# JugendLichtSteuerung.net
KiCad netlist of a schematic drawn in EAGLE
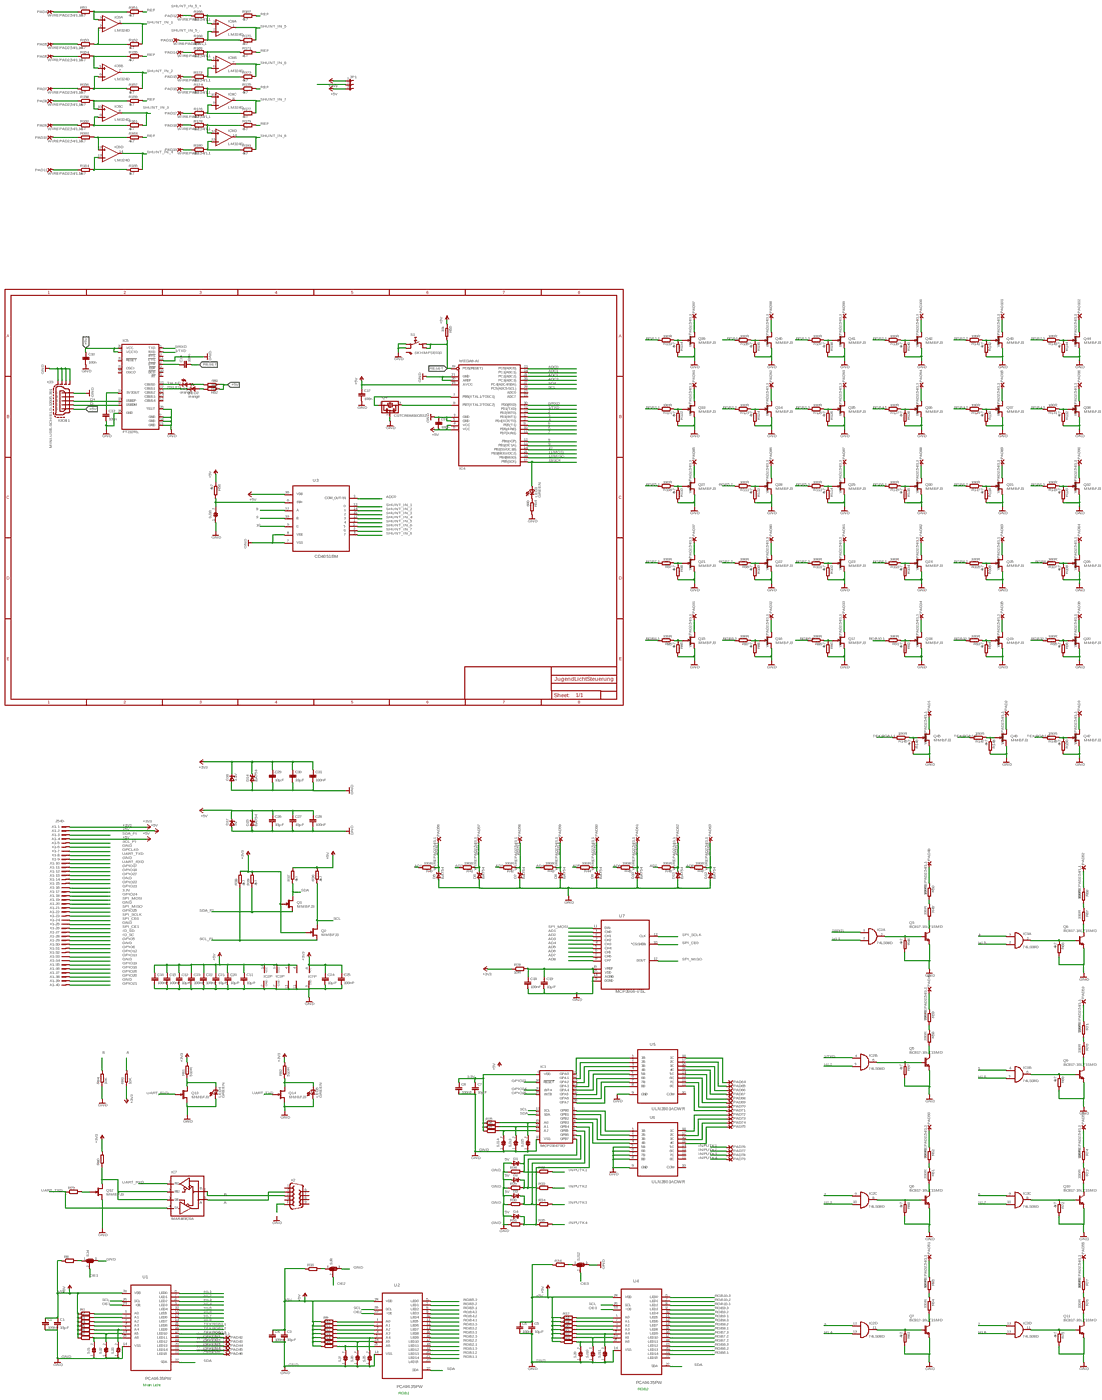
[diagram p0: schematic, sheet 1, overview]
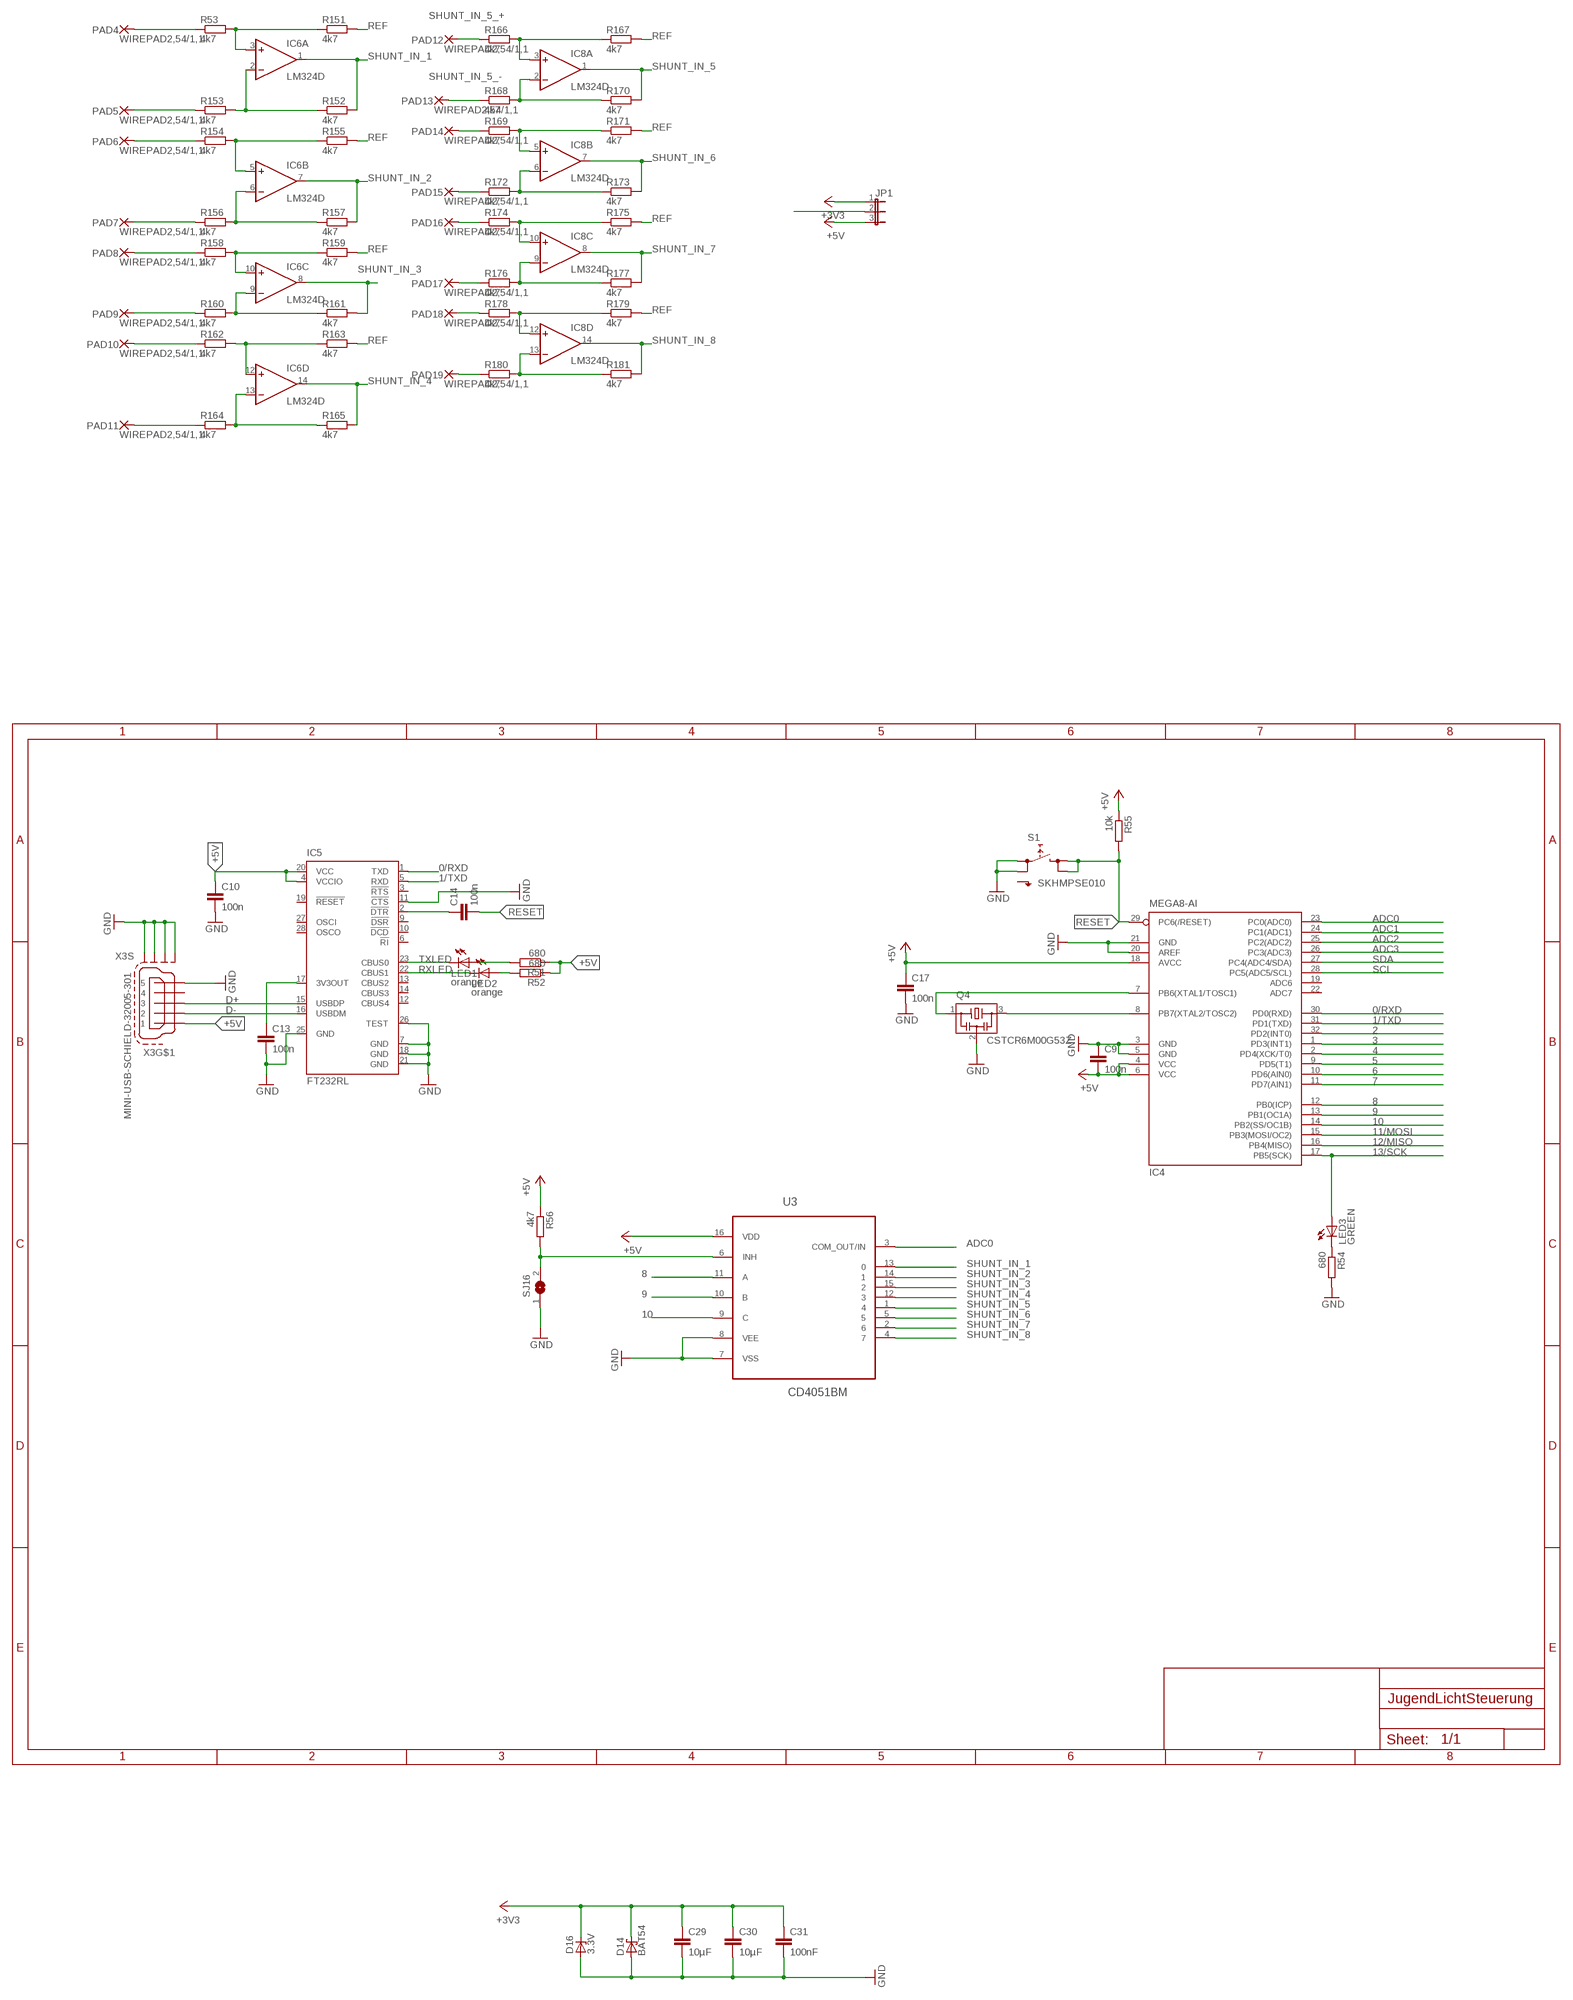
[diagram p1: schematic, sheet 1, part 1 of 4]
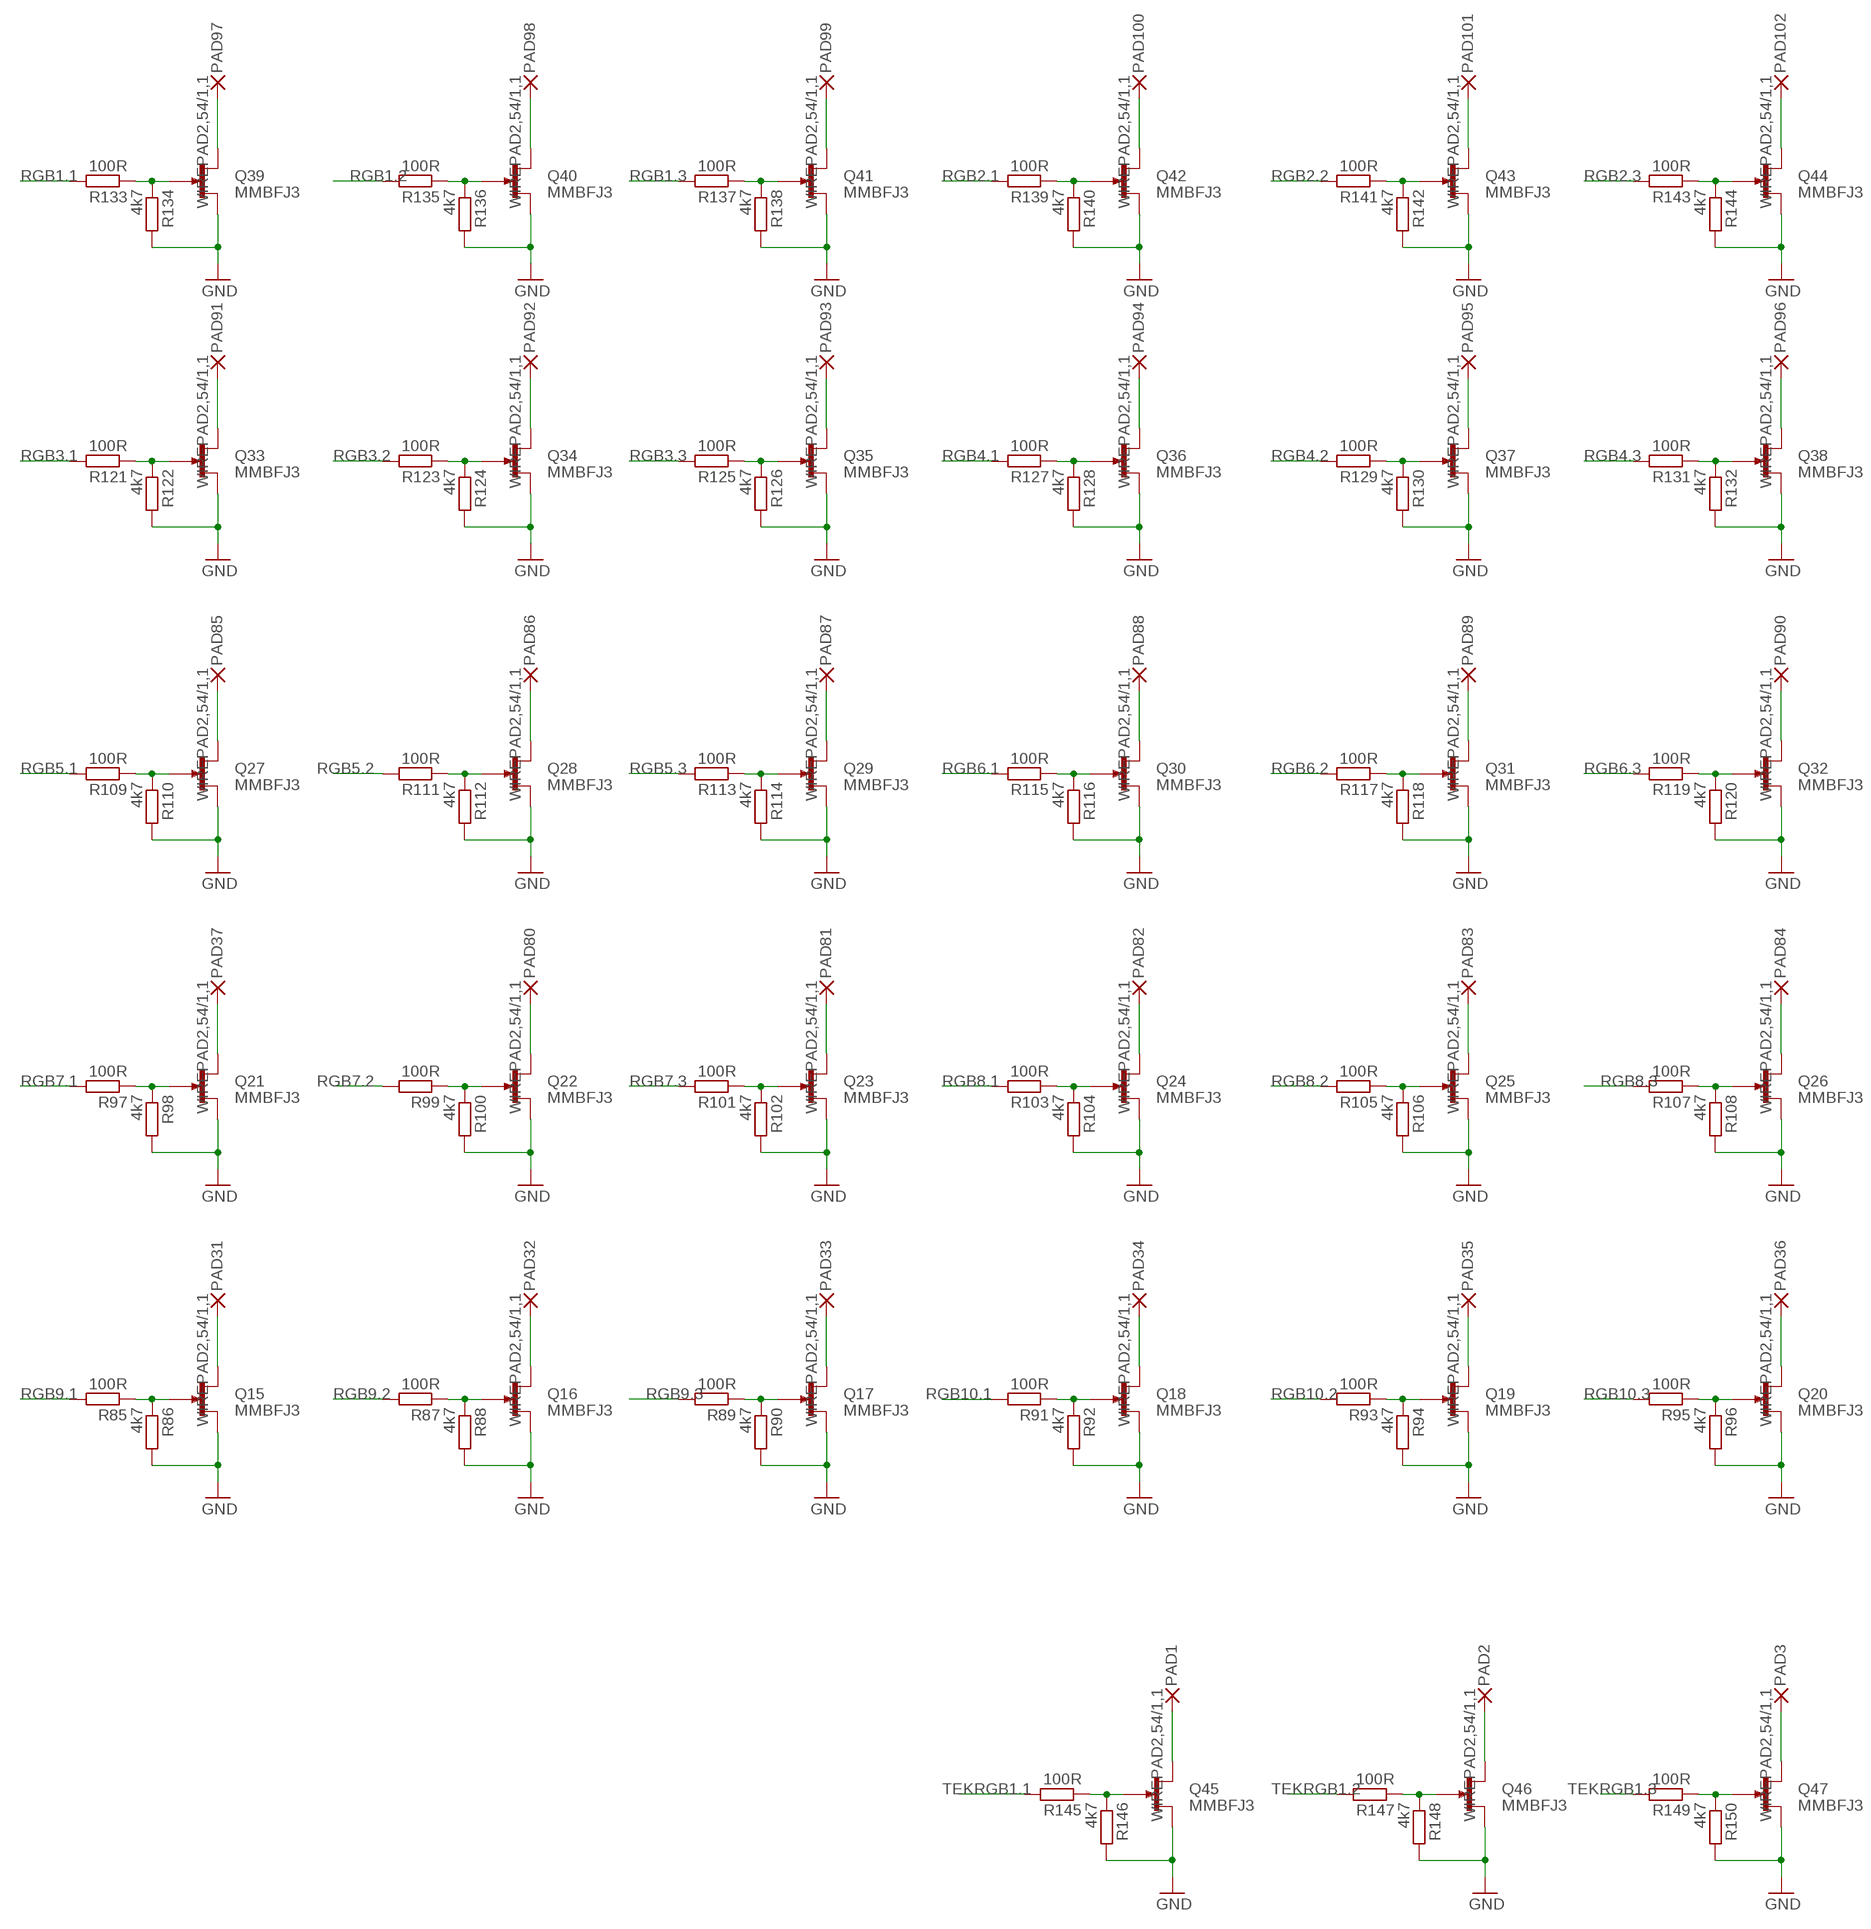
[diagram p2: schematic, sheet 1, part 2 of 4]
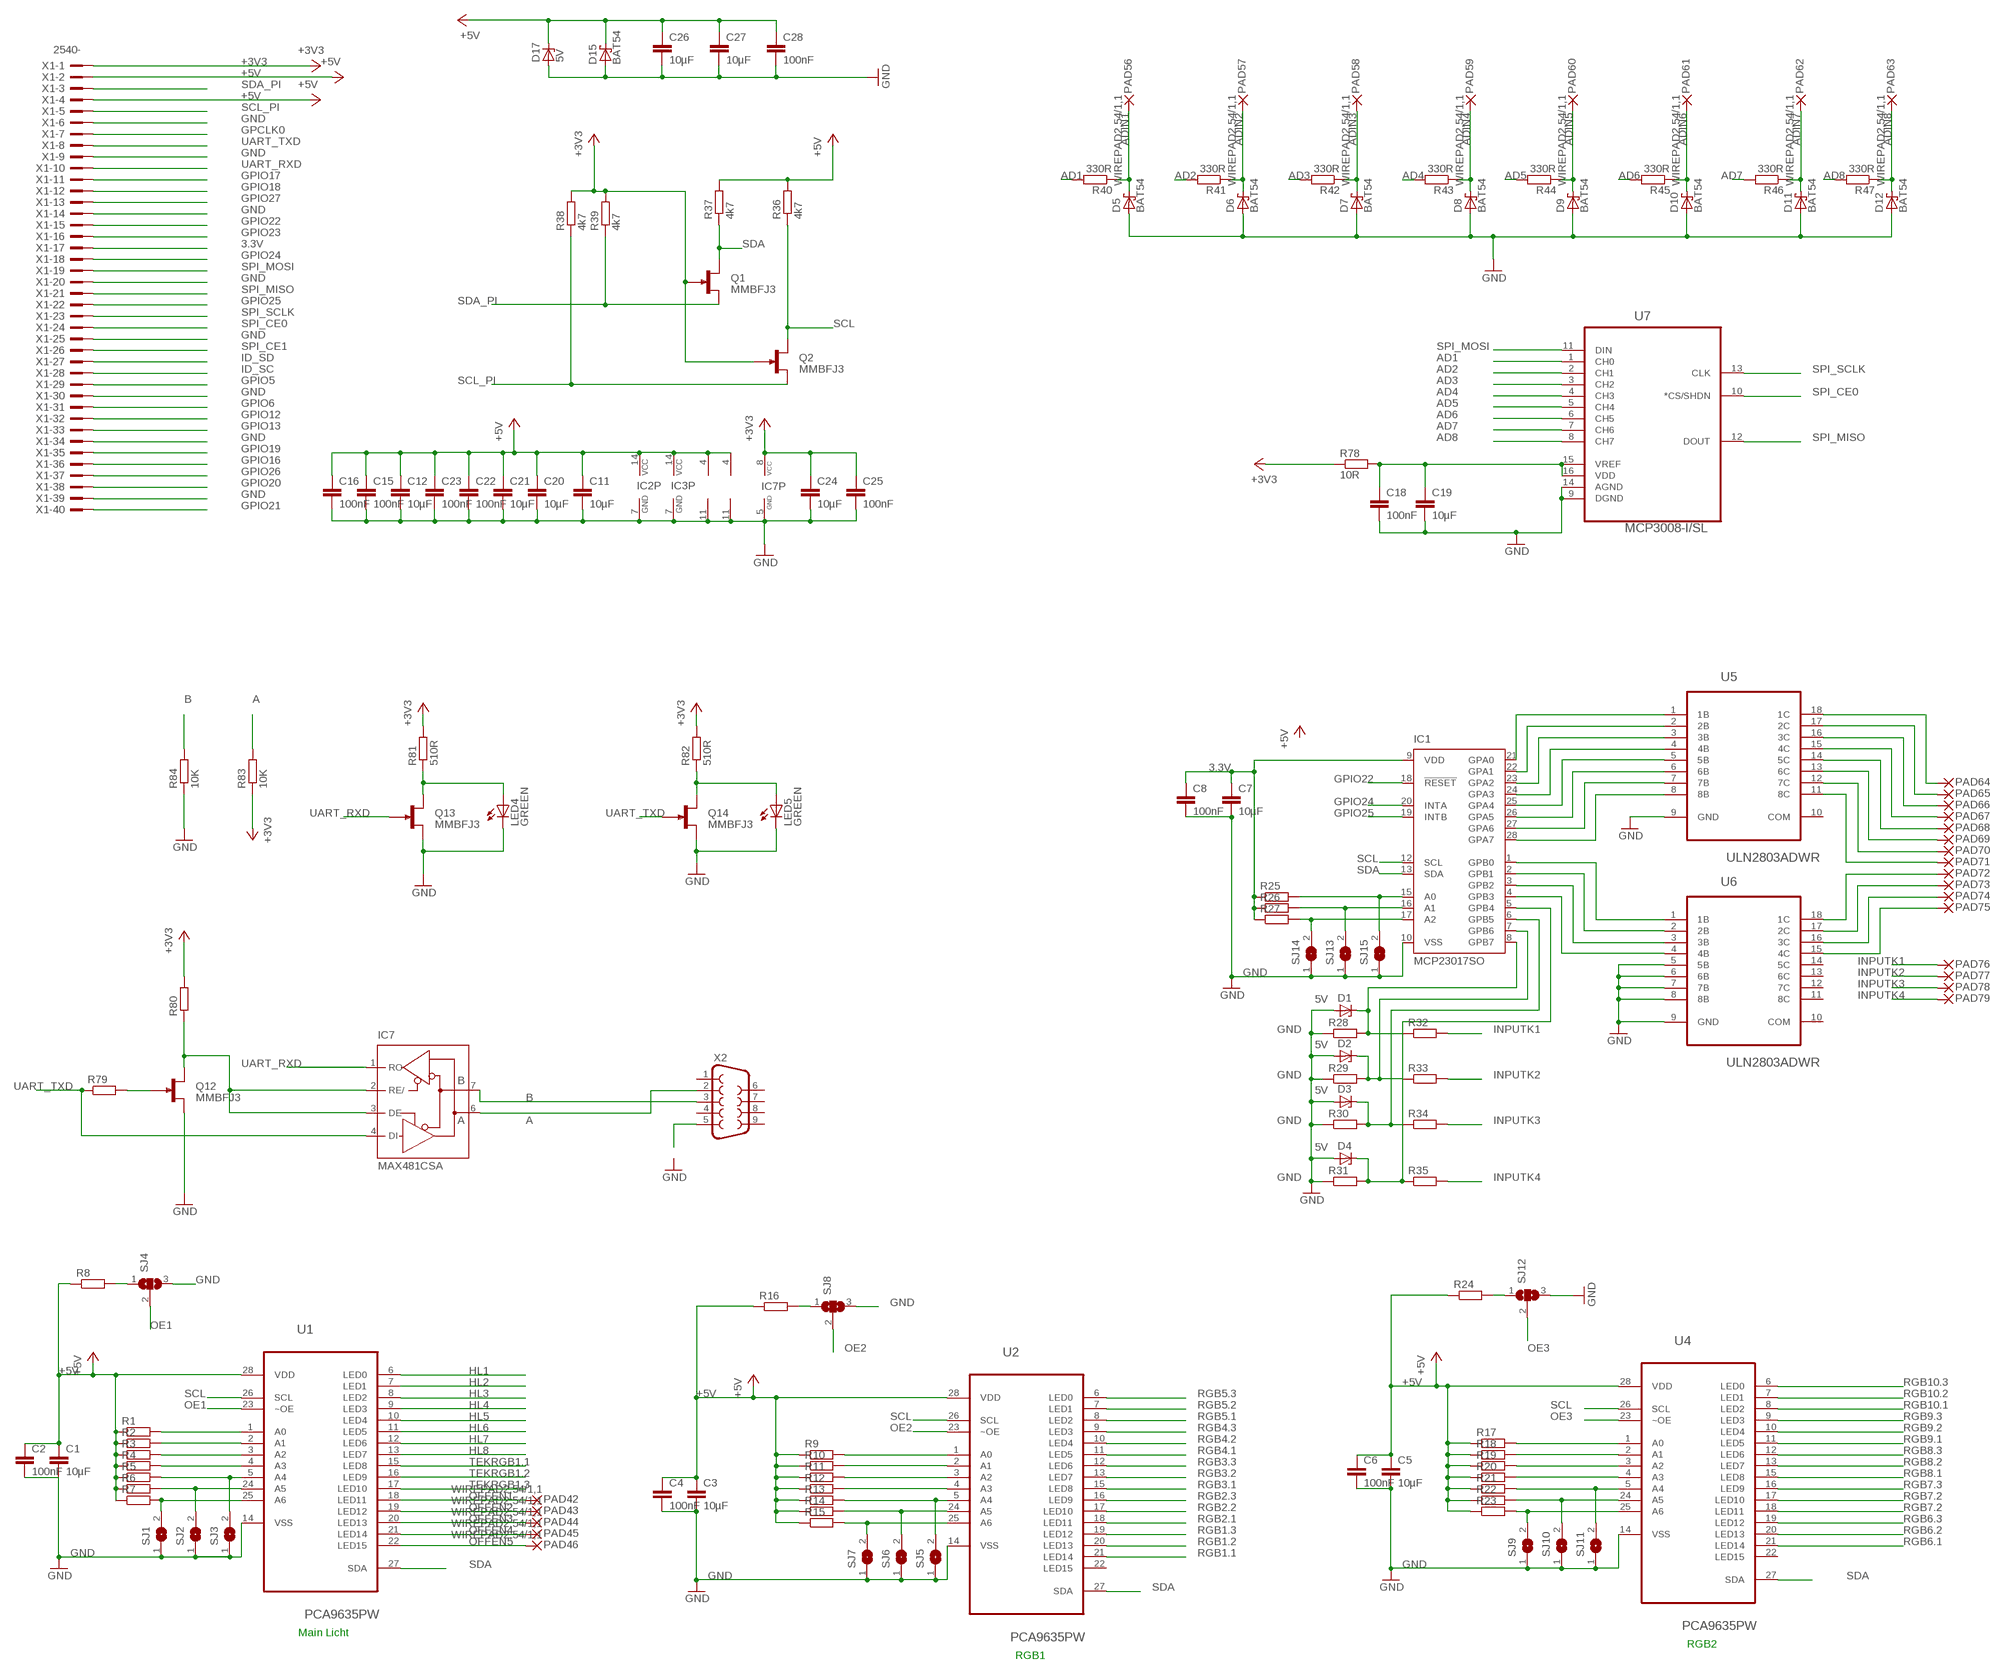
[diagram p3: schematic, sheet 1, part 3 of 4]
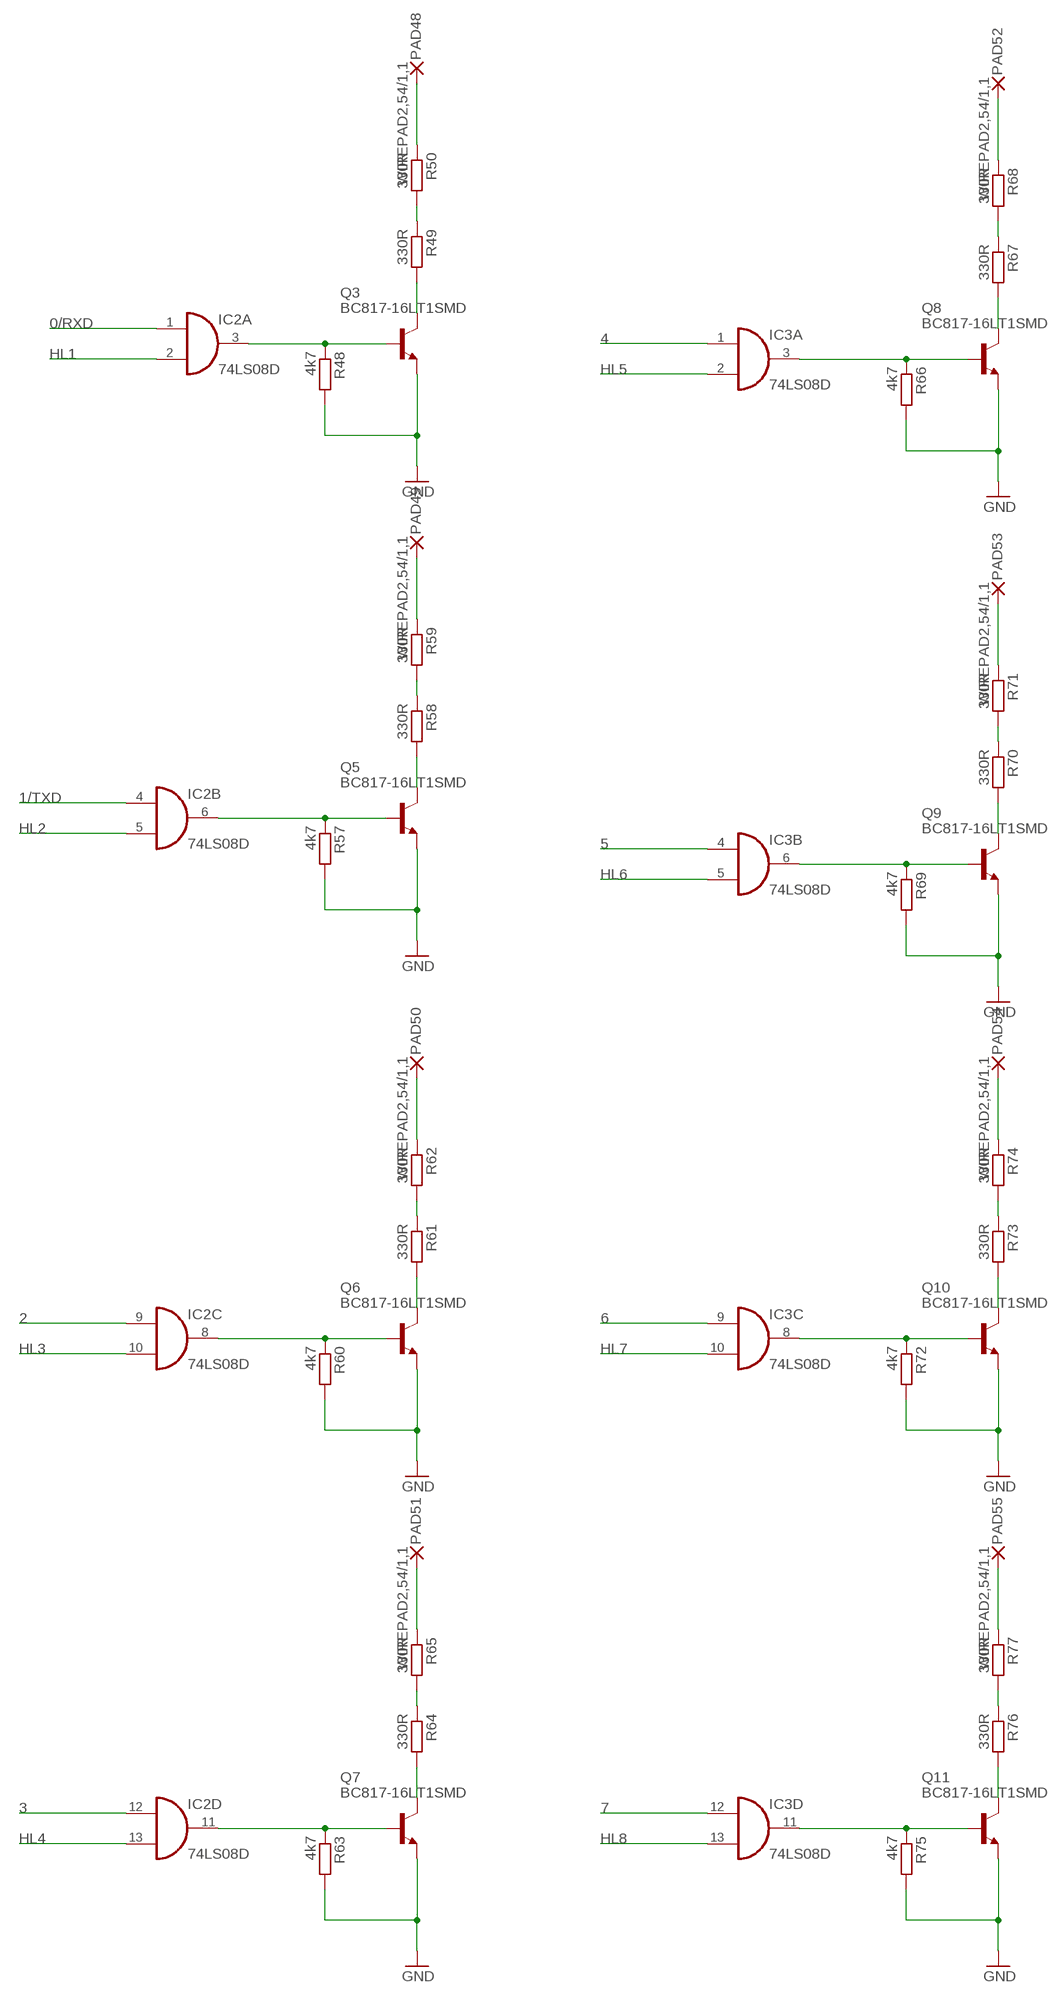
[diagram p4: schematic, sheet 1, part 4 of 4]

(export (version "E")
  (design (tool "Eeschema 10.0.6"))
  (components
    (comp (ref "C1")
      (value "10µF")
      (footprint "eagle-import:C0805")
      (libsource (lib "eagle-import") (part "C-EUC0805"))
    )
    (comp (ref "C2")
      (value "100nF")
      (footprint "eagle-import:C0805")
      (libsource (lib "eagle-import") (part "C-EUC0805"))
    )
    (comp (ref "C3")
      (value "10µF")
      (footprint "eagle-import:C0805")
      (libsource (lib "eagle-import") (part "C-EUC0805"))
    )
    (comp (ref "C4")
      (value "100nF")
      (footprint "eagle-import:C0805")
      (libsource (lib "eagle-import") (part "C-EUC0805"))
    )
    (comp (ref "C5")
      (value "10µF")
      (footprint "eagle-import:C0805")
      (libsource (lib "eagle-import") (part "C-EUC0805"))
    )
    (comp (ref "C6")
      (value "100nF")
      (footprint "eagle-import:C0805")
      (libsource (lib "eagle-import") (part "C-EUC0805"))
    )
    (comp (ref "C7")
      (value "10µF")
      (footprint "eagle-import:C0805")
      (libsource (lib "eagle-import") (part "C-EUC0805"))
    )
    (comp (ref "C8")
      (value "100nF")
      (footprint "eagle-import:C0805")
      (libsource (lib "eagle-import") (part "C-EUC0805"))
    )
    (comp (ref "C9")
      (value "100n")
      (footprint "eagle-import:C0603")
      (libsource (lib "eagle-import") (part "resistor_C-EUC0603"))
    )
    (comp (ref "C10")
      (value "100n")
      (footprint "eagle-import:C0603")
      (libsource (lib "eagle-import") (part "resistor_C-EUC0603"))
    )
    (comp (ref "C11")
      (value "10µF")
      (footprint "eagle-import:C0805")
      (libsource (lib "eagle-import") (part "C-EUC0805"))
    )
    (comp (ref "C12")
      (value "10µF")
      (footprint "eagle-import:C0805")
      (libsource (lib "eagle-import") (part "C-EUC0805"))
    )
    (comp (ref "C13")
      (value "100n")
      (footprint "eagle-import:C1206K")
      (libsource (lib "eagle-import") (part "C-EUC1206K"))
    )
    (comp (ref "C14")
      (value "100n")
      (footprint "eagle-import:C0603")
      (libsource (lib "eagle-import") (part "resistor_C-EUC0603"))
    )
    (comp (ref "C15")
      (value "100nF")
      (footprint "eagle-import:C0805")
      (libsource (lib "eagle-import") (part "C-EUC0805"))
    )
    (comp (ref "C16")
      (value "100nF")
      (footprint "eagle-import:C0805")
      (libsource (lib "eagle-import") (part "C-EUC0805"))
    )
    (comp (ref "C17")
      (value "100n")
      (footprint "eagle-import:C0603K")
      (libsource (lib "eagle-import") (part "C-EUC0603K"))
    )
    (comp (ref "C18")
      (value "100nF")
      (footprint "eagle-import:C0805")
      (libsource (lib "eagle-import") (part "C-EUC0805"))
    )
    (comp (ref "C19")
      (value "10µF")
      (footprint "eagle-import:C0805")
      (libsource (lib "eagle-import") (part "C-EUC0805"))
    )
    (comp (ref "C20")
      (value "10µF")
      (footprint "eagle-import:C0805")
      (libsource (lib "eagle-import") (part "C-EUC0805"))
    )
    (comp (ref "C21")
      (value "10µF")
      (footprint "eagle-import:C0805")
      (libsource (lib "eagle-import") (part "C-EUC0805"))
    )
    (comp (ref "C22")
      (value "100nF")
      (footprint "eagle-import:C0805")
      (libsource (lib "eagle-import") (part "C-EUC0805"))
    )
    (comp (ref "C23")
      (value "100nF")
      (footprint "eagle-import:C0805")
      (libsource (lib "eagle-import") (part "C-EUC0805"))
    )
    (comp (ref "C24")
      (value "10µF")
      (footprint "eagle-import:C0805")
      (libsource (lib "eagle-import") (part "C-EUC0805"))
    )
    (comp (ref "C25")
      (value "100nF")
      (footprint "eagle-import:C0805")
      (libsource (lib "eagle-import") (part "C-EUC0805"))
    )
    (comp (ref "C26")
      (value "10µF")
      (footprint "eagle-import:C0805")
      (libsource (lib "eagle-import") (part "C-EUC0805"))
    )
    (comp (ref "C27")
      (value "10µF")
      (footprint "eagle-import:C0805")
      (libsource (lib "eagle-import") (part "C-EUC0805"))
    )
    (comp (ref "C28")
      (value "100nF")
      (footprint "eagle-import:C0805")
      (libsource (lib "eagle-import") (part "C-EUC0805"))
    )
    (comp (ref "C29")
      (value "10µF")
      (footprint "eagle-import:C0805")
      (libsource (lib "eagle-import") (part "C-EUC0805"))
    )
    (comp (ref "C30")
      (value "10µF")
      (footprint "eagle-import:C0805")
      (libsource (lib "eagle-import") (part "C-EUC0805"))
    )
    (comp (ref "C31")
      (value "100nF")
      (footprint "eagle-import:C0805")
      (libsource (lib "eagle-import") (part "C-EUC0805"))
    )
    (comp (ref "D1")
      (value "5V")
      (footprint "eagle-import:SOD80C")
      (libsource (lib "eagle-import") (part "ZENER-DIODESOD80C"))
    )
    (comp (ref "D2")
      (value "5V")
      (footprint "eagle-import:SOD80C")
      (libsource (lib "eagle-import") (part "ZENER-DIODESOD80C"))
    )
    (comp (ref "D3")
      (value "5V")
      (footprint "eagle-import:SOD80C")
      (libsource (lib "eagle-import") (part "ZENER-DIODESOD80C"))
    )
    (comp (ref "D4")
      (value "5V")
      (footprint "eagle-import:SOD80C")
      (libsource (lib "eagle-import") (part "ZENER-DIODESOD80C"))
    )
    (comp (ref "D5")
      (value "BAT54")
      (footprint "eagle-import:SOT23")
      (libsource (lib "eagle-import") (part "BAT54"))
    )
    (comp (ref "D6")
      (value "BAT54")
      (footprint "eagle-import:SOT23")
      (libsource (lib "eagle-import") (part "BAT54"))
    )
    (comp (ref "D7")
      (value "BAT54")
      (footprint "eagle-import:SOT23")
      (libsource (lib "eagle-import") (part "BAT54"))
    )
    (comp (ref "D8")
      (value "BAT54")
      (footprint "eagle-import:SOT23")
      (libsource (lib "eagle-import") (part "BAT54"))
    )
    (comp (ref "D9")
      (value "BAT54")
      (footprint "eagle-import:SOT23")
      (libsource (lib "eagle-import") (part "BAT54"))
    )
    (comp (ref "D10")
      (value "BAT54")
      (footprint "eagle-import:SOT23")
      (libsource (lib "eagle-import") (part "BAT54"))
    )
    (comp (ref "D11")
      (value "BAT54")
      (footprint "eagle-import:SOT23")
      (libsource (lib "eagle-import") (part "BAT54"))
    )
    (comp (ref "D12")
      (value "BAT54")
      (footprint "eagle-import:SOT23")
      (libsource (lib "eagle-import") (part "BAT54"))
    )
    (comp (ref "D14")
      (value "BAT54")
      (footprint "eagle-import:SOT23")
      (libsource (lib "eagle-import") (part "BAT54"))
    )
    (comp (ref "D15")
      (value "BAT54")
      (footprint "eagle-import:SOT23")
      (libsource (lib "eagle-import") (part "BAT54"))
    )
    (comp (ref "D16")
      (value "3.3V")
      (footprint "eagle-import:SOD80C")
      (libsource (lib "eagle-import") (part "ZENER-DIODESOD80C"))
    )
    (comp (ref "D17")
      (value "5V")
      (footprint "eagle-import:SOD80C")
      (libsource (lib "eagle-import") (part "ZENER-DIODESOD80C"))
    )
    (comp (ref "IC1")
      (value "MCP23017SO")
      (footprint "eagle-import:SO28W")
      (fields (field (name "MF") "MICROCHIP") (field (name "MPN") "MCP23017-E/SO"))
      (libsource (lib "eagle-import") (part "MCP23017SO"))
    )
    (comp (ref "IC2")
      (value "74LS08D")
      (footprint "eagle-import:SO14")
      (libsource (lib "eagle-import") (part "7408DLS"))
    )
    (comp (ref "IC3")
      (value "74LS08D")
      (footprint "eagle-import:SO14")
      (libsource (lib "eagle-import") (part "7408DLS"))
    )
    (comp (ref "IC4")
      (value "MEGA8-AI")
      (footprint "eagle-import:TQFP32-08")
      (fields (field (name "MPN") "ATMEGA8-16AU"))
      (libsource (lib "eagle-import") (part "MEGA8-AI"))
    )
    (comp (ref "IC5")
      (value "FT232RL")
      (footprint "eagle-import:SSOP28")
      (libsource (lib "eagle-import") (part "FT232RL"))
    )
    (comp (ref "IC6")
      (value "LM324D")
      (footprint "eagle-import:SO14")
      (libsource (lib "eagle-import") (part "LM324D"))
    )
    (comp (ref "IC7")
      (value "MAX481CSA")
      (footprint "eagle-import:SO08")
      (fields (field (name "MF") "MAXIM"))
      (libsource (lib "eagle-import") (part "MAX481CSA"))
    )
    (comp (ref "IC8")
      (value "LM324D")
      (footprint "eagle-import:SO14")
      (libsource (lib "eagle-import") (part "LM324D"))
    )
    (comp (ref "JP1")
      (value "JP2E")
      (footprint "eagle-import:JP2")
      (libsource (lib "eagle-import") (part "JP2E"))
    )
    (comp (ref "LED1")
      (value "orange")
      (footprint "eagle-import:CHIPLED_1206")
      (libsource (lib "eagle-import") (part "LEDCHIPLED_1206"))
    )
    (comp (ref "LED2")
      (value "orange")
      (footprint "eagle-import:CHIPLED_1206")
      (libsource (lib "eagle-import") (part "LEDCHIPLED_1206"))
    )
    (comp (ref "LED3")
      (value "GREEN")
      (footprint "eagle-import:CHIPLED_1206")
      (libsource (lib "eagle-import") (part "LEDCHIPLED_1206"))
    )
    (comp (ref "LED4")
      (value "GREEN")
      (footprint "eagle-import:CHIPLED_1206")
      (libsource (lib "eagle-import") (part "LEDCHIPLED_1206"))
    )
    (comp (ref "LED5")
      (value "GREEN")
      (footprint "eagle-import:CHIPLED_1206")
      (libsource (lib "eagle-import") (part "LEDCHIPLED_1206"))
    )
    (comp (ref "PAD1")
      (value "WIREPAD2,54/1,1")
      (footprint "eagle-import:2,54_1,1")
      (libsource (lib "eagle-import") (part "WIREPAD2,54/1,1"))
    )
    (comp (ref "PAD2")
      (value "WIREPAD2,54/1,1")
      (footprint "eagle-import:2,54_1,1")
      (libsource (lib "eagle-import") (part "WIREPAD2,54/1,1"))
    )
    (comp (ref "PAD3")
      (value "WIREPAD2,54/1,1")
      (footprint "eagle-import:2,54_1,1")
      (libsource (lib "eagle-import") (part "WIREPAD2,54/1,1"))
    )
    (comp (ref "PAD4")
      (value "WIREPAD2,54/1,1")
      (footprint "eagle-import:2,54_1,1")
      (libsource (lib "eagle-import") (part "WIREPAD2,54/1,1"))
    )
    (comp (ref "PAD5")
      (value "WIREPAD2,54/1,1")
      (footprint "eagle-import:2,54_1,1")
      (libsource (lib "eagle-import") (part "WIREPAD2,54/1,1"))
    )
    (comp (ref "PAD6")
      (value "WIREPAD2,54/1,1")
      (footprint "eagle-import:2,54_1,1")
      (libsource (lib "eagle-import") (part "WIREPAD2,54/1,1"))
    )
    (comp (ref "PAD7")
      (value "WIREPAD2,54/1,1")
      (footprint "eagle-import:2,54_1,1")
      (libsource (lib "eagle-import") (part "WIREPAD2,54/1,1"))
    )
    (comp (ref "PAD8")
      (value "WIREPAD2,54/1,1")
      (footprint "eagle-import:2,54_1,1")
      (libsource (lib "eagle-import") (part "WIREPAD2,54/1,1"))
    )
    (comp (ref "PAD9")
      (value "WIREPAD2,54/1,1")
      (footprint "eagle-import:2,54_1,1")
      (libsource (lib "eagle-import") (part "WIREPAD2,54/1,1"))
    )
    (comp (ref "PAD10")
      (value "WIREPAD2,54/1,1")
      (footprint "eagle-import:2,54_1,1")
      (libsource (lib "eagle-import") (part "WIREPAD2,54/1,1"))
    )
    (comp (ref "PAD11")
      (value "WIREPAD2,54/1,1")
      (footprint "eagle-import:2,54_1,1")
      (libsource (lib "eagle-import") (part "WIREPAD2,54/1,1"))
    )
    (comp (ref "PAD12")
      (value "WIREPAD2,54/1,1")
      (footprint "eagle-import:2,54_1,1")
      (libsource (lib "eagle-import") (part "WIREPAD2,54/1,1"))
    )
    (comp (ref "PAD13")
      (value "WIREPAD2,54/1,1")
      (footprint "eagle-import:2,54_1,1")
      (libsource (lib "eagle-import") (part "WIREPAD2,54/1,1"))
    )
    (comp (ref "PAD14")
      (value "WIREPAD2,54/1,1")
      (footprint "eagle-import:2,54_1,1")
      (libsource (lib "eagle-import") (part "WIREPAD2,54/1,1"))
    )
    (comp (ref "PAD15")
      (value "WIREPAD2,54/1,1")
      (footprint "eagle-import:2,54_1,1")
      (libsource (lib "eagle-import") (part "WIREPAD2,54/1,1"))
    )
    (comp (ref "PAD16")
      (value "WIREPAD2,54/1,1")
      (footprint "eagle-import:2,54_1,1")
      (libsource (lib "eagle-import") (part "WIREPAD2,54/1,1"))
    )
    (comp (ref "PAD17")
      (value "WIREPAD2,54/1,1")
      (footprint "eagle-import:2,54_1,1")
      (libsource (lib "eagle-import") (part "WIREPAD2,54/1,1"))
    )
    (comp (ref "PAD18")
      (value "WIREPAD2,54/1,1")
      (footprint "eagle-import:2,54_1,1")
      (libsource (lib "eagle-import") (part "WIREPAD2,54/1,1"))
    )
    (comp (ref "PAD19")
      (value "WIREPAD2,54/1,1")
      (footprint "eagle-import:2,54_1,1")
      (libsource (lib "eagle-import") (part "WIREPAD2,54/1,1"))
    )
    (comp (ref "PAD31")
      (value "WIREPAD2,54/1,1")
      (footprint "eagle-import:2,54_1,1")
      (libsource (lib "eagle-import") (part "WIREPAD2,54/1,1"))
    )
    (comp (ref "PAD32")
      (value "WIREPAD2,54/1,1")
      (footprint "eagle-import:2,54_1,1")
      (libsource (lib "eagle-import") (part "WIREPAD2,54/1,1"))
    )
    (comp (ref "PAD33")
      (value "WIREPAD2,54/1,1")
      (footprint "eagle-import:2,54_1,1")
      (libsource (lib "eagle-import") (part "WIREPAD2,54/1,1"))
    )
    (comp (ref "PAD34")
      (value "WIREPAD2,54/1,1")
      (footprint "eagle-import:2,54_1,1")
      (libsource (lib "eagle-import") (part "WIREPAD2,54/1,1"))
    )
    (comp (ref "PAD35")
      (value "WIREPAD2,54/1,1")
      (footprint "eagle-import:2,54_1,1")
      (libsource (lib "eagle-import") (part "WIREPAD2,54/1,1"))
    )
    (comp (ref "PAD36")
      (value "WIREPAD2,54/1,1")
      (footprint "eagle-import:2,54_1,1")
      (libsource (lib "eagle-import") (part "WIREPAD2,54/1,1"))
    )
    (comp (ref "PAD37")
      (value "WIREPAD2,54/1,1")
      (footprint "eagle-import:2,54_1,1")
      (libsource (lib "eagle-import") (part "WIREPAD2,54/1,1"))
    )
    (comp (ref "PAD42")
      (value "WIREPAD2,54/1,1")
      (footprint "eagle-import:2,54_1,1")
      (libsource (lib "eagle-import") (part "WIREPAD2,54/1,1"))
    )
    (comp (ref "PAD43")
      (value "WIREPAD2,54/1,1")
      (footprint "eagle-import:2,54_1,1")
      (libsource (lib "eagle-import") (part "WIREPAD2,54/1,1"))
    )
    (comp (ref "PAD44")
      (value "WIREPAD2,54/1,1")
      (footprint "eagle-import:2,54_1,1")
      (libsource (lib "eagle-import") (part "WIREPAD2,54/1,1"))
    )
    (comp (ref "PAD45")
      (value "WIREPAD2,54/1,1")
      (footprint "eagle-import:2,54_1,1")
      (libsource (lib "eagle-import") (part "WIREPAD2,54/1,1"))
    )
    (comp (ref "PAD46")
      (value "WIREPAD2,54/1,1")
      (footprint "eagle-import:2,54_1,1")
      (libsource (lib "eagle-import") (part "WIREPAD2,54/1,1"))
    )
    (comp (ref "PAD48")
      (value "WIREPAD2,54/1,1")
      (footprint "eagle-import:2,54_1,1")
      (libsource (lib "eagle-import") (part "WIREPAD2,54/1,1"))
    )
    (comp (ref "PAD49")
      (value "WIREPAD2,54/1,1")
      (footprint "eagle-import:2,54_1,1")
      (libsource (lib "eagle-import") (part "WIREPAD2,54/1,1"))
    )
    (comp (ref "PAD50")
      (value "WIREPAD2,54/1,1")
      (footprint "eagle-import:2,54_1,1")
      (libsource (lib "eagle-import") (part "WIREPAD2,54/1,1"))
    )
    (comp (ref "PAD51")
      (value "WIREPAD2,54/1,1")
      (footprint "eagle-import:2,54_1,1")
      (libsource (lib "eagle-import") (part "WIREPAD2,54/1,1"))
    )
    (comp (ref "PAD52")
      (value "WIREPAD2,54/1,1")
      (footprint "eagle-import:2,54_1,1")
      (libsource (lib "eagle-import") (part "WIREPAD2,54/1,1"))
    )
    (comp (ref "PAD53")
      (value "WIREPAD2,54/1,1")
      (footprint "eagle-import:2,54_1,1")
      (libsource (lib "eagle-import") (part "WIREPAD2,54/1,1"))
    )
    (comp (ref "PAD54")
      (value "WIREPAD2,54/1,1")
      (footprint "eagle-import:2,54_1,1")
      (libsource (lib "eagle-import") (part "WIREPAD2,54/1,1"))
    )
    (comp (ref "PAD55")
      (value "WIREPAD2,54/1,1")
      (footprint "eagle-import:2,54_1,1")
      (libsource (lib "eagle-import") (part "WIREPAD2,54/1,1"))
    )
    (comp (ref "PAD56")
      (value "WIREPAD2,54/1,1")
      (footprint "eagle-import:2,54_1,1")
      (libsource (lib "eagle-import") (part "WIREPAD2,54/1,1"))
    )
    (comp (ref "PAD57")
      (value "WIREPAD2,54/1,1")
      (footprint "eagle-import:2,54_1,1")
      (libsource (lib "eagle-import") (part "WIREPAD2,54/1,1"))
    )
    (comp (ref "PAD58")
      (value "WIREPAD2,54/1,1")
      (footprint "eagle-import:2,54_1,1")
      (libsource (lib "eagle-import") (part "WIREPAD2,54/1,1"))
    )
    (comp (ref "PAD59")
      (value "WIREPAD2,54/1,1")
      (footprint "eagle-import:2,54_1,1")
      (libsource (lib "eagle-import") (part "WIREPAD2,54/1,1"))
    )
    (comp (ref "PAD60")
      (value "WIREPAD2,54/1,1")
      (footprint "eagle-import:2,54_1,1")
      (libsource (lib "eagle-import") (part "WIREPAD2,54/1,1"))
    )
    (comp (ref "PAD61")
      (value "WIREPAD2,54/1,1")
      (footprint "eagle-import:2,54_1,1")
      (libsource (lib "eagle-import") (part "WIREPAD2,54/1,1"))
    )
    (comp (ref "PAD62")
      (value "WIREPAD2,54/1,1")
      (footprint "eagle-import:2,54_1,1")
      (libsource (lib "eagle-import") (part "WIREPAD2,54/1,1"))
    )
    (comp (ref "PAD63")
      (value "WIREPAD2,54/1,1")
      (footprint "eagle-import:2,54_1,1")
      (libsource (lib "eagle-import") (part "WIREPAD2,54/1,1"))
    )
    (comp (ref "PAD64")
      (value "3,81/1,4")
      (footprint "eagle-import:3,81_1,4")
      (libsource (lib "eagle-import") (part "3,81/1,4"))
    )
    (comp (ref "PAD65")
      (value "3,81/1,4")
      (footprint "eagle-import:3,81_1,4")
      (libsource (lib "eagle-import") (part "3,81/1,4"))
    )
    (comp (ref "PAD66")
      (value "3,81/1,4")
      (footprint "eagle-import:3,81_1,4")
      (libsource (lib "eagle-import") (part "3,81/1,4"))
    )
    (comp (ref "PAD67")
      (value "3,81/1,4")
      (footprint "eagle-import:3,81_1,4")
      (libsource (lib "eagle-import") (part "3,81/1,4"))
    )
    (comp (ref "PAD68")
      (value "3,81/1,4")
      (footprint "eagle-import:3,81_1,4")
      (libsource (lib "eagle-import") (part "3,81/1,4"))
    )
    (comp (ref "PAD69")
      (value "3,81/1,4")
      (footprint "eagle-import:3,81_1,4")
      (libsource (lib "eagle-import") (part "3,81/1,4"))
    )
    (comp (ref "PAD70")
      (value "3,81/1,4")
      (footprint "eagle-import:3,81_1,4")
      (libsource (lib "eagle-import") (part "3,81/1,4"))
    )
    (comp (ref "PAD71")
      (value "3,81/1,4")
      (footprint "eagle-import:3,81_1,4")
      (libsource (lib "eagle-import") (part "3,81/1,4"))
    )
    (comp (ref "PAD72")
      (value "3,81/1,4")
      (footprint "eagle-import:3,81_1,4")
      (libsource (lib "eagle-import") (part "3,81/1,4"))
    )
    (comp (ref "PAD73")
      (value "3,81/1,4")
      (footprint "eagle-import:3,81_1,4")
      (libsource (lib "eagle-import") (part "3,81/1,4"))
    )
    (comp (ref "PAD74")
      (value "3,81/1,4")
      (footprint "eagle-import:3,81_1,4")
      (libsource (lib "eagle-import") (part "3,81/1,4"))
    )
    (comp (ref "PAD75")
      (value "3,81/1,4")
      (footprint "eagle-import:3,81_1,4")
      (libsource (lib "eagle-import") (part "3,81/1,4"))
    )
    (comp (ref "PAD76")
      (value "3,81/1,4")
      (footprint "eagle-import:3,81_1,4")
      (libsource (lib "eagle-import") (part "3,81/1,4"))
    )
    (comp (ref "PAD77")
      (value "3,81/1,4")
      (footprint "eagle-import:3,81_1,4")
      (libsource (lib "eagle-import") (part "3,81/1,4"))
    )
    (comp (ref "PAD78")
      (value "3,81/1,4")
      (footprint "eagle-import:3,81_1,4")
      (libsource (lib "eagle-import") (part "3,81/1,4"))
    )
    (comp (ref "PAD79")
      (value "3,81/1,4")
      (footprint "eagle-import:3,81_1,4")
      (libsource (lib "eagle-import") (part "3,81/1,4"))
    )
    (comp (ref "PAD80")
      (value "WIREPAD2,54/1,1")
      (footprint "eagle-import:2,54_1,1")
      (libsource (lib "eagle-import") (part "WIREPAD2,54/1,1"))
    )
    (comp (ref "PAD81")
      (value "WIREPAD2,54/1,1")
      (footprint "eagle-import:2,54_1,1")
      (libsource (lib "eagle-import") (part "WIREPAD2,54/1,1"))
    )
    (comp (ref "PAD82")
      (value "WIREPAD2,54/1,1")
      (footprint "eagle-import:2,54_1,1")
      (libsource (lib "eagle-import") (part "WIREPAD2,54/1,1"))
    )
    (comp (ref "PAD83")
      (value "WIREPAD2,54/1,1")
      (footprint "eagle-import:2,54_1,1")
      (libsource (lib "eagle-import") (part "WIREPAD2,54/1,1"))
    )
    (comp (ref "PAD84")
      (value "WIREPAD2,54/1,1")
      (footprint "eagle-import:2,54_1,1")
      (libsource (lib "eagle-import") (part "WIREPAD2,54/1,1"))
    )
    (comp (ref "PAD85")
      (value "WIREPAD2,54/1,1")
      (footprint "eagle-import:2,54_1,1")
      (libsource (lib "eagle-import") (part "WIREPAD2,54/1,1"))
    )
    (comp (ref "PAD86")
      (value "WIREPAD2,54/1,1")
      (footprint "eagle-import:2,54_1,1")
      (libsource (lib "eagle-import") (part "WIREPAD2,54/1,1"))
    )
    (comp (ref "PAD87")
      (value "WIREPAD2,54/1,1")
      (footprint "eagle-import:2,54_1,1")
      (libsource (lib "eagle-import") (part "WIREPAD2,54/1,1"))
    )
    (comp (ref "PAD88")
      (value "WIREPAD2,54/1,1")
      (footprint "eagle-import:2,54_1,1")
      (libsource (lib "eagle-import") (part "WIREPAD2,54/1,1"))
    )
    (comp (ref "PAD89")
      (value "WIREPAD2,54/1,1")
      (footprint "eagle-import:2,54_1,1")
      (libsource (lib "eagle-import") (part "WIREPAD2,54/1,1"))
    )
    (comp (ref "PAD90")
      (value "WIREPAD2,54/1,1")
      (footprint "eagle-import:2,54_1,1")
      (libsource (lib "eagle-import") (part "WIREPAD2,54/1,1"))
    )
    (comp (ref "PAD91")
      (value "WIREPAD2,54/1,1")
      (footprint "eagle-import:2,54_1,1")
      (libsource (lib "eagle-import") (part "WIREPAD2,54/1,1"))
    )
    (comp (ref "PAD92")
      (value "WIREPAD2,54/1,1")
      (footprint "eagle-import:2,54_1,1")
      (libsource (lib "eagle-import") (part "WIREPAD2,54/1,1"))
    )
    (comp (ref "PAD93")
      (value "WIREPAD2,54/1,1")
      (footprint "eagle-import:2,54_1,1")
      (libsource (lib "eagle-import") (part "WIREPAD2,54/1,1"))
    )
    (comp (ref "PAD94")
      (value "WIREPAD2,54/1,1")
      (footprint "eagle-import:2,54_1,1")
      (libsource (lib "eagle-import") (part "WIREPAD2,54/1,1"))
    )
    (comp (ref "PAD95")
      (value "WIREPAD2,54/1,1")
      (footprint "eagle-import:2,54_1,1")
      (libsource (lib "eagle-import") (part "WIREPAD2,54/1,1"))
    )
    (comp (ref "PAD96")
      (value "WIREPAD2,54/1,1")
      (footprint "eagle-import:2,54_1,1")
      (libsource (lib "eagle-import") (part "WIREPAD2,54/1,1"))
    )
    (comp (ref "PAD97")
      (value "WIREPAD2,54/1,1")
      (footprint "eagle-import:2,54_1,1")
      (libsource (lib "eagle-import") (part "WIREPAD2,54/1,1"))
    )
    (comp (ref "PAD98")
      (value "WIREPAD2,54/1,1")
      (footprint "eagle-import:2,54_1,1")
      (libsource (lib "eagle-import") (part "WIREPAD2,54/1,1"))
    )
    (comp (ref "PAD99")
      (value "WIREPAD2,54/1,1")
      (footprint "eagle-import:2,54_1,1")
      (libsource (lib "eagle-import") (part "WIREPAD2,54/1,1"))
    )
    (comp (ref "PAD100")
      (value "WIREPAD2,54/1,1")
      (footprint "eagle-import:2,54_1,1")
      (libsource (lib "eagle-import") (part "WIREPAD2,54/1,1"))
    )
    (comp (ref "PAD101")
      (value "WIREPAD2,54/1,1")
      (footprint "eagle-import:2,54_1,1")
      (libsource (lib "eagle-import") (part "WIREPAD2,54/1,1"))
    )
    (comp (ref "PAD102")
      (value "WIREPAD2,54/1,1")
      (footprint "eagle-import:2,54_1,1")
      (libsource (lib "eagle-import") (part "WIREPAD2,54/1,1"))
    )
    (comp (ref "Q1")
      (value "MMBFJ3")
      (footprint "eagle-import:SOT23")
      (libsource (lib "eagle-import") (part "MMBFJ3"))
    )
    (comp (ref "Q2")
      (value "MMBFJ3")
      (footprint "eagle-import:SOT23")
      (libsource (lib "eagle-import") (part "MMBFJ3"))
    )
    (comp (ref "Q3")
      (value "BC817-16LT1SMD")
      (footprint "eagle-import:SOT23-BEC")
      (libsource (lib "eagle-import") (part "BC817SMD-16LT1"))
    )
    (comp (ref "Q4")
      (value "CSTCR6M00G53Z")
      (footprint "eagle-import:CSTCR6M")
      (fields (field (name "MPN") "CSTCR6M00G53-R0"))
      (libsource (lib "eagle-import") (part "CSTCR6M00G53Z"))
    )
    (comp (ref "Q5")
      (value "BC817-16LT1SMD")
      (footprint "eagle-import:SOT23-BEC")
      (libsource (lib "eagle-import") (part "BC817SMD-16LT1"))
    )
    (comp (ref "Q6")
      (value "BC817-16LT1SMD")
      (footprint "eagle-import:SOT23-BEC")
      (libsource (lib "eagle-import") (part "BC817SMD-16LT1"))
    )
    (comp (ref "Q7")
      (value "BC817-16LT1SMD")
      (footprint "eagle-import:SOT23-BEC")
      (libsource (lib "eagle-import") (part "BC817SMD-16LT1"))
    )
    (comp (ref "Q8")
      (value "BC817-16LT1SMD")
      (footprint "eagle-import:SOT23-BEC")
      (libsource (lib "eagle-import") (part "BC817SMD-16LT1"))
    )
    (comp (ref "Q9")
      (value "BC817-16LT1SMD")
      (footprint "eagle-import:SOT23-BEC")
      (libsource (lib "eagle-import") (part "BC817SMD-16LT1"))
    )
    (comp (ref "Q10")
      (value "BC817-16LT1SMD")
      (footprint "eagle-import:SOT23-BEC")
      (libsource (lib "eagle-import") (part "BC817SMD-16LT1"))
    )
    (comp (ref "Q11")
      (value "BC817-16LT1SMD")
      (footprint "eagle-import:SOT23-BEC")
      (libsource (lib "eagle-import") (part "BC817SMD-16LT1"))
    )
    (comp (ref "Q12")
      (value "MMBFJ3")
      (footprint "eagle-import:SOT23")
      (libsource (lib "eagle-import") (part "MMBFJ3"))
    )
    (comp (ref "Q13")
      (value "MMBFJ3")
      (footprint "eagle-import:SOT23")
      (libsource (lib "eagle-import") (part "MMBFJ3"))
    )
    (comp (ref "Q14")
      (value "MMBFJ3")
      (footprint "eagle-import:SOT23")
      (libsource (lib "eagle-import") (part "MMBFJ3"))
    )
    (comp (ref "Q15")
      (value "MMBFJ3")
      (footprint "eagle-import:SOT23")
      (libsource (lib "eagle-import") (part "MMBFJ3"))
    )
    (comp (ref "Q16")
      (value "MMBFJ3")
      (footprint "eagle-import:SOT23")
      (libsource (lib "eagle-import") (part "MMBFJ3"))
    )
    (comp (ref "Q17")
      (value "MMBFJ3")
      (footprint "eagle-import:SOT23")
      (libsource (lib "eagle-import") (part "MMBFJ3"))
    )
    (comp (ref "Q18")
      (value "MMBFJ3")
      (footprint "eagle-import:SOT23")
      (libsource (lib "eagle-import") (part "MMBFJ3"))
    )
    (comp (ref "Q19")
      (value "MMBFJ3")
      (footprint "eagle-import:SOT23")
      (libsource (lib "eagle-import") (part "MMBFJ3"))
    )
    (comp (ref "Q20")
      (value "MMBFJ3")
      (footprint "eagle-import:SOT23")
      (libsource (lib "eagle-import") (part "MMBFJ3"))
    )
    (comp (ref "Q21")
      (value "MMBFJ3")
      (footprint "eagle-import:SOT23")
      (libsource (lib "eagle-import") (part "MMBFJ3"))
    )
    (comp (ref "Q22")
      (value "MMBFJ3")
      (footprint "eagle-import:SOT23")
      (libsource (lib "eagle-import") (part "MMBFJ3"))
    )
    (comp (ref "Q23")
      (value "MMBFJ3")
      (footprint "eagle-import:SOT23")
      (libsource (lib "eagle-import") (part "MMBFJ3"))
    )
    (comp (ref "Q24")
      (value "MMBFJ3")
      (footprint "eagle-import:SOT23")
      (libsource (lib "eagle-import") (part "MMBFJ3"))
    )
    (comp (ref "Q25")
      (value "MMBFJ3")
      (footprint "eagle-import:SOT23")
      (libsource (lib "eagle-import") (part "MMBFJ3"))
    )
    (comp (ref "Q26")
      (value "MMBFJ3")
      (footprint "eagle-import:SOT23")
      (libsource (lib "eagle-import") (part "MMBFJ3"))
    )
    (comp (ref "Q27")
      (value "MMBFJ3")
      (footprint "eagle-import:SOT23")
      (libsource (lib "eagle-import") (part "MMBFJ3"))
    )
    (comp (ref "Q28")
      (value "MMBFJ3")
      (footprint "eagle-import:SOT23")
      (libsource (lib "eagle-import") (part "MMBFJ3"))
    )
    (comp (ref "Q29")
      (value "MMBFJ3")
      (footprint "eagle-import:SOT23")
      (libsource (lib "eagle-import") (part "MMBFJ3"))
    )
    (comp (ref "Q30")
      (value "MMBFJ3")
      (footprint "eagle-import:SOT23")
      (libsource (lib "eagle-import") (part "MMBFJ3"))
    )
    (comp (ref "Q31")
      (value "MMBFJ3")
      (footprint "eagle-import:SOT23")
      (libsource (lib "eagle-import") (part "MMBFJ3"))
    )
    (comp (ref "Q32")
      (value "MMBFJ3")
      (footprint "eagle-import:SOT23")
      (libsource (lib "eagle-import") (part "MMBFJ3"))
    )
    (comp (ref "Q33")
      (value "MMBFJ3")
      (footprint "eagle-import:SOT23")
      (libsource (lib "eagle-import") (part "MMBFJ3"))
    )
    (comp (ref "Q34")
      (value "MMBFJ3")
      (footprint "eagle-import:SOT23")
      (libsource (lib "eagle-import") (part "MMBFJ3"))
    )
    (comp (ref "Q35")
      (value "MMBFJ3")
      (footprint "eagle-import:SOT23")
      (libsource (lib "eagle-import") (part "MMBFJ3"))
    )
    (comp (ref "Q36")
      (value "MMBFJ3")
      (footprint "eagle-import:SOT23")
      (libsource (lib "eagle-import") (part "MMBFJ3"))
    )
    (comp (ref "Q37")
      (value "MMBFJ3")
      (footprint "eagle-import:SOT23")
      (libsource (lib "eagle-import") (part "MMBFJ3"))
    )
    (comp (ref "Q38")
      (value "MMBFJ3")
      (footprint "eagle-import:SOT23")
      (libsource (lib "eagle-import") (part "MMBFJ3"))
    )
    (comp (ref "Q39")
      (value "MMBFJ3")
      (footprint "eagle-import:SOT23")
      (libsource (lib "eagle-import") (part "MMBFJ3"))
    )
    (comp (ref "Q40")
      (value "MMBFJ3")
      (footprint "eagle-import:SOT23")
      (libsource (lib "eagle-import") (part "MMBFJ3"))
    )
    (comp (ref "Q41")
      (value "MMBFJ3")
      (footprint "eagle-import:SOT23")
      (libsource (lib "eagle-import") (part "MMBFJ3"))
    )
    (comp (ref "Q42")
      (value "MMBFJ3")
      (footprint "eagle-import:SOT23")
      (libsource (lib "eagle-import") (part "MMBFJ3"))
    )
    (comp (ref "Q43")
      (value "MMBFJ3")
      (footprint "eagle-import:SOT23")
      (libsource (lib "eagle-import") (part "MMBFJ3"))
    )
    (comp (ref "Q44")
      (value "MMBFJ3")
      (footprint "eagle-import:SOT23")
      (libsource (lib "eagle-import") (part "MMBFJ3"))
    )
    (comp (ref "Q45")
      (value "MMBFJ3")
      (footprint "eagle-import:SOT23")
      (libsource (lib "eagle-import") (part "MMBFJ3"))
    )
    (comp (ref "Q46")
      (value "MMBFJ3")
      (footprint "eagle-import:SOT23")
      (libsource (lib "eagle-import") (part "MMBFJ3"))
    )
    (comp (ref "Q47")
      (value "MMBFJ3")
      (footprint "eagle-import:SOT23")
      (libsource (lib "eagle-import") (part "MMBFJ3"))
    )
    (comp (ref "R1")
      (value "R-EU_R0603")
      (footprint "eagle-import:R0603")
      (libsource (lib "eagle-import") (part "R-EU_R0603"))
    )
    (comp (ref "R2")
      (value "R-EU_R0603")
      (footprint "eagle-import:R0603")
      (libsource (lib "eagle-import") (part "R-EU_R0603"))
    )
    (comp (ref "R3")
      (value "R-EU_R0603")
      (footprint "eagle-import:R0603")
      (libsource (lib "eagle-import") (part "R-EU_R0603"))
    )
    (comp (ref "R4")
      (value "R-EU_R0603")
      (footprint "eagle-import:R0603")
      (libsource (lib "eagle-import") (part "R-EU_R0603"))
    )
    (comp (ref "R5")
      (value "R-EU_R0603")
      (footprint "eagle-import:R0603")
      (libsource (lib "eagle-import") (part "R-EU_R0603"))
    )
    (comp (ref "R6")
      (value "R-EU_R0603")
      (footprint "eagle-import:R0603")
      (libsource (lib "eagle-import") (part "R-EU_R0603"))
    )
    (comp (ref "R7")
      (value "R-EU_R0603")
      (footprint "eagle-import:R0603")
      (libsource (lib "eagle-import") (part "R-EU_R0603"))
    )
    (comp (ref "R8")
      (value "R-EU_R0603")
      (footprint "eagle-import:R0603")
      (libsource (lib "eagle-import") (part "R-EU_R0603"))
    )
    (comp (ref "R9")
      (value "R-EU_R0603")
      (footprint "eagle-import:R0603")
      (libsource (lib "eagle-import") (part "R-EU_R0603"))
    )
    (comp (ref "R10")
      (value "R-EU_R0603")
      (footprint "eagle-import:R0603")
      (libsource (lib "eagle-import") (part "R-EU_R0603"))
    )
    (comp (ref "R11")
      (value "R-EU_R0603")
      (footprint "eagle-import:R0603")
      (libsource (lib "eagle-import") (part "R-EU_R0603"))
    )
    (comp (ref "R12")
      (value "R-EU_R0603")
      (footprint "eagle-import:R0603")
      (libsource (lib "eagle-import") (part "R-EU_R0603"))
    )
    (comp (ref "R13")
      (value "R-EU_R0603")
      (footprint "eagle-import:R0603")
      (libsource (lib "eagle-import") (part "R-EU_R0603"))
    )
    (comp (ref "R14")
      (value "R-EU_R0603")
      (footprint "eagle-import:R0603")
      (libsource (lib "eagle-import") (part "R-EU_R0603"))
    )
    (comp (ref "R15")
      (value "R-EU_R0603")
      (footprint "eagle-import:R0603")
      (libsource (lib "eagle-import") (part "R-EU_R0603"))
    )
    (comp (ref "R16")
      (value "R-EU_R0603")
      (footprint "eagle-import:R0603")
      (libsource (lib "eagle-import") (part "R-EU_R0603"))
    )
    (comp (ref "R17")
      (value "R-EU_R0603")
      (footprint "eagle-import:R0603")
      (libsource (lib "eagle-import") (part "R-EU_R0603"))
    )
    (comp (ref "R18")
      (value "R-EU_R0603")
      (footprint "eagle-import:R0603")
      (libsource (lib "eagle-import") (part "R-EU_R0603"))
    )
    (comp (ref "R19")
      (value "R-EU_R0603")
      (footprint "eagle-import:R0603")
      (libsource (lib "eagle-import") (part "R-EU_R0603"))
    )
    (comp (ref "R20")
      (value "R-EU_R0603")
      (footprint "eagle-import:R0603")
      (libsource (lib "eagle-import") (part "R-EU_R0603"))
    )
    (comp (ref "R21")
      (value "R-EU_R0603")
      (footprint "eagle-import:R0603")
      (libsource (lib "eagle-import") (part "R-EU_R0603"))
    )
    (comp (ref "R22")
      (value "R-EU_R0603")
      (footprint "eagle-import:R0603")
      (libsource (lib "eagle-import") (part "R-EU_R0603"))
    )
    (comp (ref "R23")
      (value "R-EU_R0603")
      (footprint "eagle-import:R0603")
      (libsource (lib "eagle-import") (part "R-EU_R0603"))
    )
    (comp (ref "R24")
      (value "R-EU_R0603")
      (footprint "eagle-import:R0603")
      (libsource (lib "eagle-import") (part "R-EU_R0603"))
    )
    (comp (ref "R25")
      (value "R-EU_R0603")
      (footprint "eagle-import:R0603")
      (libsource (lib "eagle-import") (part "R-EU_R0603"))
    )
    (comp (ref "R26")
      (value "R-EU_R0603")
      (footprint "eagle-import:R0603")
      (libsource (lib "eagle-import") (part "R-EU_R0603"))
    )
    (comp (ref "R27")
      (value "R-EU_R0603")
      (footprint "eagle-import:R0603")
      (libsource (lib "eagle-import") (part "R-EU_R0603"))
    )
    (comp (ref "R28")
      (value "R-EU_R0603")
      (footprint "eagle-import:R0603")
      (libsource (lib "eagle-import") (part "R-EU_R0603"))
    )
    (comp (ref "R29")
      (value "R-EU_R0603")
      (footprint "eagle-import:R0603")
      (libsource (lib "eagle-import") (part "R-EU_R0603"))
    )
    (comp (ref "R30")
      (value "R-EU_R0603")
      (footprint "eagle-import:R0603")
      (libsource (lib "eagle-import") (part "R-EU_R0603"))
    )
    (comp (ref "R31")
      (value "R-EU_R0603")
      (footprint "eagle-import:R0603")
      (libsource (lib "eagle-import") (part "R-EU_R0603"))
    )
    (comp (ref "R32")
      (value "R-EU_R0603")
      (footprint "eagle-import:R0603")
      (libsource (lib "eagle-import") (part "R-EU_R0603"))
    )
    (comp (ref "R33")
      (value "R-EU_R0603")
      (footprint "eagle-import:R0603")
      (libsource (lib "eagle-import") (part "R-EU_R0603"))
    )
    (comp (ref "R34")
      (value "R-EU_R0603")
      (footprint "eagle-import:R0603")
      (libsource (lib "eagle-import") (part "R-EU_R0603"))
    )
    (comp (ref "R35")
      (value "R-EU_R0603")
      (footprint "eagle-import:R0603")
      (libsource (lib "eagle-import") (part "R-EU_R0603"))
    )
    (comp (ref "R36")
      (value "4k7")
      (footprint "eagle-import:R0603")
      (libsource (lib "eagle-import") (part "R-EU_R0603"))
    )
    (comp (ref "R37")
      (value "4k7")
      (footprint "eagle-import:R0603")
      (libsource (lib "eagle-import") (part "R-EU_R0603"))
    )
    (comp (ref "R38")
      (value "4k7")
      (footprint "eagle-import:R0603")
      (libsource (lib "eagle-import") (part "R-EU_R0603"))
    )
    (comp (ref "R39")
      (value "4k7")
      (footprint "eagle-import:R0603")
      (libsource (lib "eagle-import") (part "R-EU_R0603"))
    )
    (comp (ref "R40")
      (value "330R")
      (footprint "eagle-import:R0603")
      (libsource (lib "eagle-import") (part "R-EU_R0603"))
    )
    (comp (ref "R41")
      (value "330R")
      (footprint "eagle-import:R0603")
      (libsource (lib "eagle-import") (part "R-EU_R0603"))
    )
    (comp (ref "R42")
      (value "330R")
      (footprint "eagle-import:R0603")
      (libsource (lib "eagle-import") (part "R-EU_R0603"))
    )
    (comp (ref "R43")
      (value "330R")
      (footprint "eagle-import:R0603")
      (libsource (lib "eagle-import") (part "R-EU_R0603"))
    )
    (comp (ref "R44")
      (value "330R")
      (footprint "eagle-import:R0603")
      (libsource (lib "eagle-import") (part "R-EU_R0603"))
    )
    (comp (ref "R45")
      (value "330R")
      (footprint "eagle-import:R0603")
      (libsource (lib "eagle-import") (part "R-EU_R0603"))
    )
    (comp (ref "R46")
      (value "330R")
      (footprint "eagle-import:R0603")
      (libsource (lib "eagle-import") (part "R-EU_R0603"))
    )
    (comp (ref "R47")
      (value "330R")
      (footprint "eagle-import:R0603")
      (libsource (lib "eagle-import") (part "R-EU_R0603"))
    )
    (comp (ref "R48")
      (value "4k7")
      (footprint "eagle-import:R0603")
      (libsource (lib "eagle-import") (part "R-EU_R0603"))
    )
    (comp (ref "R49")
      (value "330R")
      (footprint "eagle-import:R0603")
      (libsource (lib "eagle-import") (part "R-EU_R0603"))
    )
    (comp (ref "R50")
      (value "330R")
      (footprint "eagle-import:R0603")
      (libsource (lib "eagle-import") (part "R-EU_R0603"))
    )
    (comp (ref "R51")
      (value "680")
      (footprint "eagle-import:R0603")
      (libsource (lib "eagle-import") (part "R-EU_R0603"))
    )
    (comp (ref "R52")
      (value "680")
      (footprint "eagle-import:R0603")
      (libsource (lib "eagle-import") (part "R-EU_R0603"))
    )
    (comp (ref "R53")
      (value "4k7")
      (footprint "eagle-import:R0603")
      (libsource (lib "eagle-import") (part "R-EU_R0603"))
    )
    (comp (ref "R54")
      (value "680")
      (footprint "eagle-import:R0603")
      (libsource (lib "eagle-import") (part "R-EU_R0603"))
    )
    (comp (ref "R55")
      (value "10k")
      (footprint "eagle-import:R0603")
      (libsource (lib "eagle-import") (part "R-EU_R0603"))
    )
    (comp (ref "R56")
      (value "4k7")
      (footprint "eagle-import:R0603")
      (libsource (lib "eagle-import") (part "R-EU_R0603"))
    )
    (comp (ref "R57")
      (value "4k7")
      (footprint "eagle-import:R0603")
      (libsource (lib "eagle-import") (part "R-EU_R0603"))
    )
    (comp (ref "R58")
      (value "330R")
      (footprint "eagle-import:R0603")
      (libsource (lib "eagle-import") (part "R-EU_R0603"))
    )
    (comp (ref "R59")
      (value "330R")
      (footprint "eagle-import:R0603")
      (libsource (lib "eagle-import") (part "R-EU_R0603"))
    )
    (comp (ref "R60")
      (value "4k7")
      (footprint "eagle-import:R0603")
      (libsource (lib "eagle-import") (part "R-EU_R0603"))
    )
    (comp (ref "R61")
      (value "330R")
      (footprint "eagle-import:R0603")
      (libsource (lib "eagle-import") (part "R-EU_R0603"))
    )
    (comp (ref "R62")
      (value "330R")
      (footprint "eagle-import:R0603")
      (libsource (lib "eagle-import") (part "R-EU_R0603"))
    )
    (comp (ref "R63")
      (value "4k7")
      (footprint "eagle-import:R0603")
      (libsource (lib "eagle-import") (part "R-EU_R0603"))
    )
    (comp (ref "R64")
      (value "330R")
      (footprint "eagle-import:R0603")
      (libsource (lib "eagle-import") (part "R-EU_R0603"))
    )
    (comp (ref "R65")
      (value "330R")
      (footprint "eagle-import:R0603")
      (libsource (lib "eagle-import") (part "R-EU_R0603"))
    )
    (comp (ref "R66")
      (value "4k7")
      (footprint "eagle-import:R0603")
      (libsource (lib "eagle-import") (part "R-EU_R0603"))
    )
    (comp (ref "R67")
      (value "330R")
      (footprint "eagle-import:R0603")
      (libsource (lib "eagle-import") (part "R-EU_R0603"))
    )
    (comp (ref "R68")
      (value "330R")
      (footprint "eagle-import:R0603")
      (libsource (lib "eagle-import") (part "R-EU_R0603"))
    )
    (comp (ref "R69")
      (value "4k7")
      (footprint "eagle-import:R0603")
      (libsource (lib "eagle-import") (part "R-EU_R0603"))
    )
    (comp (ref "R70")
      (value "330R")
      (footprint "eagle-import:R0603")
      (libsource (lib "eagle-import") (part "R-EU_R0603"))
    )
    (comp (ref "R71")
      (value "330R")
      (footprint "eagle-import:R0603")
      (libsource (lib "eagle-import") (part "R-EU_R0603"))
    )
    (comp (ref "R72")
      (value "4k7")
      (footprint "eagle-import:R0603")
      (libsource (lib "eagle-import") (part "R-EU_R0603"))
    )
    (comp (ref "R73")
      (value "330R")
      (footprint "eagle-import:R0603")
      (libsource (lib "eagle-import") (part "R-EU_R0603"))
    )
    (comp (ref "R74")
      (value "330R")
      (footprint "eagle-import:R0603")
      (libsource (lib "eagle-import") (part "R-EU_R0603"))
    )
    (comp (ref "R75")
      (value "4k7")
      (footprint "eagle-import:R0603")
      (libsource (lib "eagle-import") (part "R-EU_R0603"))
    )
    (comp (ref "R76")
      (value "330R")
      (footprint "eagle-import:R0603")
      (libsource (lib "eagle-import") (part "R-EU_R0603"))
    )
    (comp (ref "R77")
      (value "330R")
      (footprint "eagle-import:R0603")
      (libsource (lib "eagle-import") (part "R-EU_R0603"))
    )
    (comp (ref "R78")
      (value "10R")
      (footprint "eagle-import:R0603")
      (libsource (lib "eagle-import") (part "R-EU_R0603"))
    )
    (comp (ref "R79")
      (value "R-EU_R0603")
      (footprint "eagle-import:R0603")
      (libsource (lib "eagle-import") (part "R-EU_R0603"))
    )
    (comp (ref "R80")
      (value "R-EU_R0603")
      (footprint "eagle-import:R0603")
      (libsource (lib "eagle-import") (part "R-EU_R0603"))
    )
    (comp (ref "R81")
      (value "510R")
      (footprint "eagle-import:R0603")
      (libsource (lib "eagle-import") (part "R-EU_R0603"))
    )
    (comp (ref "R82")
      (value "510R")
      (footprint "eagle-import:R0603")
      (libsource (lib "eagle-import") (part "R-EU_R0603"))
    )
    (comp (ref "R83")
      (value "10K")
      (footprint "eagle-import:R0603")
      (libsource (lib "eagle-import") (part "R-EU_R0603"))
    )
    (comp (ref "R84")
      (value "10K")
      (footprint "eagle-import:R0603")
      (libsource (lib "eagle-import") (part "R-EU_R0603"))
    )
    (comp (ref "R85")
      (value "100R")
      (footprint "eagle-import:R0603")
      (libsource (lib "eagle-import") (part "R-EU_R0603"))
    )
    (comp (ref "R86")
      (value "4k7")
      (footprint "eagle-import:R0603")
      (libsource (lib "eagle-import") (part "R-EU_R0603"))
    )
    (comp (ref "R87")
      (value "100R")
      (footprint "eagle-import:R0603")
      (libsource (lib "eagle-import") (part "R-EU_R0603"))
    )
    (comp (ref "R88")
      (value "4k7")
      (footprint "eagle-import:R0603")
      (libsource (lib "eagle-import") (part "R-EU_R0603"))
    )
    (comp (ref "R89")
      (value "100R")
      (footprint "eagle-import:R0603")
      (libsource (lib "eagle-import") (part "R-EU_R0603"))
    )
    (comp (ref "R90")
      (value "4k7")
      (footprint "eagle-import:R0603")
      (libsource (lib "eagle-import") (part "R-EU_R0603"))
    )
    (comp (ref "R91")
      (value "100R")
      (footprint "eagle-import:R0603")
      (libsource (lib "eagle-import") (part "R-EU_R0603"))
    )
    (comp (ref "R92")
      (value "4k7")
      (footprint "eagle-import:R0603")
      (libsource (lib "eagle-import") (part "R-EU_R0603"))
    )
    (comp (ref "R93")
      (value "100R")
      (footprint "eagle-import:R0603")
      (libsource (lib "eagle-import") (part "R-EU_R0603"))
    )
    (comp (ref "R94")
      (value "4k7")
      (footprint "eagle-import:R0603")
      (libsource (lib "eagle-import") (part "R-EU_R0603"))
    )
    (comp (ref "R95")
      (value "100R")
      (footprint "eagle-import:R0603")
      (libsource (lib "eagle-import") (part "R-EU_R0603"))
    )
    (comp (ref "R96")
      (value "4k7")
      (footprint "eagle-import:R0603")
      (libsource (lib "eagle-import") (part "R-EU_R0603"))
    )
    (comp (ref "R97")
      (value "100R")
      (footprint "eagle-import:R0603")
      (libsource (lib "eagle-import") (part "R-EU_R0603"))
    )
    (comp (ref "R98")
      (value "4k7")
      (footprint "eagle-import:R0603")
      (libsource (lib "eagle-import") (part "R-EU_R0603"))
    )
    (comp (ref "R99")
      (value "100R")
      (footprint "eagle-import:R0603")
      (libsource (lib "eagle-import") (part "R-EU_R0603"))
    )
    (comp (ref "R100")
      (value "4k7")
      (footprint "eagle-import:R0603")
      (libsource (lib "eagle-import") (part "R-EU_R0603"))
    )
    (comp (ref "R101")
      (value "100R")
      (footprint "eagle-import:R0603")
      (libsource (lib "eagle-import") (part "R-EU_R0603"))
    )
    (comp (ref "R102")
      (value "4k7")
      (footprint "eagle-import:R0603")
      (libsource (lib "eagle-import") (part "R-EU_R0603"))
    )
    (comp (ref "R103")
      (value "100R")
      (footprint "eagle-import:R0603")
      (libsource (lib "eagle-import") (part "R-EU_R0603"))
    )
    (comp (ref "R104")
      (value "4k7")
      (footprint "eagle-import:R0603")
      (libsource (lib "eagle-import") (part "R-EU_R0603"))
    )
    (comp (ref "R105")
      (value "100R")
      (footprint "eagle-import:R0603")
      (libsource (lib "eagle-import") (part "R-EU_R0603"))
    )
    (comp (ref "R106")
      (value "4k7")
      (footprint "eagle-import:R0603")
      (libsource (lib "eagle-import") (part "R-EU_R0603"))
    )
    (comp (ref "R107")
      (value "100R")
      (footprint "eagle-import:R0603")
      (libsource (lib "eagle-import") (part "R-EU_R0603"))
    )
    (comp (ref "R108")
      (value "4k7")
      (footprint "eagle-import:R0603")
      (libsource (lib "eagle-import") (part "R-EU_R0603"))
    )
    (comp (ref "R109")
      (value "100R")
      (footprint "eagle-import:R0603")
      (libsource (lib "eagle-import") (part "R-EU_R0603"))
    )
    (comp (ref "R110")
      (value "4k7")
      (footprint "eagle-import:R0603")
      (libsource (lib "eagle-import") (part "R-EU_R0603"))
    )
    (comp (ref "R111")
      (value "100R")
      (footprint "eagle-import:R0603")
      (libsource (lib "eagle-import") (part "R-EU_R0603"))
    )
    (comp (ref "R112")
      (value "4k7")
      (footprint "eagle-import:R0603")
      (libsource (lib "eagle-import") (part "R-EU_R0603"))
    )
    (comp (ref "R113")
      (value "100R")
      (footprint "eagle-import:R0603")
      (libsource (lib "eagle-import") (part "R-EU_R0603"))
    )
    (comp (ref "R114")
      (value "4k7")
      (footprint "eagle-import:R0603")
      (libsource (lib "eagle-import") (part "R-EU_R0603"))
    )
    (comp (ref "R115")
      (value "100R")
      (footprint "eagle-import:R0603")
      (libsource (lib "eagle-import") (part "R-EU_R0603"))
    )
    (comp (ref "R116")
      (value "4k7")
      (footprint "eagle-import:R0603")
      (libsource (lib "eagle-import") (part "R-EU_R0603"))
    )
    (comp (ref "R117")
      (value "100R")
      (footprint "eagle-import:R0603")
      (libsource (lib "eagle-import") (part "R-EU_R0603"))
    )
    (comp (ref "R118")
      (value "4k7")
      (footprint "eagle-import:R0603")
      (libsource (lib "eagle-import") (part "R-EU_R0603"))
    )
    (comp (ref "R119")
      (value "100R")
      (footprint "eagle-import:R0603")
      (libsource (lib "eagle-import") (part "R-EU_R0603"))
    )
    (comp (ref "R120")
      (value "4k7")
      (footprint "eagle-import:R0603")
      (libsource (lib "eagle-import") (part "R-EU_R0603"))
    )
    (comp (ref "R121")
      (value "100R")
      (footprint "eagle-import:R0603")
      (libsource (lib "eagle-import") (part "R-EU_R0603"))
    )
    (comp (ref "R122")
      (value "4k7")
      (footprint "eagle-import:R0603")
      (libsource (lib "eagle-import") (part "R-EU_R0603"))
    )
    (comp (ref "R123")
      (value "100R")
      (footprint "eagle-import:R0603")
      (libsource (lib "eagle-import") (part "R-EU_R0603"))
    )
    (comp (ref "R124")
      (value "4k7")
      (footprint "eagle-import:R0603")
      (libsource (lib "eagle-import") (part "R-EU_R0603"))
    )
    (comp (ref "R125")
      (value "100R")
      (footprint "eagle-import:R0603")
      (libsource (lib "eagle-import") (part "R-EU_R0603"))
    )
    (comp (ref "R126")
      (value "4k7")
      (footprint "eagle-import:R0603")
      (libsource (lib "eagle-import") (part "R-EU_R0603"))
    )
    (comp (ref "R127")
      (value "100R")
      (footprint "eagle-import:R0603")
      (libsource (lib "eagle-import") (part "R-EU_R0603"))
    )
    (comp (ref "R128")
      (value "4k7")
      (footprint "eagle-import:R0603")
      (libsource (lib "eagle-import") (part "R-EU_R0603"))
    )
    (comp (ref "R129")
      (value "100R")
      (footprint "eagle-import:R0603")
      (libsource (lib "eagle-import") (part "R-EU_R0603"))
    )
    (comp (ref "R130")
      (value "4k7")
      (footprint "eagle-import:R0603")
      (libsource (lib "eagle-import") (part "R-EU_R0603"))
    )
    (comp (ref "R131")
      (value "100R")
      (footprint "eagle-import:R0603")
      (libsource (lib "eagle-import") (part "R-EU_R0603"))
    )
    (comp (ref "R132")
      (value "4k7")
      (footprint "eagle-import:R0603")
      (libsource (lib "eagle-import") (part "R-EU_R0603"))
    )
    (comp (ref "R133")
      (value "100R")
      (footprint "eagle-import:R0603")
      (libsource (lib "eagle-import") (part "R-EU_R0603"))
    )
    (comp (ref "R134")
      (value "4k7")
      (footprint "eagle-import:R0603")
      (libsource (lib "eagle-import") (part "R-EU_R0603"))
    )
    (comp (ref "R135")
      (value "100R")
      (footprint "eagle-import:R0603")
      (libsource (lib "eagle-import") (part "R-EU_R0603"))
    )
    (comp (ref "R136")
      (value "4k7")
      (footprint "eagle-import:R0603")
      (libsource (lib "eagle-import") (part "R-EU_R0603"))
    )
    (comp (ref "R137")
      (value "100R")
      (footprint "eagle-import:R0603")
      (libsource (lib "eagle-import") (part "R-EU_R0603"))
    )
    (comp (ref "R138")
      (value "4k7")
      (footprint "eagle-import:R0603")
      (libsource (lib "eagle-import") (part "R-EU_R0603"))
    )
    (comp (ref "R139")
      (value "100R")
      (footprint "eagle-import:R0603")
      (libsource (lib "eagle-import") (part "R-EU_R0603"))
    )
    (comp (ref "R140")
      (value "4k7")
      (footprint "eagle-import:R0603")
      (libsource (lib "eagle-import") (part "R-EU_R0603"))
    )
    (comp (ref "R141")
      (value "100R")
      (footprint "eagle-import:R0603")
      (libsource (lib "eagle-import") (part "R-EU_R0603"))
    )
    (comp (ref "R142")
      (value "4k7")
      (footprint "eagle-import:R0603")
      (libsource (lib "eagle-import") (part "R-EU_R0603"))
    )
    (comp (ref "R143")
      (value "100R")
      (footprint "eagle-import:R0603")
      (libsource (lib "eagle-import") (part "R-EU_R0603"))
    )
    (comp (ref "R144")
      (value "4k7")
      (footprint "eagle-import:R0603")
      (libsource (lib "eagle-import") (part "R-EU_R0603"))
    )
    (comp (ref "R145")
      (value "100R")
      (footprint "eagle-import:R0603")
      (libsource (lib "eagle-import") (part "R-EU_R0603"))
    )
    (comp (ref "R146")
      (value "4k7")
      (footprint "eagle-import:R0603")
      (libsource (lib "eagle-import") (part "R-EU_R0603"))
    )
    (comp (ref "R147")
      (value "100R")
      (footprint "eagle-import:R0603")
      (libsource (lib "eagle-import") (part "R-EU_R0603"))
    )
    (comp (ref "R148")
      (value "4k7")
      (footprint "eagle-import:R0603")
      (libsource (lib "eagle-import") (part "R-EU_R0603"))
    )
    (comp (ref "R149")
      (value "100R")
      (footprint "eagle-import:R0603")
      (libsource (lib "eagle-import") (part "R-EU_R0603"))
    )
    (comp (ref "R150")
      (value "4k7")
      (footprint "eagle-import:R0603")
      (libsource (lib "eagle-import") (part "R-EU_R0603"))
    )
    (comp (ref "R151")
      (value "4k7")
      (footprint "eagle-import:R0603")
      (libsource (lib "eagle-import") (part "R-EU_R0603"))
    )
    (comp (ref "R152")
      (value "4k7")
      (footprint "eagle-import:R0603")
      (libsource (lib "eagle-import") (part "R-EU_R0603"))
    )
    (comp (ref "R153")
      (value "4k7")
      (footprint "eagle-import:R0603")
      (libsource (lib "eagle-import") (part "R-EU_R0603"))
    )
    (comp (ref "R154")
      (value "4k7")
      (footprint "eagle-import:R0603")
      (libsource (lib "eagle-import") (part "R-EU_R0603"))
    )
    (comp (ref "R155")
      (value "4k7")
      (footprint "eagle-import:R0603")
      (libsource (lib "eagle-import") (part "R-EU_R0603"))
    )
    (comp (ref "R156")
      (value "4k7")
      (footprint "eagle-import:R0603")
      (libsource (lib "eagle-import") (part "R-EU_R0603"))
    )
    (comp (ref "R157")
      (value "4k7")
      (footprint "eagle-import:R0603")
      (libsource (lib "eagle-import") (part "R-EU_R0603"))
    )
    (comp (ref "R158")
      (value "4k7")
      (footprint "eagle-import:R0603")
      (libsource (lib "eagle-import") (part "R-EU_R0603"))
    )
    (comp (ref "R159")
      (value "4k7")
      (footprint "eagle-import:R0603")
      (libsource (lib "eagle-import") (part "R-EU_R0603"))
    )
    (comp (ref "R160")
      (value "4k7")
      (footprint "eagle-import:R0603")
      (libsource (lib "eagle-import") (part "R-EU_R0603"))
    )
    (comp (ref "R161")
      (value "4k7")
      (footprint "eagle-import:R0603")
      (libsource (lib "eagle-import") (part "R-EU_R0603"))
    )
    (comp (ref "R162")
      (value "4k7")
      (footprint "eagle-import:R0603")
      (libsource (lib "eagle-import") (part "R-EU_R0603"))
    )
    (comp (ref "R163")
      (value "4k7")
      (footprint "eagle-import:R0805")
      (libsource (lib "eagle-import") (part "R-EU_R0805"))
    )
    (comp (ref "R164")
      (value "4k7")
      (footprint "eagle-import:R0603")
      (libsource (lib "eagle-import") (part "R-EU_R0603"))
    )
    (comp (ref "R165")
      (value "4k7")
      (footprint "eagle-import:R0603")
      (libsource (lib "eagle-import") (part "R-EU_R0603"))
    )
    (comp (ref "R166")
      (value "4k7")
      (footprint "eagle-import:R0603")
      (libsource (lib "eagle-import") (part "R-EU_R0603"))
    )
    (comp (ref "R167")
      (value "4k7")
      (footprint "eagle-import:R0603")
      (libsource (lib "eagle-import") (part "R-EU_R0603"))
    )
    (comp (ref "R168")
      (value "4k7")
      (footprint "eagle-import:R0603")
      (libsource (lib "eagle-import") (part "R-EU_R0603"))
    )
    (comp (ref "R169")
      (value "4k7")
      (footprint "eagle-import:R0603")
      (libsource (lib "eagle-import") (part "R-EU_R0603"))
    )
    (comp (ref "R170")
      (value "4k7")
      (footprint "eagle-import:R0603")
      (libsource (lib "eagle-import") (part "R-EU_R0603"))
    )
    (comp (ref "R171")
      (value "4k7")
      (footprint "eagle-import:R0603")
      (libsource (lib "eagle-import") (part "R-EU_R0603"))
    )
    (comp (ref "R172")
      (value "4k7")
      (footprint "eagle-import:R0603")
      (libsource (lib "eagle-import") (part "R-EU_R0603"))
    )
    (comp (ref "R173")
      (value "4k7")
      (footprint "eagle-import:R0603")
      (libsource (lib "eagle-import") (part "R-EU_R0603"))
    )
    (comp (ref "R174")
      (value "4k7")
      (footprint "eagle-import:R0603")
      (libsource (lib "eagle-import") (part "R-EU_R0603"))
    )
    (comp (ref "R175")
      (value "4k7")
      (footprint "eagle-import:R0603")
      (libsource (lib "eagle-import") (part "R-EU_R0603"))
    )
    (comp (ref "R176")
      (value "4k7")
      (footprint "eagle-import:R0603")
      (libsource (lib "eagle-import") (part "R-EU_R0603"))
    )
    (comp (ref "R177")
      (value "4k7")
      (footprint "eagle-import:R0603")
      (libsource (lib "eagle-import") (part "R-EU_R0603"))
    )
    (comp (ref "R178")
      (value "4k7")
      (footprint "eagle-import:R0603")
      (libsource (lib "eagle-import") (part "R-EU_R0603"))
    )
    (comp (ref "R179")
      (value "4k7")
      (footprint "eagle-import:R0603")
      (libsource (lib "eagle-import") (part "R-EU_R0603"))
    )
    (comp (ref "R180")
      (value "4k7")
      (footprint "eagle-import:R0603")
      (libsource (lib "eagle-import") (part "R-EU_R0603"))
    )
    (comp (ref "R181")
      (value "4k7")
      (footprint "eagle-import:R0603")
      (libsource (lib "eagle-import") (part "R-EU_R0603"))
    )
    (comp (ref "S1")
      (value "SKHMPSE010")
      (footprint "eagle-import:SKHMPXE010")
      (libsource (lib "eagle-import") (part "SKHMPE010S"))
    )
    (comp (ref "SJ1") (value "SJ") (footprint "eagle-import:SJ") (libsource (lib "eagle-import") (part "SJ")))
    (comp (ref "SJ2") (value "SJ") (footprint "eagle-import:SJ") (libsource (lib "eagle-import") (part "SJ")))
    (comp (ref "SJ3") (value "SJ") (footprint "eagle-import:SJ") (libsource (lib "eagle-import") (part "SJ")))
    (comp (ref "SJ4")
      (value "SJ2W")
      (footprint "eagle-import:SJ_2")
      (libsource (lib "eagle-import") (part "SJ2W"))
    )
    (comp (ref "SJ5") (value "SJ") (footprint "eagle-import:SJ") (libsource (lib "eagle-import") (part "SJ")))
    (comp (ref "SJ6") (value "SJ") (footprint "eagle-import:SJ") (libsource (lib "eagle-import") (part "SJ")))
    (comp (ref "SJ7") (value "SJ") (footprint "eagle-import:SJ") (libsource (lib "eagle-import") (part "SJ")))
    (comp (ref "SJ8")
      (value "SJ2W")
      (footprint "eagle-import:SJ_2")
      (libsource (lib "eagle-import") (part "SJ2W"))
    )
    (comp (ref "SJ9") (value "SJ") (footprint "eagle-import:SJ") (libsource (lib "eagle-import") (part "SJ")))
    (comp (ref "SJ10")
      (value "SJ")
      (footprint "eagle-import:SJ")
      (libsource (lib "eagle-import") (part "SJ"))
    )
    (comp (ref "SJ11")
      (value "SJ")
      (footprint "eagle-import:SJ")
      (libsource (lib "eagle-import") (part "SJ"))
    )
    (comp (ref "SJ12")
      (value "SJ2W")
      (footprint "eagle-import:SJ_2")
      (libsource (lib "eagle-import") (part "SJ2W"))
    )
    (comp (ref "SJ13")
      (value "SJ")
      (footprint "eagle-import:SJ")
      (libsource (lib "eagle-import") (part "SJ"))
    )
    (comp (ref "SJ14")
      (value "SJ")
      (footprint "eagle-import:SJ")
      (libsource (lib "eagle-import") (part "SJ"))
    )
    (comp (ref "SJ15")
      (value "SJ")
      (footprint "eagle-import:SJ")
      (libsource (lib "eagle-import") (part "SJ"))
    )
    (comp (ref "SJ16")
      (value "SJ")
      (footprint "eagle-import:SJ")
      (libsource (lib "eagle-import") (part "SJ"))
    )
    (comp (ref "U1")
      (value "PCA9635PW")
      (footprint "eagle-import:SOP65P640X110-28N")
      (libsource (lib "eagle-import") (part "PCA9635PW"))
    )
    (comp (ref "U2")
      (value "PCA9635PW")
      (footprint "eagle-import:SOP65P640X110-28N")
      (libsource (lib "eagle-import") (part "PCA9635PW"))
    )
    (comp (ref "U3")
      (value "CD4051BM")
      (footprint "eagle-import:SOIC127P600X175-16N")
      (libsource (lib "eagle-import") (part "CD4051BM"))
    )
    (comp (ref "U4")
      (value "PCA9635PW")
      (footprint "eagle-import:SOP65P640X110-28N")
      (libsource (lib "eagle-import") (part "PCA9635PW"))
    )
    (comp (ref "U5")
      (value "ULN2803ADWR")
      (footprint "eagle-import:SOIC127P1030X265-18N")
      (libsource (lib "eagle-import") (part "ULN2803ADWR"))
    )
    (comp (ref "U6")
      (value "ULN2803ADWR")
      (footprint "eagle-import:SOIC127P1030X265-18N")
      (libsource (lib "eagle-import") (part "ULN2803ADWR"))
    )
    (comp (ref "U7")
      (value "MCP3008-I/SL")
      (footprint "eagle-import:SOIC127P600X175-16N")
      (libsource (lib "eagle-import") (part "MCP3008-I/SL"))
    )
    (comp (ref "X1")
      (value "2540-")
      (footprint "eagle-import:PAK100_2500-40")
      (libsource (lib "eagle-import") (part "2540-"))
    )
    (comp (ref "X2")
      (value "F09HP")
      (footprint "eagle-import:F09HP")
      (libsource (lib "eagle-import") (part "F09HP"))
    )
    (comp (ref "X3")
      (value "MINI-USB-SCHIELD-32005-301")
      (footprint "eagle-import:32005-301")
      (libsource (lib "eagle-import") (part "MINI-USB-SCHIELD-32005-301"))
    )
  )
  (nets
    (net (code "1") (name "+3V3") (class "Default")
      (node (ref "C24") (pin "1") (pinfunction "1_1") (pintype "passive"))
      (node (ref "C25") (pin "1") (pinfunction "1_1") (pintype "passive"))
      (node (ref "C29") (pin "1") (pinfunction "1_1") (pintype "passive"))
      (node (ref "C30") (pin "1") (pinfunction "1_1") (pintype "passive"))
      (node (ref "C31") (pin "1") (pinfunction "1_1") (pintype "passive"))
      (node (ref "D14") (pin "3") (pinfunction "C_3") (pintype "passive"))
      (node (ref "D16") (pin "C") (pinfunction "C_C") (pintype "passive"))
      (node (ref "IC7") (pin "8") (pinfunction "VCC_8") (pintype "power_in"))
      (node (ref "JP1") (pin "1") (pinfunction "1_1") (pintype "passive"))
      (node (ref "Q1") (pin "3") (pinfunction "G_3") (pintype "passive"))
      (node (ref "Q2") (pin "3") (pinfunction "G_3") (pintype "passive"))
      (node (ref "R38") (pin "2") (pinfunction "2_2") (pintype "passive"))
      (node (ref "R39") (pin "2") (pinfunction "2_2") (pintype "passive"))
      (node (ref "R78") (pin "1") (pinfunction "1_1") (pintype "passive"))
      (node (ref "R80") (pin "2") (pinfunction "2_2") (pintype "passive"))
      (node (ref "R81") (pin "2") (pinfunction "2_2") (pintype "passive"))
      (node (ref "R82") (pin "2") (pinfunction "2_2") (pintype "passive"))
      (node (ref "R83") (pin "1") (pinfunction "1_1") (pintype "passive"))
      (node (ref "X1") (pin "1") (pinfunction "KL_1") (pintype "passive"))
    )
    (net (code "2") (name "+5V") (class "Default")
      (node (ref "C1") (pin "1") (pinfunction "1_1") (pintype "passive"))
      (node (ref "C10") (pin "1") (pinfunction "1_1") (pintype "passive"))
      (node (ref "C11") (pin "1") (pinfunction "1_1") (pintype "passive"))
      (node (ref "C12") (pin "1") (pinfunction "1_1") (pintype "passive"))
      (node (ref "C15") (pin "1") (pinfunction "1_1") (pintype "passive"))
      (node (ref "C16") (pin "1") (pinfunction "1_1") (pintype "passive"))
      (node (ref "C17") (pin "1") (pinfunction "1_1") (pintype "passive"))
      (node (ref "C2") (pin "1") (pinfunction "1_1") (pintype "passive"))
      (node (ref "C20") (pin "1") (pinfunction "1_1") (pintype "passive"))
      (node (ref "C21") (pin "1") (pinfunction "1_1") (pintype "passive"))
      (node (ref "C22") (pin "1") (pinfunction "1_1") (pintype "passive"))
      (node (ref "C23") (pin "1") (pinfunction "1_1") (pintype "passive"))
      (node (ref "C26") (pin "1") (pinfunction "1_1") (pintype "passive"))
      (node (ref "C27") (pin "1") (pinfunction "1_1") (pintype "passive"))
      (node (ref "C28") (pin "1") (pinfunction "1_1") (pintype "passive"))
      (node (ref "C3") (pin "1") (pinfunction "1_1") (pintype "passive"))
      (node (ref "C4") (pin "1") (pinfunction "1_1") (pintype "passive"))
      (node (ref "C5") (pin "1") (pinfunction "1_1") (pintype "passive"))
      (node (ref "C6") (pin "1") (pinfunction "1_1") (pintype "passive"))
      (node (ref "C9") (pin "2") (pinfunction "2_2") (pintype "passive"))
      (node (ref "D15") (pin "3") (pinfunction "C_3") (pintype "passive"))
      (node (ref "D17") (pin "C") (pinfunction "C_C") (pintype "passive"))
      (node (ref "IC2") (pin "14") (pinfunction "VCC_14") (pintype "power_in"))
      (node (ref "IC3") (pin "14") (pinfunction "VCC_14") (pintype "power_in"))
      (node (ref "IC4") (pin "18") (pinfunction "AVCC_18") (pintype "power_in"))
      (node (ref "IC4") (pin "4") (pinfunction "VCC_4") (pintype "power_in"))
      (node (ref "IC4") (pin "6") (pinfunction "VCC_6") (pintype "power_in"))
      (node (ref "IC5") (pin "20") (pinfunction "VCC_20") (pintype "power_in"))
      (node (ref "IC5") (pin "4") (pinfunction "VCCIO_4") (pintype "power_in"))
      (node (ref "IC6") (pin "4") (pinfunction "V+_4") (pintype "power_in"))
      (node (ref "IC8") (pin "4") (pinfunction "V+_4") (pintype "power_in"))
      (node (ref "JP1") (pin "3") (pinfunction "3_3") (pintype "passive"))
      (node (ref "R1") (pin "1") (pinfunction "1_1") (pintype "passive"))
      (node (ref "R10") (pin "1") (pinfunction "1_1") (pintype "passive"))
      (node (ref "R11") (pin "1") (pinfunction "1_1") (pintype "passive"))
      (node (ref "R12") (pin "1") (pinfunction "1_1") (pintype "passive"))
      (node (ref "R13") (pin "1") (pinfunction "1_1") (pintype "passive"))
      (node (ref "R14") (pin "1") (pinfunction "1_1") (pintype "passive"))
      (node (ref "R15") (pin "1") (pinfunction "1_1") (pintype "passive"))
      (node (ref "R16") (pin "1") (pinfunction "1_1") (pintype "passive"))
      (node (ref "R17") (pin "1") (pinfunction "1_1") (pintype "passive"))
      (node (ref "R18") (pin "1") (pinfunction "1_1") (pintype "passive"))
      (node (ref "R19") (pin "1") (pinfunction "1_1") (pintype "passive"))
      (node (ref "R2") (pin "1") (pinfunction "1_1") (pintype "passive"))
      (node (ref "R20") (pin "1") (pinfunction "1_1") (pintype "passive"))
      (node (ref "R21") (pin "1") (pinfunction "1_1") (pintype "passive"))
      (node (ref "R22") (pin "1") (pinfunction "1_1") (pintype "passive"))
      (node (ref "R23") (pin "1") (pinfunction "1_1") (pintype "passive"))
      (node (ref "R24") (pin "1") (pinfunction "1_1") (pintype "passive"))
      (node (ref "R3") (pin "1") (pinfunction "1_1") (pintype "passive"))
      (node (ref "R36") (pin "2") (pinfunction "2_2") (pintype "passive"))
      (node (ref "R37") (pin "2") (pinfunction "2_2") (pintype "passive"))
      (node (ref "R4") (pin "1") (pinfunction "1_1") (pintype "passive"))
      (node (ref "R5") (pin "1") (pinfunction "1_1") (pintype "passive"))
      (node (ref "R51") (pin "1") (pinfunction "1_1") (pintype "passive"))
      (node (ref "R52") (pin "1") (pinfunction "1_1") (pintype "passive"))
      (node (ref "R55") (pin "1") (pinfunction "1_1") (pintype "passive"))
      (node (ref "R56") (pin "1") (pinfunction "1_1") (pintype "passive"))
      (node (ref "R6") (pin "1") (pinfunction "1_1") (pintype "passive"))
      (node (ref "R7") (pin "1") (pinfunction "1_1") (pintype "passive"))
      (node (ref "R8") (pin "1") (pinfunction "1_1") (pintype "passive"))
      (node (ref "R9") (pin "1") (pinfunction "1_1") (pintype "passive"))
      (node (ref "U1") (pin "28") (pinfunction "VDD_28") (pintype "power_in"))
      (node (ref "U2") (pin "28") (pinfunction "VDD_28") (pintype "power_in"))
      (node (ref "U3") (pin "16") (pinfunction "VDD_16") (pintype "input"))
      (node (ref "U4") (pin "28") (pinfunction "VDD_28") (pintype "power_in"))
      (node (ref "X1") (pin "2") (pinfunction "KL_2") (pintype "passive"))
      (node (ref "X1") (pin "4") (pinfunction "KL_4") (pintype "passive"))
      (node (ref "X3") (pin "1") (pinfunction "1_1") (pintype "passive"))
    )
    (net (code "3") (name "/0{slash}RXD") (class "Default")
      (node (ref "IC2") (pin "1") (pinfunction "I0_1") (pintype "input"))
      (node (ref "IC4") (pin "30") (pinfunction "PD0(RXD)_30") (pintype "bidirectional"))
      (node (ref "IC5") (pin "1") (pinfunction "TXD_1") (pintype "output"))
    )
    (net (code "4") (name "/1{slash}TXD") (class "Default")
      (node (ref "IC2") (pin "4") (pinfunction "I0_4") (pintype "input"))
      (node (ref "IC4") (pin "31") (pinfunction "PD1(TXD)_31") (pintype "bidirectional"))
      (node (ref "IC5") (pin "5") (pinfunction "RXD_5") (pintype "input"))
    )
    (net (code "5") (name "/2") (class "Default")
      (node (ref "IC2") (pin "9") (pinfunction "I0_9") (pintype "input"))
      (node (ref "IC4") (pin "32") (pinfunction "PD2(INT0)_32") (pintype "bidirectional"))
    )
    (net (code "6") (name "/3") (class "Default")
      (node (ref "IC2") (pin "12") (pinfunction "I0_12") (pintype "input"))
      (node (ref "IC4") (pin "1") (pinfunction "PD3(INT1)_1") (pintype "bidirectional"))
    )
    (net (code "7") (name "/3.3V") (class "Default")
      (node (ref "C7") (pin "1") (pinfunction "1_1") (pintype "passive"))
      (node (ref "C8") (pin "1") (pinfunction "1_1") (pintype "passive"))
      (node (ref "IC1") (pin "9") (pinfunction "VDD_9") (pintype "power_in"))
      (node (ref "R25") (pin "1") (pinfunction "1_1") (pintype "passive"))
      (node (ref "R26") (pin "1") (pinfunction "1_1") (pintype "passive"))
      (node (ref "R27") (pin "1") (pinfunction "1_1") (pintype "passive"))
      (node (ref "X1") (pin "17") (pinfunction "KL_17") (pintype "passive"))
    )
    (net (code "8") (name "/4") (class "Default")
      (node (ref "IC3") (pin "1") (pinfunction "I0_1") (pintype "input"))
      (node (ref "IC4") (pin "2") (pinfunction "PD4(XCK/T0)_2") (pintype "bidirectional"))
    )
    (net (code "9") (name "/5") (class "Default")
      (node (ref "IC3") (pin "4") (pinfunction "I0_4") (pintype "input"))
      (node (ref "IC4") (pin "9") (pinfunction "PD5(T1)_9") (pintype "bidirectional"))
    )
    (net (code "10") (name "/6") (class "Default")
      (node (ref "IC3") (pin "9") (pinfunction "I0_9") (pintype "input"))
      (node (ref "IC4") (pin "10") (pinfunction "PD6(AIN0)_10") (pintype "bidirectional"))
    )
    (net (code "11") (name "/7") (class "Default")
      (node (ref "IC3") (pin "12") (pinfunction "I0_12") (pintype "input"))
      (node (ref "IC4") (pin "11") (pinfunction "PD7(AIN1)_11") (pintype "bidirectional"))
    )
    (net (code "12") (name "/8") (class "Default")
      (node (ref "IC4") (pin "12") (pinfunction "PB0(ICP)_12") (pintype "bidirectional"))
      (node (ref "U3") (pin "11") (pinfunction "A_11") (pintype "input"))
    )
    (net (code "13") (name "/9") (class "Default")
      (node (ref "IC4") (pin "13") (pinfunction "PB1(OC1A)_13") (pintype "bidirectional"))
      (node (ref "U3") (pin "10") (pinfunction "B_10") (pintype "input"))
    )
    (net (code "14") (name "/10") (class "Default")
      (node (ref "IC4") (pin "14") (pinfunction "PB2(SS/OC1B)_14") (pintype "bidirectional"))
      (node (ref "U3") (pin "9") (pinfunction "C_9") (pintype "bidirectional"))
    )
    (net (code "15") (name "/11{slash}MOSI") (class "Default")
      (node (ref "IC4") (pin "15") (pinfunction "PB3(MOSI/OC2)_15") (pintype "bidirectional"))
    )
    (net (code "16") (name "/12{slash}MISO") (class "Default")
      (node (ref "IC4") (pin "16") (pinfunction "PB4(MISO)_16") (pintype "bidirectional"))
    )
    (net (code "17") (name "/13{slash}SCK") (class "Default")
      (node (ref "IC4") (pin "17") (pinfunction "PB5(SCK)_17") (pintype "bidirectional"))
      (node (ref "LED3") (pin "A") (pinfunction "A_A") (pintype "passive"))
    )
    (net (code "18") (name "/A") (class "Default")
      (node (ref "IC7") (pin "6") (pinfunction "A_6") (pintype "passive"))
      (node (ref "R83") (pin "2") (pinfunction "2_2") (pintype "passive"))
      (node (ref "X2") (pin "2") (pinfunction "2_2") (pintype "passive"))
    )
    (net (code "19") (name "/AD1") (class "Default")
      (node (ref "R40") (pin "2") (pinfunction "2_2") (pintype "passive"))
      (node (ref "U7") (pin "1") (pinfunction "CH0_1") (pintype "input"))
    )
    (net (code "20") (name "/AD2") (class "Default")
      (node (ref "R41") (pin "2") (pinfunction "2_2") (pintype "passive"))
      (node (ref "U7") (pin "2") (pinfunction "CH1_2") (pintype "input"))
    )
    (net (code "21") (name "/AD3") (class "Default")
      (node (ref "R42") (pin "2") (pinfunction "2_2") (pintype "passive"))
      (node (ref "U7") (pin "3") (pinfunction "CH2_3") (pintype "input"))
    )
    (net (code "22") (name "/AD4") (class "Default")
      (node (ref "R43") (pin "2") (pinfunction "2_2") (pintype "passive"))
      (node (ref "U7") (pin "4") (pinfunction "CH3_4") (pintype "input"))
    )
    (net (code "23") (name "/AD5") (class "Default")
      (node (ref "R44") (pin "2") (pinfunction "2_2") (pintype "passive"))
      (node (ref "U7") (pin "5") (pinfunction "CH4_5") (pintype "input"))
    )
    (net (code "24") (name "/AD6") (class "Default")
      (node (ref "R45") (pin "2") (pinfunction "2_2") (pintype "passive"))
      (node (ref "U7") (pin "6") (pinfunction "CH5_6") (pintype "input"))
    )
    (net (code "25") (name "/AD7") (class "Default")
      (node (ref "R46") (pin "2") (pinfunction "2_2") (pintype "passive"))
      (node (ref "U7") (pin "7") (pinfunction "CH6_7") (pintype "input"))
    )
    (net (code "26") (name "/AD8") (class "Default")
      (node (ref "R47") (pin "2") (pinfunction "2_2") (pintype "passive"))
      (node (ref "U7") (pin "8") (pinfunction "CH7_8") (pintype "input"))
    )
    (net (code "27") (name "/ADC0") (class "Default")
      (node (ref "IC4") (pin "23") (pinfunction "PC0(ADC0)_23") (pintype "bidirectional"))
      (node (ref "U3") (pin "3") (pinfunction "COM_OUT/IN_3") (pintype "bidirectional"))
    )
    (net (code "28") (name "/ADC1") (class "Default")
      (node (ref "IC4") (pin "24") (pinfunction "PC1(ADC1)_24") (pintype "bidirectional"))
    )
    (net (code "29") (name "/ADC2") (class "Default")
      (node (ref "IC4") (pin "25") (pinfunction "PC2(ADC2)_25") (pintype "bidirectional"))
    )
    (net (code "30") (name "/ADC3") (class "Default")
      (node (ref "IC4") (pin "26") (pinfunction "PC3(ADC3)_26") (pintype "bidirectional"))
    )
    (net (code "31") (name "/ADIN1") (class "Default")
      (node (ref "D5") (pin "3") (pinfunction "C_3") (pintype "passive"))
      (node (ref "PAD56") (pin "1") (pinfunction "P_1") (pintype "passive"))
      (node (ref "R40") (pin "1") (pinfunction "1_1") (pintype "passive"))
    )
    (net (code "32") (name "/ADIN2") (class "Default")
      (node (ref "D6") (pin "3") (pinfunction "C_3") (pintype "passive"))
      (node (ref "PAD57") (pin "1") (pinfunction "P_1") (pintype "passive"))
      (node (ref "R41") (pin "1") (pinfunction "1_1") (pintype "passive"))
    )
    (net (code "33") (name "/ADIN3") (class "Default")
      (node (ref "D7") (pin "3") (pinfunction "C_3") (pintype "passive"))
      (node (ref "PAD58") (pin "1") (pinfunction "P_1") (pintype "passive"))
      (node (ref "R42") (pin "1") (pinfunction "1_1") (pintype "passive"))
    )
    (net (code "34") (name "/ADIN4") (class "Default")
      (node (ref "D8") (pin "3") (pinfunction "C_3") (pintype "passive"))
      (node (ref "PAD59") (pin "1") (pinfunction "P_1") (pintype "passive"))
      (node (ref "R43") (pin "1") (pinfunction "1_1") (pintype "passive"))
    )
    (net (code "35") (name "/ADIN5") (class "Default")
      (node (ref "D9") (pin "3") (pinfunction "C_3") (pintype "passive"))
      (node (ref "PAD60") (pin "1") (pinfunction "P_1") (pintype "passive"))
      (node (ref "R44") (pin "1") (pinfunction "1_1") (pintype "passive"))
    )
    (net (code "36") (name "/ADIN6") (class "Default")
      (node (ref "D10") (pin "3") (pinfunction "C_3") (pintype "passive"))
      (node (ref "PAD61") (pin "1") (pinfunction "P_1") (pintype "passive"))
      (node (ref "R45") (pin "1") (pinfunction "1_1") (pintype "passive"))
    )
    (net (code "37") (name "/ADIN7") (class "Default")
      (node (ref "D11") (pin "3") (pinfunction "C_3") (pintype "passive"))
      (node (ref "PAD62") (pin "1") (pinfunction "P_1") (pintype "passive"))
      (node (ref "R46") (pin "1") (pinfunction "1_1") (pintype "passive"))
    )
    (net (code "38") (name "/ADIN8") (class "Default")
      (node (ref "D12") (pin "3") (pinfunction "C_3") (pintype "passive"))
      (node (ref "PAD63") (pin "1") (pinfunction "P_1") (pintype "passive"))
      (node (ref "R47") (pin "1") (pinfunction "1_1") (pintype "passive"))
    )
    (net (code "39") (name "/B") (class "Default")
      (node (ref "IC7") (pin "7") (pinfunction "B_7") (pintype "passive"))
      (node (ref "R84") (pin "2") (pinfunction "2_2") (pintype "passive"))
      (node (ref "X2") (pin "3") (pinfunction "3_3") (pintype "passive"))
    )
    (net (code "40") (name "/D+") (class "Default")
      (node (ref "IC5") (pin "15") (pinfunction "USBDP_15") (pintype "bidirectional"))
      (node (ref "X3") (pin "3") (pinfunction "3_3") (pintype "passive"))
    )
    (net (code "41") (name "/D-") (class "Default")
      (node (ref "IC5") (pin "16") (pinfunction "USBDM_16") (pintype "bidirectional"))
      (node (ref "X3") (pin "2") (pinfunction "2_2") (pintype "passive"))
    )
    (net (code "42") (name "/GPCLK0") (class "Default")
      (node (ref "X1") (pin "7") (pinfunction "KL_7") (pintype "passive"))
    )
    (net (code "43") (name "/GPIO5") (class "Default")
      (node (ref "X1") (pin "29") (pinfunction "KL_29") (pintype "passive"))
    )
    (net (code "44") (name "/GPIO6") (class "Default")
      (node (ref "X1") (pin "31") (pinfunction "KL_31") (pintype "passive"))
    )
    (net (code "45") (name "/GPIO12") (class "Default")
      (node (ref "X1") (pin "32") (pinfunction "KL_32") (pintype "passive"))
    )
    (net (code "46") (name "/GPIO13") (class "Default")
      (node (ref "X1") (pin "33") (pinfunction "KL_33") (pintype "passive"))
    )
    (net (code "47") (name "/GPIO16") (class "Default")
      (node (ref "X1") (pin "36") (pinfunction "KL_36") (pintype "passive"))
    )
    (net (code "48") (name "/GPIO17") (class "Default")
      (node (ref "X1") (pin "11") (pinfunction "KL_11") (pintype "passive"))
    )
    (net (code "49") (name "/GPIO18") (class "Default")
      (node (ref "X1") (pin "12") (pinfunction "KL_12") (pintype "passive"))
    )
    (net (code "50") (name "/GPIO19") (class "Default")
      (node (ref "X1") (pin "35") (pinfunction "KL_35") (pintype "passive"))
    )
    (net (code "51") (name "/GPIO20") (class "Default")
      (node (ref "X1") (pin "38") (pinfunction "KL_38") (pintype "passive"))
    )
    (net (code "52") (name "/GPIO21") (class "Default")
      (node (ref "X1") (pin "40") (pinfunction "KL_40") (pintype "passive"))
    )
    (net (code "53") (name "/GPIO22") (class "Default")
      (node (ref "IC1") (pin "18") (pinfunction "~{RESET}_18") (pintype "input"))
      (node (ref "X1") (pin "15") (pinfunction "KL_15") (pintype "passive"))
    )
    (net (code "54") (name "/GPIO23") (class "Default")
      (node (ref "X1") (pin "16") (pinfunction "KL_16") (pintype "passive"))
    )
    (net (code "55") (name "/GPIO24") (class "Default")
      (node (ref "IC1") (pin "20") (pinfunction "INTA_20") (pintype "output"))
      (node (ref "X1") (pin "18") (pinfunction "KL_18") (pintype "passive"))
    )
    (net (code "56") (name "/GPIO25") (class "Default")
      (node (ref "IC1") (pin "19") (pinfunction "INTB_19") (pintype "output"))
      (node (ref "X1") (pin "22") (pinfunction "KL_22") (pintype "passive"))
    )
    (net (code "57") (name "/GPIO26") (class "Default")
      (node (ref "X1") (pin "37") (pinfunction "KL_37") (pintype "passive"))
    )
    (net (code "58") (name "/GPIO27") (class "Default")
      (node (ref "X1") (pin "13") (pinfunction "KL_13") (pintype "passive"))
    )
    (net (code "59") (name "/HL1") (class "Default")
      (node (ref "IC2") (pin "2") (pinfunction "I1_2") (pintype "input"))
      (node (ref "U1") (pin "6") (pinfunction "LED0_6") (pintype "output"))
    )
    (net (code "60") (name "/HL2") (class "Default")
      (node (ref "IC2") (pin "5") (pinfunction "I1_5") (pintype "input"))
      (node (ref "U1") (pin "7") (pinfunction "LED1_7") (pintype "output"))
    )
    (net (code "61") (name "/HL3") (class "Default")
      (node (ref "IC2") (pin "10") (pinfunction "I1_10") (pintype "input"))
      (node (ref "U1") (pin "8") (pinfunction "LED2_8") (pintype "output"))
    )
    (net (code "62") (name "/HL4") (class "Default")
      (node (ref "IC2") (pin "13") (pinfunction "I1_13") (pintype "input"))
      (node (ref "U1") (pin "9") (pinfunction "LED3_9") (pintype "output"))
    )
    (net (code "63") (name "/HL5") (class "Default")
      (node (ref "IC3") (pin "2") (pinfunction "I1_2") (pintype "input"))
      (node (ref "U1") (pin "10") (pinfunction "LED4_10") (pintype "output"))
    )
    (net (code "64") (name "/HL6") (class "Default")
      (node (ref "IC3") (pin "5") (pinfunction "I1_5") (pintype "input"))
      (node (ref "U1") (pin "11") (pinfunction "LED5_11") (pintype "output"))
    )
    (net (code "65") (name "/HL7") (class "Default")
      (node (ref "IC3") (pin "10") (pinfunction "I1_10") (pintype "input"))
      (node (ref "U1") (pin "12") (pinfunction "LED6_12") (pintype "output"))
    )
    (net (code "66") (name "/HL8") (class "Default")
      (node (ref "IC3") (pin "13") (pinfunction "I1_13") (pintype "input"))
      (node (ref "U1") (pin "13") (pinfunction "LED7_13") (pintype "output"))
    )
    (net (code "67") (name "/ID_SC") (class "Default")
      (node (ref "X1") (pin "28") (pinfunction "KL_28") (pintype "passive"))
    )
    (net (code "68") (name "/ID_SD") (class "Default")
      (node (ref "X1") (pin "27") (pinfunction "KL_27") (pintype "passive"))
    )
    (net (code "69") (name "/INPUTK1") (class "Default")
      (node (ref "PAD76") (pin "1") (pinfunction "P_1") (pintype "passive"))
      (node (ref "R32") (pin "2") (pinfunction "2_2") (pintype "passive"))
    )
    (net (code "70") (name "/INPUTK2") (class "Default")
      (node (ref "PAD77") (pin "1") (pinfunction "P_1") (pintype "passive"))
      (node (ref "R33") (pin "2") (pinfunction "2_2") (pintype "passive"))
    )
    (net (code "71") (name "/INPUTK3") (class "Default")
      (node (ref "PAD78") (pin "1") (pinfunction "P_1") (pintype "passive"))
      (node (ref "R34") (pin "2") (pinfunction "2_2") (pintype "passive"))
    )
    (net (code "72") (name "/INPUTK4") (class "Default")
      (node (ref "PAD79") (pin "1") (pinfunction "P_1") (pintype "passive"))
      (node (ref "R35") (pin "2") (pinfunction "2_2") (pintype "passive"))
    )
    (net (code "73") (name "/OE1") (class "Default")
      (node (ref "SJ4") (pin "2") (pinfunction "2_2") (pintype "passive"))
      (node (ref "U1") (pin "23") (pinfunction "~{OE}_23") (pintype "input"))
    )
    (net (code "74") (name "/OE2") (class "Default")
      (node (ref "SJ8") (pin "2") (pinfunction "2_2") (pintype "passive"))
      (node (ref "U2") (pin "23") (pinfunction "~{OE}_23") (pintype "input"))
    )
    (net (code "75") (name "/OE3") (class "Default")
      (node (ref "SJ12") (pin "2") (pinfunction "2_2") (pintype "passive"))
      (node (ref "U4") (pin "23") (pinfunction "~{OE}_23") (pintype "input"))
    )
    (net (code "76") (name "/OFFEN1") (class "Default")
      (node (ref "PAD42") (pin "1") (pinfunction "P_1") (pintype "passive"))
      (node (ref "U1") (pin "18") (pinfunction "LED11_18") (pintype "output"))
    )
    (net (code "77") (name "/OFFEN2") (class "Default")
      (node (ref "PAD43") (pin "1") (pinfunction "P_1") (pintype "passive"))
      (node (ref "U1") (pin "19") (pinfunction "LED12_19") (pintype "output"))
    )
    (net (code "78") (name "/OFFEN3") (class "Default")
      (node (ref "PAD44") (pin "1") (pinfunction "P_1") (pintype "passive"))
      (node (ref "U1") (pin "20") (pinfunction "LED13_20") (pintype "output"))
    )
    (net (code "79") (name "/OFFEN4") (class "Default")
      (node (ref "PAD45") (pin "1") (pinfunction "P_1") (pintype "passive"))
      (node (ref "U1") (pin "21") (pinfunction "LED14_21") (pintype "output"))
    )
    (net (code "80") (name "/OFFEN5") (class "Default")
      (node (ref "PAD46") (pin "1") (pinfunction "P_1") (pintype "passive"))
      (node (ref "U1") (pin "22") (pinfunction "LED15_22") (pintype "output"))
    )
    (net (code "81") (name "/REF") (class "Default")
      (node (ref "JP1") (pin "2") (pinfunction "2_2") (pintype "passive"))
      (node (ref "R151") (pin "2") (pinfunction "2_2") (pintype "passive"))
      (node (ref "R155") (pin "2") (pinfunction "2_2") (pintype "passive"))
      (node (ref "R159") (pin "2") (pinfunction "2_2") (pintype "passive"))
      (node (ref "R163") (pin "2") (pinfunction "2_2") (pintype "passive"))
      (node (ref "R167") (pin "2") (pinfunction "2_2") (pintype "passive"))
      (node (ref "R171") (pin "2") (pinfunction "2_2") (pintype "passive"))
      (node (ref "R175") (pin "2") (pinfunction "2_2") (pintype "passive"))
      (node (ref "R179") (pin "2") (pinfunction "2_2") (pintype "passive"))
    )
    (net (code "82") (name "/RGB1.1") (class "Default")
      (node (ref "R133") (pin "2") (pinfunction "2_2") (pintype "passive"))
      (node (ref "U2") (pin "21") (pinfunction "LED14_21") (pintype "output"))
    )
    (net (code "83") (name "/RGB1.2") (class "Default")
      (node (ref "R135") (pin "2") (pinfunction "2_2") (pintype "passive"))
      (node (ref "U2") (pin "20") (pinfunction "LED13_20") (pintype "output"))
    )
    (net (code "84") (name "/RGB1.3") (class "Default")
      (node (ref "R137") (pin "2") (pinfunction "2_2") (pintype "passive"))
      (node (ref "U2") (pin "19") (pinfunction "LED12_19") (pintype "output"))
    )
    (net (code "85") (name "/RGB2.1") (class "Default")
      (node (ref "R139") (pin "2") (pinfunction "2_2") (pintype "passive"))
      (node (ref "U2") (pin "18") (pinfunction "LED11_18") (pintype "output"))
    )
    (net (code "86") (name "/RGB2.2") (class "Default")
      (node (ref "R141") (pin "2") (pinfunction "2_2") (pintype "passive"))
      (node (ref "U2") (pin "17") (pinfunction "LED10_17") (pintype "output"))
    )
    (net (code "87") (name "/RGB2.3") (class "Default")
      (node (ref "R143") (pin "2") (pinfunction "2_2") (pintype "passive"))
      (node (ref "U2") (pin "16") (pinfunction "LED9_16") (pintype "output"))
    )
    (net (code "88") (name "/RGB3.1") (class "Default")
      (node (ref "R121") (pin "2") (pinfunction "2_2") (pintype "passive"))
      (node (ref "U2") (pin "15") (pinfunction "LED8_15") (pintype "output"))
    )
    (net (code "89") (name "/RGB3.2") (class "Default")
      (node (ref "R123") (pin "2") (pinfunction "2_2") (pintype "passive"))
      (node (ref "U2") (pin "13") (pinfunction "LED7_13") (pintype "output"))
    )
    (net (code "90") (name "/RGB3.3") (class "Default")
      (node (ref "R125") (pin "2") (pinfunction "2_2") (pintype "passive"))
      (node (ref "U2") (pin "12") (pinfunction "LED6_12") (pintype "output"))
    )
    (net (code "91") (name "/RGB4.1") (class "Default")
      (node (ref "R127") (pin "2") (pinfunction "2_2") (pintype "passive"))
      (node (ref "U2") (pin "11") (pinfunction "LED5_11") (pintype "output"))
    )
    (net (code "92") (name "/RGB4.2") (class "Default")
      (node (ref "R129") (pin "2") (pinfunction "2_2") (pintype "passive"))
      (node (ref "U2") (pin "10") (pinfunction "LED4_10") (pintype "output"))
    )
    (net (code "93") (name "/RGB4.3") (class "Default")
      (node (ref "R131") (pin "2") (pinfunction "2_2") (pintype "passive"))
      (node (ref "U2") (pin "9") (pinfunction "LED3_9") (pintype "output"))
    )
    (net (code "94") (name "/RGB5.1") (class "Default")
      (node (ref "R109") (pin "2") (pinfunction "2_2") (pintype "passive"))
      (node (ref "U2") (pin "8") (pinfunction "LED2_8") (pintype "output"))
    )
    (net (code "95") (name "/RGB5.2") (class "Default")
      (node (ref "R111") (pin "2") (pinfunction "2_2") (pintype "passive"))
      (node (ref "U2") (pin "7") (pinfunction "LED1_7") (pintype "output"))
    )
    (net (code "96") (name "/RGB5.3") (class "Default")
      (node (ref "R113") (pin "2") (pinfunction "2_2") (pintype "passive"))
      (node (ref "U2") (pin "6") (pinfunction "LED0_6") (pintype "output"))
    )
    (net (code "97") (name "/RGB6.1") (class "Default")
      (node (ref "R115") (pin "2") (pinfunction "2_2") (pintype "passive"))
      (node (ref "U4") (pin "21") (pinfunction "LED14_21") (pintype "output"))
    )
    (net (code "98") (name "/RGB6.2") (class "Default")
      (node (ref "R117") (pin "2") (pinfunction "2_2") (pintype "passive"))
      (node (ref "U4") (pin "20") (pinfunction "LED13_20") (pintype "output"))
    )
    (net (code "99") (name "/RGB6.3") (class "Default")
      (node (ref "R119") (pin "2") (pinfunction "2_2") (pintype "passive"))
      (node (ref "U4") (pin "19") (pinfunction "LED12_19") (pintype "output"))
    )
    (net (code "100") (name "/RGB7.1") (class "Default")
      (node (ref "R97") (pin "2") (pinfunction "2_2") (pintype "passive"))
      (node (ref "U4") (pin "18") (pinfunction "LED11_18") (pintype "output"))
    )
    (net (code "101") (name "/RGB7.2") (class "Default")
      (node (ref "R99") (pin "2") (pinfunction "2_2") (pintype "passive"))
      (node (ref "U4") (pin "17") (pinfunction "LED10_17") (pintype "output"))
    )
    (net (code "102") (name "/RGB7.3") (class "Default")
      (node (ref "R101") (pin "2") (pinfunction "2_2") (pintype "passive"))
      (node (ref "U4") (pin "16") (pinfunction "LED9_16") (pintype "output"))
    )
    (net (code "103") (name "/RGB8.1") (class "Default")
      (node (ref "R103") (pin "2") (pinfunction "2_2") (pintype "passive"))
      (node (ref "U4") (pin "15") (pinfunction "LED8_15") (pintype "output"))
    )
    (net (code "104") (name "/RGB8.2") (class "Default")
      (node (ref "R105") (pin "2") (pinfunction "2_2") (pintype "passive"))
      (node (ref "U4") (pin "13") (pinfunction "LED7_13") (pintype "output"))
    )
    (net (code "105") (name "/RGB8.3") (class "Default")
      (node (ref "R107") (pin "2") (pinfunction "2_2") (pintype "passive"))
      (node (ref "U4") (pin "12") (pinfunction "LED6_12") (pintype "output"))
    )
    (net (code "106") (name "/RGB9.1") (class "Default")
      (node (ref "R85") (pin "2") (pinfunction "2_2") (pintype "passive"))
      (node (ref "U4") (pin "11") (pinfunction "LED5_11") (pintype "output"))
    )
    (net (code "107") (name "/RGB9.2") (class "Default")
      (node (ref "R87") (pin "2") (pinfunction "2_2") (pintype "passive"))
      (node (ref "U4") (pin "10") (pinfunction "LED4_10") (pintype "output"))
    )
    (net (code "108") (name "/RGB9.3") (class "Default")
      (node (ref "R89") (pin "2") (pinfunction "2_2") (pintype "passive"))
      (node (ref "U4") (pin "9") (pinfunction "LED3_9") (pintype "output"))
    )
    (net (code "109") (name "/RGB10.1") (class "Default")
      (node (ref "R91") (pin "2") (pinfunction "2_2") (pintype "passive"))
      (node (ref "U4") (pin "8") (pinfunction "LED2_8") (pintype "output"))
    )
    (net (code "110") (name "/RGB10.2") (class "Default")
      (node (ref "R93") (pin "2") (pinfunction "2_2") (pintype "passive"))
      (node (ref "U4") (pin "7") (pinfunction "LED1_7") (pintype "output"))
    )
    (net (code "111") (name "/RGB10.3") (class "Default")
      (node (ref "R95") (pin "2") (pinfunction "2_2") (pintype "passive"))
      (node (ref "U4") (pin "6") (pinfunction "LED0_6") (pintype "output"))
    )
    (net (code "112") (name "/RXLED") (class "Default")
      (node (ref "IC5") (pin "22") (pinfunction "CBUS1_22") (pintype "bidirectional"))
      (node (ref "LED2") (pin "C") (pinfunction "C_C") (pintype "passive"))
    )
    (net (code "113") (name "/SCL") (class "Default")
      (node (ref "IC1") (pin "12") (pinfunction "SCL_12") (pintype "input"))
      (node (ref "IC4") (pin "28") (pinfunction "PC5(ADC5/SCL)_28") (pintype "bidirectional"))
      (node (ref "Q2") (pin "1") (pinfunction "D_1") (pintype "passive"))
      (node (ref "R36") (pin "1") (pinfunction "1_1") (pintype "passive"))
      (node (ref "U1") (pin "26") (pinfunction "SCL_26") (pintype "input"))
      (node (ref "U2") (pin "26") (pinfunction "SCL_26") (pintype "input"))
      (node (ref "U4") (pin "26") (pinfunction "SCL_26") (pintype "input"))
    )
    (net (code "114") (name "/SCL_PI") (class "Default")
      (node (ref "Q2") (pin "2") (pinfunction "S_2") (pintype "passive"))
      (node (ref "R38") (pin "1") (pinfunction "1_1") (pintype "passive"))
      (node (ref "X1") (pin "5") (pinfunction "KL_5") (pintype "passive"))
    )
    (net (code "115") (name "/SDA") (class "Default")
      (node (ref "IC1") (pin "13") (pinfunction "SDA_13") (pintype "bidirectional"))
      (node (ref "IC4") (pin "27") (pinfunction "PC4(ADC4/SDA)_27") (pintype "bidirectional"))
      (node (ref "Q1") (pin "1") (pinfunction "D_1") (pintype "passive"))
      (node (ref "R37") (pin "1") (pinfunction "1_1") (pintype "passive"))
      (node (ref "U1") (pin "27") (pinfunction "SDA_27") (pintype "bidirectional"))
      (node (ref "U2") (pin "27") (pinfunction "SDA_27") (pintype "bidirectional"))
      (node (ref "U4") (pin "27") (pinfunction "SDA_27") (pintype "bidirectional"))
    )
    (net (code "116") (name "/SDA_PI") (class "Default")
      (node (ref "Q1") (pin "2") (pinfunction "S_2") (pintype "passive"))
      (node (ref "R39") (pin "1") (pinfunction "1_1") (pintype "passive"))
      (node (ref "X1") (pin "3") (pinfunction "KL_3") (pintype "passive"))
    )
    (net (code "117") (name "/SHUNT_IN_1") (class "Default")
      (node (ref "IC6") (pin "1") (pinfunction "OUT_1") (pintype "output"))
      (node (ref "R152") (pin "2") (pinfunction "2_2") (pintype "passive"))
      (node (ref "U3") (pin "13") (pinfunction "0_13") (pintype "bidirectional"))
    )
    (net (code "118") (name "/SHUNT_IN_2") (class "Default")
      (node (ref "IC6") (pin "7") (pinfunction "OUT_7") (pintype "output"))
      (node (ref "R157") (pin "2") (pinfunction "2_2") (pintype "passive"))
      (node (ref "U3") (pin "14") (pinfunction "1_14") (pintype "bidirectional"))
    )
    (net (code "119") (name "/SHUNT_IN_3") (class "Default")
      (node (ref "IC6") (pin "8") (pinfunction "OUT_8") (pintype "output"))
      (node (ref "R161") (pin "2") (pinfunction "2_2") (pintype "passive"))
      (node (ref "U3") (pin "15") (pinfunction "2_15") (pintype "bidirectional"))
    )
    (net (code "120") (name "/SHUNT_IN_4") (class "Default")
      (node (ref "IC6") (pin "14") (pinfunction "OUT_14") (pintype "output"))
      (node (ref "R165") (pin "2") (pinfunction "2_2") (pintype "passive"))
      (node (ref "U3") (pin "12") (pinfunction "3_12") (pintype "bidirectional"))
    )
    (net (code "121") (name "/SHUNT_IN_5") (class "Default")
      (node (ref "IC8") (pin "1") (pinfunction "OUT_1") (pintype "output"))
      (node (ref "R170") (pin "2") (pinfunction "2_2") (pintype "passive"))
      (node (ref "U3") (pin "1") (pinfunction "4_1") (pintype "bidirectional"))
    )
    (net (code "122") (name "/SHUNT_IN_5_+") (class "Default")
      (node (ref "PAD12") (pin "1") (pinfunction "P_1") (pintype "passive"))
      (node (ref "R166") (pin "1") (pinfunction "1_1") (pintype "passive"))
    )
    (net (code "123") (name "/SHUNT_IN_5_-") (class "Default")
      (node (ref "PAD13") (pin "1") (pinfunction "P_1") (pintype "passive"))
      (node (ref "R168") (pin "1") (pinfunction "1_1") (pintype "passive"))
    )
    (net (code "124") (name "/SHUNT_IN_6") (class "Default")
      (node (ref "IC8") (pin "7") (pinfunction "OUT_7") (pintype "output"))
      (node (ref "R173") (pin "2") (pinfunction "2_2") (pintype "passive"))
      (node (ref "U3") (pin "5") (pinfunction "5_5") (pintype "bidirectional"))
    )
    (net (code "125") (name "/SHUNT_IN_7") (class "Default")
      (node (ref "IC8") (pin "8") (pinfunction "OUT_8") (pintype "output"))
      (node (ref "R177") (pin "2") (pinfunction "2_2") (pintype "passive"))
      (node (ref "U3") (pin "2") (pinfunction "6_2") (pintype "bidirectional"))
    )
    (net (code "126") (name "/SHUNT_IN_8") (class "Default")
      (node (ref "IC8") (pin "14") (pinfunction "OUT_14") (pintype "output"))
      (node (ref "R181") (pin "2") (pinfunction "2_2") (pintype "passive"))
      (node (ref "U3") (pin "4") (pinfunction "7_4") (pintype "bidirectional"))
    )
    (net (code "127") (name "/SPI_CE0") (class "Default")
      (node (ref "U7") (pin "10") (pinfunction "*CS/SHDN_10") (pintype "input"))
      (node (ref "X1") (pin "24") (pinfunction "KL_24") (pintype "passive"))
    )
    (net (code "128") (name "/SPI_CE1") (class "Default")
      (node (ref "X1") (pin "26") (pinfunction "KL_26") (pintype "passive"))
    )
    (net (code "129") (name "/SPI_MISO") (class "Default")
      (node (ref "U7") (pin "12") (pinfunction "DOUT_12") (pintype "output"))
      (node (ref "X1") (pin "21") (pinfunction "KL_21") (pintype "passive"))
    )
    (net (code "130") (name "/SPI_MOSI") (class "Default")
      (node (ref "U7") (pin "11") (pinfunction "DIN_11") (pintype "input"))
      (node (ref "X1") (pin "19") (pinfunction "KL_19") (pintype "passive"))
    )
    (net (code "131") (name "/SPI_SCLK") (class "Default")
      (node (ref "U7") (pin "13") (pinfunction "CLK_13") (pintype "input"))
      (node (ref "X1") (pin "23") (pinfunction "KL_23") (pintype "passive"))
    )
    (net (code "132") (name "/TEKRGB1.1") (class "Default")
      (node (ref "R145") (pin "2") (pinfunction "2_2") (pintype "passive"))
      (node (ref "U1") (pin "15") (pinfunction "LED8_15") (pintype "output"))
    )
    (net (code "133") (name "/TEKRGB1.2") (class "Default")
      (node (ref "R147") (pin "2") (pinfunction "2_2") (pintype "passive"))
      (node (ref "U1") (pin "16") (pinfunction "LED9_16") (pintype "output"))
    )
    (net (code "134") (name "/TEKRGB1.3") (class "Default")
      (node (ref "R149") (pin "2") (pinfunction "2_2") (pintype "passive"))
      (node (ref "U1") (pin "17") (pinfunction "LED10_17") (pintype "output"))
    )
    (net (code "135") (name "/TXLED") (class "Default")
      (node (ref "IC5") (pin "23") (pinfunction "CBUS0_23") (pintype "bidirectional"))
      (node (ref "LED1") (pin "C") (pinfunction "C_C") (pintype "passive"))
    )
    (net (code "136") (name "/UART_RXD") (class "Default")
      (node (ref "IC7") (pin "1") (pinfunction "RO_1") (pintype "output"))
      (node (ref "Q13") (pin "3") (pinfunction "G_3") (pintype "passive"))
      (node (ref "X1") (pin "10") (pinfunction "KL_10") (pintype "passive"))
    )
    (net (code "137") (name "/UART_TXD") (class "Default")
      (node (ref "IC7") (pin "4") (pinfunction "DI_4") (pintype "input"))
      (node (ref "Q14") (pin "3") (pinfunction "G_3") (pintype "passive"))
      (node (ref "R79") (pin "1") (pinfunction "1_1") (pintype "passive"))
      (node (ref "X1") (pin "8") (pinfunction "KL_8") (pintype "passive"))
    )
    (net (code "138") (name "GND") (class "Default")
      (node (ref "C1") (pin "2") (pinfunction "2_2") (pintype "passive"))
      (node (ref "C10") (pin "2") (pinfunction "2_2") (pintype "passive"))
      (node (ref "C11") (pin "2") (pinfunction "2_2") (pintype "passive"))
      (node (ref "C12") (pin "2") (pinfunction "2_2") (pintype "passive"))
      (node (ref "C13") (pin "2") (pinfunction "2_2") (pintype "passive"))
      (node (ref "C15") (pin "2") (pinfunction "2_2") (pintype "passive"))
      (node (ref "C16") (pin "2") (pinfunction "2_2") (pintype "passive"))
      (node (ref "C17") (pin "2") (pinfunction "2_2") (pintype "passive"))
      (node (ref "C18") (pin "2") (pinfunction "2_2") (pintype "passive"))
      (node (ref "C19") (pin "2") (pinfunction "2_2") (pintype "passive"))
      (node (ref "C2") (pin "2") (pinfunction "2_2") (pintype "passive"))
      (node (ref "C20") (pin "2") (pinfunction "2_2") (pintype "passive"))
      (node (ref "C21") (pin "2") (pinfunction "2_2") (pintype "passive"))
      (node (ref "C22") (pin "2") (pinfunction "2_2") (pintype "passive"))
      (node (ref "C23") (pin "2") (pinfunction "2_2") (pintype "passive"))
      (node (ref "C24") (pin "2") (pinfunction "2_2") (pintype "passive"))
      (node (ref "C25") (pin "2") (pinfunction "2_2") (pintype "passive"))
      (node (ref "C26") (pin "2") (pinfunction "2_2") (pintype "passive"))
      (node (ref "C27") (pin "2") (pinfunction "2_2") (pintype "passive"))
      (node (ref "C28") (pin "2") (pinfunction "2_2") (pintype "passive"))
      (node (ref "C29") (pin "2") (pinfunction "2_2") (pintype "passive"))
      (node (ref "C3") (pin "2") (pinfunction "2_2") (pintype "passive"))
      (node (ref "C30") (pin "2") (pinfunction "2_2") (pintype "passive"))
      (node (ref "C31") (pin "2") (pinfunction "2_2") (pintype "passive"))
      (node (ref "C4") (pin "2") (pinfunction "2_2") (pintype "passive"))
      (node (ref "C5") (pin "2") (pinfunction "2_2") (pintype "passive"))
      (node (ref "C6") (pin "2") (pinfunction "2_2") (pintype "passive"))
      (node (ref "C7") (pin "2") (pinfunction "2_2") (pintype "passive"))
      (node (ref "C8") (pin "2") (pinfunction "2_2") (pintype "passive"))
      (node (ref "C9") (pin "1") (pinfunction "1_1") (pintype "passive"))
      (node (ref "D1") (pin "A") (pinfunction "A_A") (pintype "passive"))
      (node (ref "D10") (pin "1") (pinfunction "A_1") (pintype "passive"))
      (node (ref "D11") (pin "1") (pinfunction "A_1") (pintype "passive"))
      (node (ref "D12") (pin "1") (pinfunction "A_1") (pintype "passive"))
      (node (ref "D14") (pin "1") (pinfunction "A_1") (pintype "passive"))
      (node (ref "D15") (pin "1") (pinfunction "A_1") (pintype "passive"))
      (node (ref "D16") (pin "A") (pinfunction "A_A") (pintype "passive"))
      (node (ref "D17") (pin "A") (pinfunction "A_A") (pintype "passive"))
      (node (ref "D2") (pin "A") (pinfunction "A_A") (pintype "passive"))
      (node (ref "D3") (pin "A") (pinfunction "A_A") (pintype "passive"))
      (node (ref "D4") (pin "A") (pinfunction "A_A") (pintype "passive"))
      (node (ref "D5") (pin "1") (pinfunction "A_1") (pintype "passive"))
      (node (ref "D6") (pin "1") (pinfunction "A_1") (pintype "passive"))
      (node (ref "D7") (pin "1") (pinfunction "A_1") (pintype "passive"))
      (node (ref "D8") (pin "1") (pinfunction "A_1") (pintype "passive"))
      (node (ref "D9") (pin "1") (pinfunction "A_1") (pintype "passive"))
      (node (ref "IC1") (pin "10") (pinfunction "VSS_10") (pintype "power_in"))
      (node (ref "IC2") (pin "7") (pinfunction "GND_7") (pintype "power_in"))
      (node (ref "IC3") (pin "7") (pinfunction "GND_7") (pintype "power_in"))
      (node (ref "IC4") (pin "20") (pinfunction "AREF_20") (pintype "passive"))
      (node (ref "IC4") (pin "21") (pinfunction "GND_21") (pintype "power_in"))
      (node (ref "IC4") (pin "3") (pinfunction "GND_3") (pintype "power_in"))
      (node (ref "IC4") (pin "5") (pinfunction "GND_5") (pintype "power_in"))
      (node (ref "IC5") (pin "11") (pinfunction "~{CTS}_11") (pintype "input"))
      (node (ref "IC5") (pin "18") (pinfunction "GND_18") (pintype "power_in"))
      (node (ref "IC5") (pin "21") (pinfunction "GND_21") (pintype "power_in"))
      (node (ref "IC5") (pin "25") (pinfunction "GND_25") (pintype "power_in"))
      (node (ref "IC5") (pin "26") (pinfunction "TEST_26") (pintype "input"))
      (node (ref "IC5") (pin "7") (pinfunction "GND_7") (pintype "power_in"))
      (node (ref "IC6") (pin "11") (pinfunction "V-_11") (pintype "power_in"))
      (node (ref "IC7") (pin "5") (pinfunction "GND_5") (pintype "power_in"))
      (node (ref "IC8") (pin "11") (pinfunction "V-_11") (pintype "power_in"))
      (node (ref "LED4") (pin "C") (pinfunction "C_C") (pintype "passive"))
      (node (ref "LED5") (pin "C") (pinfunction "C_C") (pintype "passive"))
      (node (ref "Q10") (pin "E") (pinfunction "E_E") (pintype "passive"))
      (node (ref "Q11") (pin "E") (pinfunction "E_E") (pintype "passive"))
      (node (ref "Q12") (pin "2") (pinfunction "S_2") (pintype "passive"))
      (node (ref "Q13") (pin "2") (pinfunction "S_2") (pintype "passive"))
      (node (ref "Q14") (pin "2") (pinfunction "S_2") (pintype "passive"))
      (node (ref "Q15") (pin "2") (pinfunction "S_2") (pintype "passive"))
      (node (ref "Q16") (pin "2") (pinfunction "S_2") (pintype "passive"))
      (node (ref "Q17") (pin "2") (pinfunction "S_2") (pintype "passive"))
      (node (ref "Q18") (pin "2") (pinfunction "S_2") (pintype "passive"))
      (node (ref "Q19") (pin "2") (pinfunction "S_2") (pintype "passive"))
      (node (ref "Q20") (pin "2") (pinfunction "S_2") (pintype "passive"))
      (node (ref "Q21") (pin "2") (pinfunction "S_2") (pintype "passive"))
      (node (ref "Q22") (pin "2") (pinfunction "S_2") (pintype "passive"))
      (node (ref "Q23") (pin "2") (pinfunction "S_2") (pintype "passive"))
      (node (ref "Q24") (pin "2") (pinfunction "S_2") (pintype "passive"))
      (node (ref "Q25") (pin "2") (pinfunction "S_2") (pintype "passive"))
      (node (ref "Q26") (pin "2") (pinfunction "S_2") (pintype "passive"))
      (node (ref "Q27") (pin "2") (pinfunction "S_2") (pintype "passive"))
      (node (ref "Q28") (pin "2") (pinfunction "S_2") (pintype "passive"))
      (node (ref "Q29") (pin "2") (pinfunction "S_2") (pintype "passive"))
      (node (ref "Q3") (pin "E") (pinfunction "E_E") (pintype "passive"))
      (node (ref "Q30") (pin "2") (pinfunction "S_2") (pintype "passive"))
      (node (ref "Q31") (pin "2") (pinfunction "S_2") (pintype "passive"))
      (node (ref "Q32") (pin "2") (pinfunction "S_2") (pintype "passive"))
      (node (ref "Q33") (pin "2") (pinfunction "S_2") (pintype "passive"))
      (node (ref "Q34") (pin "2") (pinfunction "S_2") (pintype "passive"))
      (node (ref "Q35") (pin "2") (pinfunction "S_2") (pintype "passive"))
      (node (ref "Q36") (pin "2") (pinfunction "S_2") (pintype "passive"))
      (node (ref "Q37") (pin "2") (pinfunction "S_2") (pintype "passive"))
      (node (ref "Q38") (pin "2") (pinfunction "S_2") (pintype "passive"))
      (node (ref "Q39") (pin "2") (pinfunction "S_2") (pintype "passive"))
      (node (ref "Q4") (pin "2") (pinfunction "2_2") (pintype "passive"))
      (node (ref "Q40") (pin "2") (pinfunction "S_2") (pintype "passive"))
      (node (ref "Q41") (pin "2") (pinfunction "S_2") (pintype "passive"))
      (node (ref "Q42") (pin "2") (pinfunction "S_2") (pintype "passive"))
      (node (ref "Q43") (pin "2") (pinfunction "S_2") (pintype "passive"))
      (node (ref "Q44") (pin "2") (pinfunction "S_2") (pintype "passive"))
      (node (ref "Q45") (pin "2") (pinfunction "S_2") (pintype "passive"))
      (node (ref "Q46") (pin "2") (pinfunction "S_2") (pintype "passive"))
      (node (ref "Q47") (pin "2") (pinfunction "S_2") (pintype "passive"))
      (node (ref "Q5") (pin "E") (pinfunction "E_E") (pintype "passive"))
      (node (ref "Q6") (pin "E") (pinfunction "E_E") (pintype "passive"))
      (node (ref "Q7") (pin "E") (pinfunction "E_E") (pintype "passive"))
      (node (ref "Q8") (pin "E") (pinfunction "E_E") (pintype "passive"))
      (node (ref "Q9") (pin "E") (pinfunction "E_E") (pintype "passive"))
      (node (ref "R100") (pin "2") (pinfunction "2_2") (pintype "passive"))
      (node (ref "R102") (pin "2") (pinfunction "2_2") (pintype "passive"))
      (node (ref "R104") (pin "2") (pinfunction "2_2") (pintype "passive"))
      (node (ref "R106") (pin "2") (pinfunction "2_2") (pintype "passive"))
      (node (ref "R108") (pin "2") (pinfunction "2_2") (pintype "passive"))
      (node (ref "R110") (pin "2") (pinfunction "2_2") (pintype "passive"))
      (node (ref "R112") (pin "2") (pinfunction "2_2") (pintype "passive"))
      (node (ref "R114") (pin "2") (pinfunction "2_2") (pintype "passive"))
      (node (ref "R116") (pin "2") (pinfunction "2_2") (pintype "passive"))
      (node (ref "R118") (pin "2") (pinfunction "2_2") (pintype "passive"))
      (node (ref "R120") (pin "2") (pinfunction "2_2") (pintype "passive"))
      (node (ref "R122") (pin "2") (pinfunction "2_2") (pintype "passive"))
      (node (ref "R124") (pin "2") (pinfunction "2_2") (pintype "passive"))
      (node (ref "R126") (pin "2") (pinfunction "2_2") (pintype "passive"))
      (node (ref "R128") (pin "2") (pinfunction "2_2") (pintype "passive"))
      (node (ref "R130") (pin "2") (pinfunction "2_2") (pintype "passive"))
      (node (ref "R132") (pin "2") (pinfunction "2_2") (pintype "passive"))
      (node (ref "R134") (pin "2") (pinfunction "2_2") (pintype "passive"))
      (node (ref "R136") (pin "2") (pinfunction "2_2") (pintype "passive"))
      (node (ref "R138") (pin "2") (pinfunction "2_2") (pintype "passive"))
      (node (ref "R140") (pin "2") (pinfunction "2_2") (pintype "passive"))
      (node (ref "R142") (pin "2") (pinfunction "2_2") (pintype "passive"))
      (node (ref "R144") (pin "2") (pinfunction "2_2") (pintype "passive"))
      (node (ref "R146") (pin "2") (pinfunction "2_2") (pintype "passive"))
      (node (ref "R148") (pin "2") (pinfunction "2_2") (pintype "passive"))
      (node (ref "R150") (pin "2") (pinfunction "2_2") (pintype "passive"))
      (node (ref "R28") (pin "1") (pinfunction "1_1") (pintype "passive"))
      (node (ref "R29") (pin "1") (pinfunction "1_1") (pintype "passive"))
      (node (ref "R30") (pin "1") (pinfunction "1_1") (pintype "passive"))
      (node (ref "R31") (pin "1") (pinfunction "1_1") (pintype "passive"))
      (node (ref "R48") (pin "2") (pinfunction "2_2") (pintype "passive"))
      (node (ref "R54") (pin "2") (pinfunction "2_2") (pintype "passive"))
      (node (ref "R57") (pin "2") (pinfunction "2_2") (pintype "passive"))
      (node (ref "R60") (pin "2") (pinfunction "2_2") (pintype "passive"))
      (node (ref "R63") (pin "2") (pinfunction "2_2") (pintype "passive"))
      (node (ref "R66") (pin "2") (pinfunction "2_2") (pintype "passive"))
      (node (ref "R69") (pin "2") (pinfunction "2_2") (pintype "passive"))
      (node (ref "R72") (pin "2") (pinfunction "2_2") (pintype "passive"))
      (node (ref "R75") (pin "2") (pinfunction "2_2") (pintype "passive"))
      (node (ref "R84") (pin "1") (pinfunction "1_1") (pintype "passive"))
      (node (ref "R86") (pin "2") (pinfunction "2_2") (pintype "passive"))
      (node (ref "R88") (pin "2") (pinfunction "2_2") (pintype "passive"))
      (node (ref "R90") (pin "2") (pinfunction "2_2") (pintype "passive"))
      (node (ref "R92") (pin "2") (pinfunction "2_2") (pintype "passive"))
      (node (ref "R94") (pin "2") (pinfunction "2_2") (pintype "passive"))
      (node (ref "R96") (pin "2") (pinfunction "2_2") (pintype "passive"))
      (node (ref "R98") (pin "2") (pinfunction "2_2") (pintype "passive"))
      (node (ref "S1") (pin "1") (pinfunction "1.1_1") (pintype "passive"))
      (node (ref "S1") (pin "2") (pinfunction "1.2_2") (pintype "passive"))
      (node (ref "SJ1") (pin "1") (pinfunction "1_1") (pintype "passive"))
      (node (ref "SJ10") (pin "1") (pinfunction "1_1") (pintype "passive"))
      (node (ref "SJ11") (pin "1") (pinfunction "1_1") (pintype "passive"))
      (node (ref "SJ12") (pin "3") (pinfunction "3_3") (pintype "passive"))
      (node (ref "SJ13") (pin "1") (pinfunction "1_1") (pintype "passive"))
      (node (ref "SJ14") (pin "1") (pinfunction "1_1") (pintype "passive"))
      (node (ref "SJ15") (pin "1") (pinfunction "1_1") (pintype "passive"))
      (node (ref "SJ16") (pin "1") (pinfunction "1_1") (pintype "passive"))
      (node (ref "SJ2") (pin "1") (pinfunction "1_1") (pintype "passive"))
      (node (ref "SJ3") (pin "1") (pinfunction "1_1") (pintype "passive"))
      (node (ref "SJ4") (pin "3") (pinfunction "3_3") (pintype "passive"))
      (node (ref "SJ5") (pin "1") (pinfunction "1_1") (pintype "passive"))
      (node (ref "SJ6") (pin "1") (pinfunction "1_1") (pintype "passive"))
      (node (ref "SJ7") (pin "1") (pinfunction "1_1") (pintype "passive"))
      (node (ref "SJ8") (pin "3") (pinfunction "3_3") (pintype "passive"))
      (node (ref "SJ9") (pin "1") (pinfunction "1_1") (pintype "passive"))
      (node (ref "U1") (pin "14") (pinfunction "VSS_14") (pintype "passive"))
      (node (ref "U2") (pin "14") (pinfunction "VSS_14") (pintype "passive"))
      (node (ref "U3") (pin "7") (pinfunction "VSS_7") (pintype "power_in"))
      (node (ref "U3") (pin "8") (pinfunction "VEE_8") (pintype "power_in"))
      (node (ref "U4") (pin "14") (pinfunction "VSS_14") (pintype "passive"))
      (node (ref "U5") (pin "9") (pinfunction "GND_9") (pintype "passive"))
      (node (ref "U6") (pin "5") (pinfunction "5B_5") (pintype "input"))
      (node (ref "U6") (pin "6") (pinfunction "6B_6") (pintype "input"))
      (node (ref "U6") (pin "7") (pinfunction "7B_7") (pintype "input"))
      (node (ref "U6") (pin "8") (pinfunction "8B_8") (pintype "input"))
      (node (ref "U6") (pin "9") (pinfunction "GND_9") (pintype "passive"))
      (node (ref "U7") (pin "14") (pinfunction "AGND_14") (pintype "passive"))
      (node (ref "U7") (pin "9") (pinfunction "DGND_9") (pintype "passive"))
      (node (ref "X1") (pin "14") (pinfunction "KL_14") (pintype "passive"))
      (node (ref "X1") (pin "20") (pinfunction "KL_20") (pintype "passive"))
      (node (ref "X1") (pin "25") (pinfunction "KL_25") (pintype "passive"))
      (node (ref "X1") (pin "30") (pinfunction "KL_30") (pintype "passive"))
      (node (ref "X1") (pin "34") (pinfunction "KL_34") (pintype "passive"))
      (node (ref "X1") (pin "39") (pinfunction "KL_39") (pintype "passive"))
      (node (ref "X1") (pin "6") (pinfunction "KL_6") (pintype "passive"))
      (node (ref "X1") (pin "9") (pinfunction "KL_9") (pintype "passive"))
      (node (ref "X3") (pin "5") (pinfunction "5_5") (pintype "passive"))
      (node (ref "X3") (pin "M1") (pinfunction "S1_M1") (pintype "passive"))
      (node (ref "X3") (pin "M2") (pinfunction "S2_M2") (pintype "passive"))
      (node (ref "X3") (pin "M3") (pinfunction "S3_M3") (pintype "passive"))
      (node (ref "X3") (pin "M4") (pinfunction "S4_M4") (pintype "passive"))
    )
    (net (code "139") (name "Net-(IC1-A0)") (class "Default")
      (node (ref "IC1") (pin "15") (pinfunction "A0_15") (pintype "input"))
      (node (ref "R25") (pin "2") (pinfunction "2_2") (pintype "passive"))
      (node (ref "SJ15") (pin "2") (pinfunction "2_2") (pintype "passive"))
    )
    (net (code "140") (name "Net-(IC1-A1)") (class "Default")
      (node (ref "IC1") (pin "16") (pinfunction "A1_16") (pintype "input"))
      (node (ref "R26") (pin "2") (pinfunction "2_2") (pintype "passive"))
      (node (ref "SJ13") (pin "2") (pinfunction "2_2") (pintype "passive"))
    )
    (net (code "141") (name "Net-(IC1-A2)") (class "Default")
      (node (ref "IC1") (pin "17") (pinfunction "A2_17") (pintype "input"))
      (node (ref "R27") (pin "2") (pinfunction "2_2") (pintype "passive"))
      (node (ref "SJ14") (pin "2") (pinfunction "2_2") (pintype "passive"))
    )
    (net (code "142") (name "Net-(IC1-GPA0)") (class "Default")
      (node (ref "IC1") (pin "21") (pinfunction "GPA0_21") (pintype "bidirectional"))
      (node (ref "U5") (pin "1") (pinfunction "1B_1") (pintype "input"))
    )
    (net (code "143") (name "Net-(IC1-GPA1)") (class "Default")
      (node (ref "IC1") (pin "22") (pinfunction "GPA1_22") (pintype "bidirectional"))
      (node (ref "U5") (pin "2") (pinfunction "2B_2") (pintype "input"))
    )
    (net (code "144") (name "Net-(IC1-GPA2)") (class "Default")
      (node (ref "IC1") (pin "23") (pinfunction "GPA2_23") (pintype "bidirectional"))
      (node (ref "U5") (pin "3") (pinfunction "3B_3") (pintype "input"))
    )
    (net (code "145") (name "Net-(IC1-GPA3)") (class "Default")
      (node (ref "IC1") (pin "24") (pinfunction "GPA3_24") (pintype "bidirectional"))
      (node (ref "U5") (pin "4") (pinfunction "4B_4") (pintype "input"))
    )
    (net (code "146") (name "Net-(IC1-GPA4)") (class "Default")
      (node (ref "IC1") (pin "25") (pinfunction "GPA4_25") (pintype "bidirectional"))
      (node (ref "U5") (pin "5") (pinfunction "5B_5") (pintype "input"))
    )
    (net (code "147") (name "Net-(IC1-GPA5)") (class "Default")
      (node (ref "IC1") (pin "26") (pinfunction "GPA5_26") (pintype "bidirectional"))
      (node (ref "U5") (pin "6") (pinfunction "6B_6") (pintype "input"))
    )
    (net (code "148") (name "Net-(IC1-GPA6)") (class "Default")
      (node (ref "IC1") (pin "27") (pinfunction "GPA6_27") (pintype "bidirectional"))
      (node (ref "U5") (pin "7") (pinfunction "7B_7") (pintype "input"))
    )
    (net (code "149") (name "Net-(IC1-GPA7)") (class "Default")
      (node (ref "IC1") (pin "28") (pinfunction "GPA7_28") (pintype "bidirectional"))
      (node (ref "U5") (pin "8") (pinfunction "8B_8") (pintype "input"))
    )
    (net (code "150") (name "Net-(IC1-GPB0)") (class "Default")
      (node (ref "IC1") (pin "1") (pinfunction "GPB0_1") (pintype "bidirectional"))
      (node (ref "U6") (pin "1") (pinfunction "1B_1") (pintype "input"))
    )
    (net (code "151") (name "Net-(IC1-GPB1)") (class "Default")
      (node (ref "IC1") (pin "2") (pinfunction "GPB1_2") (pintype "bidirectional"))
      (node (ref "U6") (pin "2") (pinfunction "2B_2") (pintype "input"))
    )
    (net (code "152") (name "Net-(IC1-GPB2)") (class "Default")
      (node (ref "IC1") (pin "3") (pinfunction "GPB2_3") (pintype "bidirectional"))
      (node (ref "U6") (pin "3") (pinfunction "3B_3") (pintype "input"))
    )
    (net (code "153") (name "Net-(IC1-GPB3)") (class "Default")
      (node (ref "IC1") (pin "4") (pinfunction "GPB3_4") (pintype "bidirectional"))
      (node (ref "U6") (pin "4") (pinfunction "4B_4") (pintype "input"))
    )
    (net (code "154") (name "Net-(IC1-GPB4)") (class "Default")
      (node (ref "D4") (pin "C") (pinfunction "C_C") (pintype "passive"))
      (node (ref "IC1") (pin "5") (pinfunction "GPB4_5") (pintype "bidirectional"))
      (node (ref "R31") (pin "2") (pinfunction "2_2") (pintype "passive"))
      (node (ref "R35") (pin "1") (pinfunction "1_1") (pintype "passive"))
    )
    (net (code "155") (name "Net-(IC1-GPB5)") (class "Default")
      (node (ref "D3") (pin "C") (pinfunction "C_C") (pintype "passive"))
      (node (ref "IC1") (pin "6") (pinfunction "GPB5_6") (pintype "bidirectional"))
      (node (ref "R30") (pin "2") (pinfunction "2_2") (pintype "passive"))
      (node (ref "R34") (pin "1") (pinfunction "1_1") (pintype "passive"))
    )
    (net (code "156") (name "Net-(IC1-GPB6)") (class "Default")
      (node (ref "D2") (pin "C") (pinfunction "C_C") (pintype "passive"))
      (node (ref "IC1") (pin "7") (pinfunction "GPB6_7") (pintype "bidirectional"))
      (node (ref "R29") (pin "2") (pinfunction "2_2") (pintype "passive"))
      (node (ref "R33") (pin "1") (pinfunction "1_1") (pintype "passive"))
    )
    (net (code "157") (name "Net-(IC1-GPB7)") (class "Default")
      (node (ref "D1") (pin "C") (pinfunction "C_C") (pintype "passive"))
      (node (ref "IC1") (pin "8") (pinfunction "GPB7_8") (pintype "bidirectional"))
      (node (ref "R28") (pin "2") (pinfunction "2_2") (pintype "passive"))
      (node (ref "R32") (pin "1") (pinfunction "1_1") (pintype "passive"))
    )
    (net (code "158") (name "Net-(IC2A-O)") (class "Default")
      (node (ref "IC2") (pin "3") (pinfunction "O_3") (pintype "output"))
      (node (ref "Q3") (pin "B") (pinfunction "B_B") (pintype "passive"))
      (node (ref "R48") (pin "1") (pinfunction "1_1") (pintype "passive"))
    )
    (net (code "159") (name "Net-(IC2B-O)") (class "Default")
      (node (ref "IC2") (pin "6") (pinfunction "O_6") (pintype "output"))
      (node (ref "Q5") (pin "B") (pinfunction "B_B") (pintype "passive"))
      (node (ref "R57") (pin "1") (pinfunction "1_1") (pintype "passive"))
    )
    (net (code "160") (name "Net-(IC2C-O)") (class "Default")
      (node (ref "IC2") (pin "8") (pinfunction "O_8") (pintype "output"))
      (node (ref "Q6") (pin "B") (pinfunction "B_B") (pintype "passive"))
      (node (ref "R60") (pin "1") (pinfunction "1_1") (pintype "passive"))
    )
    (net (code "161") (name "Net-(IC2D-O)") (class "Default")
      (node (ref "IC2") (pin "11") (pinfunction "O_11") (pintype "output"))
      (node (ref "Q7") (pin "B") (pinfunction "B_B") (pintype "passive"))
      (node (ref "R63") (pin "1") (pinfunction "1_1") (pintype "passive"))
    )
    (net (code "162") (name "Net-(IC3A-O)") (class "Default")
      (node (ref "IC3") (pin "3") (pinfunction "O_3") (pintype "output"))
      (node (ref "Q8") (pin "B") (pinfunction "B_B") (pintype "passive"))
      (node (ref "R66") (pin "1") (pinfunction "1_1") (pintype "passive"))
    )
    (net (code "163") (name "Net-(IC3B-O)") (class "Default")
      (node (ref "IC3") (pin "6") (pinfunction "O_6") (pintype "output"))
      (node (ref "Q9") (pin "B") (pinfunction "B_B") (pintype "passive"))
      (node (ref "R69") (pin "1") (pinfunction "1_1") (pintype "passive"))
    )
    (net (code "164") (name "Net-(IC3C-O)") (class "Default")
      (node (ref "IC3") (pin "8") (pinfunction "O_8") (pintype "output"))
      (node (ref "Q10") (pin "B") (pinfunction "B_B") (pintype "passive"))
      (node (ref "R72") (pin "1") (pinfunction "1_1") (pintype "passive"))
    )
    (net (code "165") (name "Net-(IC3D-O)") (class "Default")
      (node (ref "IC3") (pin "11") (pinfunction "O_11") (pintype "output"))
      (node (ref "Q11") (pin "B") (pinfunction "B_B") (pintype "passive"))
      (node (ref "R75") (pin "1") (pinfunction "1_1") (pintype "passive"))
    )
    (net (code "166") (name "Net-(IC4-PB6(XTAL1{slash}TOSC1))") (class "Default")
      (node (ref "IC4") (pin "7") (pinfunction "PB6(XTAL1/TOSC1)_7") (pintype "bidirectional"))
      (node (ref "Q4") (pin "1") (pinfunction "1_1") (pintype "passive"))
    )
    (net (code "167") (name "Net-(IC4-PB7(XTAL2{slash}TOSC2))") (class "Default")
      (node (ref "IC4") (pin "8") (pinfunction "PB7(XTAL2/TOSC2)_8") (pintype "bidirectional"))
      (node (ref "Q4") (pin "3") (pinfunction "3_3") (pintype "passive"))
    )
    (net (code "168") (name "Net-(IC5-3V3OUT)") (class "Default")
      (node (ref "C13") (pin "1") (pinfunction "1_1") (pintype "passive"))
      (node (ref "IC5") (pin "17") (pinfunction "3V3OUT_17") (pintype "output"))
    )
    (net (code "169") (name "Net-(IC5-~{DTR})") (class "Default")
      (node (ref "C14") (pin "1") (pinfunction "1_1") (pintype "passive"))
      (node (ref "IC5") (pin "2") (pinfunction "~{DTR}_2") (pintype "output"))
    )
    (net (code "170") (name "Net-(IC6A-+IN)") (class "Default")
      (node (ref "IC6") (pin "3") (pinfunction "+IN_3") (pintype "input"))
      (node (ref "R151") (pin "1") (pinfunction "1_1") (pintype "passive"))
      (node (ref "R53") (pin "2") (pinfunction "2_2") (pintype "passive"))
    )
    (net (code "171") (name "Net-(IC6A--IN)") (class "Default")
      (node (ref "IC6") (pin "2") (pinfunction "-IN_2") (pintype "input"))
      (node (ref "R152") (pin "1") (pinfunction "1_1") (pintype "passive"))
      (node (ref "R153") (pin "2") (pinfunction "2_2") (pintype "passive"))
    )
    (net (code "172") (name "Net-(IC6B-+IN)") (class "Default")
      (node (ref "IC6") (pin "5") (pinfunction "+IN_5") (pintype "input"))
      (node (ref "R154") (pin "2") (pinfunction "2_2") (pintype "passive"))
      (node (ref "R155") (pin "1") (pinfunction "1_1") (pintype "passive"))
    )
    (net (code "173") (name "Net-(IC6B--IN)") (class "Default")
      (node (ref "IC6") (pin "6") (pinfunction "-IN_6") (pintype "input"))
      (node (ref "R156") (pin "2") (pinfunction "2_2") (pintype "passive"))
      (node (ref "R157") (pin "1") (pinfunction "1_1") (pintype "passive"))
    )
    (net (code "174") (name "Net-(IC6C-+IN)") (class "Default")
      (node (ref "IC6") (pin "10") (pinfunction "+IN_10") (pintype "input"))
      (node (ref "R158") (pin "2") (pinfunction "2_2") (pintype "passive"))
      (node (ref "R159") (pin "1") (pinfunction "1_1") (pintype "passive"))
    )
    (net (code "175") (name "Net-(IC6C--IN)") (class "Default")
      (node (ref "IC6") (pin "9") (pinfunction "-IN_9") (pintype "input"))
      (node (ref "R160") (pin "2") (pinfunction "2_2") (pintype "passive"))
      (node (ref "R161") (pin "1") (pinfunction "1_1") (pintype "passive"))
    )
    (net (code "176") (name "Net-(IC6D-+IN)") (class "Default")
      (node (ref "IC6") (pin "12") (pinfunction "+IN_12") (pintype "input"))
      (node (ref "R162") (pin "2") (pinfunction "2_2") (pintype "passive"))
      (node (ref "R163") (pin "1") (pinfunction "1_1") (pintype "passive"))
    )
    (net (code "177") (name "Net-(IC6D--IN)") (class "Default")
      (node (ref "IC6") (pin "13") (pinfunction "-IN_13") (pintype "input"))
      (node (ref "R164") (pin "2") (pinfunction "2_2") (pintype "passive"))
      (node (ref "R165") (pin "1") (pinfunction "1_1") (pintype "passive"))
    )
    (net (code "178") (name "Net-(IC7A-DE)") (class "Default")
      (node (ref "IC7") (pin "2") (pinfunction "RE/_2") (pintype "input"))
      (node (ref "IC7") (pin "3") (pinfunction "DE_3") (pintype "input"))
      (node (ref "Q12") (pin "1") (pinfunction "D_1") (pintype "passive"))
      (node (ref "R80") (pin "1") (pinfunction "1_1") (pintype "passive"))
    )
    (net (code "179") (name "Net-(IC8A-+IN)") (class "Default")
      (node (ref "IC8") (pin "3") (pinfunction "+IN_3") (pintype "input"))
      (node (ref "R166") (pin "2") (pinfunction "2_2") (pintype "passive"))
      (node (ref "R167") (pin "1") (pinfunction "1_1") (pintype "passive"))
    )
    (net (code "180") (name "Net-(IC8A--IN)") (class "Default")
      (node (ref "IC8") (pin "2") (pinfunction "-IN_2") (pintype "input"))
      (node (ref "R168") (pin "2") (pinfunction "2_2") (pintype "passive"))
      (node (ref "R170") (pin "1") (pinfunction "1_1") (pintype "passive"))
    )
    (net (code "181") (name "Net-(IC8B-+IN)") (class "Default")
      (node (ref "IC8") (pin "5") (pinfunction "+IN_5") (pintype "input"))
      (node (ref "R169") (pin "2") (pinfunction "2_2") (pintype "passive"))
      (node (ref "R171") (pin "1") (pinfunction "1_1") (pintype "passive"))
    )
    (net (code "182") (name "Net-(IC8B--IN)") (class "Default")
      (node (ref "IC8") (pin "6") (pinfunction "-IN_6") (pintype "input"))
      (node (ref "R172") (pin "2") (pinfunction "2_2") (pintype "passive"))
      (node (ref "R173") (pin "1") (pinfunction "1_1") (pintype "passive"))
    )
    (net (code "183") (name "Net-(IC8C-+IN)") (class "Default")
      (node (ref "IC8") (pin "10") (pinfunction "+IN_10") (pintype "input"))
      (node (ref "R174") (pin "2") (pinfunction "2_2") (pintype "passive"))
      (node (ref "R175") (pin "1") (pinfunction "1_1") (pintype "passive"))
    )
    (net (code "184") (name "Net-(IC8C--IN)") (class "Default")
      (node (ref "IC8") (pin "9") (pinfunction "-IN_9") (pintype "input"))
      (node (ref "R176") (pin "2") (pinfunction "2_2") (pintype "passive"))
      (node (ref "R177") (pin "1") (pinfunction "1_1") (pintype "passive"))
    )
    (net (code "185") (name "Net-(IC8D-+IN)") (class "Default")
      (node (ref "IC8") (pin "12") (pinfunction "+IN_12") (pintype "input"))
      (node (ref "R178") (pin "2") (pinfunction "2_2") (pintype "passive"))
      (node (ref "R179") (pin "1") (pinfunction "1_1") (pintype "passive"))
    )
    (net (code "186") (name "Net-(IC8D--IN)") (class "Default")
      (node (ref "IC8") (pin "13") (pinfunction "-IN_13") (pintype "input"))
      (node (ref "R180") (pin "2") (pinfunction "2_2") (pintype "passive"))
      (node (ref "R181") (pin "1") (pinfunction "1_1") (pintype "passive"))
    )
    (net (code "187") (name "Net-(LED1-PadA)") (class "Default")
      (node (ref "LED1") (pin "A") (pinfunction "A_A") (pintype "passive"))
      (node (ref "R51") (pin "2") (pinfunction "2_2") (pintype "passive"))
    )
    (net (code "188") (name "Net-(LED2-PadA)") (class "Default")
      (node (ref "LED2") (pin "A") (pinfunction "A_A") (pintype "passive"))
      (node (ref "R52") (pin "2") (pinfunction "2_2") (pintype "passive"))
    )
    (net (code "189") (name "Net-(LED3-PadC)") (class "Default")
      (node (ref "LED3") (pin "C") (pinfunction "C_C") (pintype "passive"))
      (node (ref "R54") (pin "1") (pinfunction "1_1") (pintype "passive"))
    )
    (net (code "190") (name "Net-(PAD1-P)") (class "Default")
      (node (ref "PAD1") (pin "1") (pinfunction "P_1") (pintype "passive"))
      (node (ref "Q45") (pin "1") (pinfunction "D_1") (pintype "passive"))
    )
    (net (code "191") (name "Net-(PAD2-P)") (class "Default")
      (node (ref "PAD2") (pin "1") (pinfunction "P_1") (pintype "passive"))
      (node (ref "Q46") (pin "1") (pinfunction "D_1") (pintype "passive"))
    )
    (net (code "192") (name "Net-(PAD3-P)") (class "Default")
      (node (ref "PAD3") (pin "1") (pinfunction "P_1") (pintype "passive"))
      (node (ref "Q47") (pin "1") (pinfunction "D_1") (pintype "passive"))
    )
    (net (code "193") (name "Net-(PAD4-P)") (class "Default")
      (node (ref "PAD4") (pin "1") (pinfunction "P_1") (pintype "passive"))
      (node (ref "R53") (pin "1") (pinfunction "1_1") (pintype "passive"))
    )
    (net (code "194") (name "Net-(PAD5-P)") (class "Default")
      (node (ref "PAD5") (pin "1") (pinfunction "P_1") (pintype "passive"))
      (node (ref "R153") (pin "1") (pinfunction "1_1") (pintype "passive"))
    )
    (net (code "195") (name "Net-(PAD6-P)") (class "Default")
      (node (ref "PAD6") (pin "1") (pinfunction "P_1") (pintype "passive"))
      (node (ref "R154") (pin "1") (pinfunction "1_1") (pintype "passive"))
    )
    (net (code "196") (name "Net-(PAD7-P)") (class "Default")
      (node (ref "PAD7") (pin "1") (pinfunction "P_1") (pintype "passive"))
      (node (ref "R156") (pin "1") (pinfunction "1_1") (pintype "passive"))
    )
    (net (code "197") (name "Net-(PAD8-P)") (class "Default")
      (node (ref "PAD8") (pin "1") (pinfunction "P_1") (pintype "passive"))
      (node (ref "R158") (pin "1") (pinfunction "1_1") (pintype "passive"))
    )
    (net (code "198") (name "Net-(PAD9-P)") (class "Default")
      (node (ref "PAD9") (pin "1") (pinfunction "P_1") (pintype "passive"))
      (node (ref "R160") (pin "1") (pinfunction "1_1") (pintype "passive"))
    )
    (net (code "199") (name "Net-(PAD10-P)") (class "Default")
      (node (ref "PAD10") (pin "1") (pinfunction "P_1") (pintype "passive"))
      (node (ref "R162") (pin "1") (pinfunction "1_1") (pintype "passive"))
    )
    (net (code "200") (name "Net-(PAD11-P)") (class "Default")
      (node (ref "PAD11") (pin "1") (pinfunction "P_1") (pintype "passive"))
      (node (ref "R164") (pin "1") (pinfunction "1_1") (pintype "passive"))
    )
    (net (code "201") (name "Net-(PAD14-P)") (class "Default")
      (node (ref "PAD14") (pin "1") (pinfunction "P_1") (pintype "passive"))
      (node (ref "R169") (pin "1") (pinfunction "1_1") (pintype "passive"))
    )
    (net (code "202") (name "Net-(PAD15-P)") (class "Default")
      (node (ref "PAD15") (pin "1") (pinfunction "P_1") (pintype "passive"))
      (node (ref "R172") (pin "1") (pinfunction "1_1") (pintype "passive"))
    )
    (net (code "203") (name "Net-(PAD16-P)") (class "Default")
      (node (ref "PAD16") (pin "1") (pinfunction "P_1") (pintype "passive"))
      (node (ref "R174") (pin "1") (pinfunction "1_1") (pintype "passive"))
    )
    (net (code "204") (name "Net-(PAD17-P)") (class "Default")
      (node (ref "PAD17") (pin "1") (pinfunction "P_1") (pintype "passive"))
      (node (ref "R176") (pin "1") (pinfunction "1_1") (pintype "passive"))
    )
    (net (code "205") (name "Net-(PAD18-P)") (class "Default")
      (node (ref "PAD18") (pin "1") (pinfunction "P_1") (pintype "passive"))
      (node (ref "R178") (pin "1") (pinfunction "1_1") (pintype "passive"))
    )
    (net (code "206") (name "Net-(PAD19-P)") (class "Default")
      (node (ref "PAD19") (pin "1") (pinfunction "P_1") (pintype "passive"))
      (node (ref "R180") (pin "1") (pinfunction "1_1") (pintype "passive"))
    )
    (net (code "207") (name "Net-(PAD31-P)") (class "Default")
      (node (ref "PAD31") (pin "1") (pinfunction "P_1") (pintype "passive"))
      (node (ref "Q15") (pin "1") (pinfunction "D_1") (pintype "passive"))
    )
    (net (code "208") (name "Net-(PAD32-P)") (class "Default")
      (node (ref "PAD32") (pin "1") (pinfunction "P_1") (pintype "passive"))
      (node (ref "Q16") (pin "1") (pinfunction "D_1") (pintype "passive"))
    )
    (net (code "209") (name "Net-(PAD33-P)") (class "Default")
      (node (ref "PAD33") (pin "1") (pinfunction "P_1") (pintype "passive"))
      (node (ref "Q17") (pin "1") (pinfunction "D_1") (pintype "passive"))
    )
    (net (code "210") (name "Net-(PAD34-P)") (class "Default")
      (node (ref "PAD34") (pin "1") (pinfunction "P_1") (pintype "passive"))
      (node (ref "Q18") (pin "1") (pinfunction "D_1") (pintype "passive"))
    )
    (net (code "211") (name "Net-(PAD35-P)") (class "Default")
      (node (ref "PAD35") (pin "1") (pinfunction "P_1") (pintype "passive"))
      (node (ref "Q19") (pin "1") (pinfunction "D_1") (pintype "passive"))
    )
    (net (code "212") (name "Net-(PAD36-P)") (class "Default")
      (node (ref "PAD36") (pin "1") (pinfunction "P_1") (pintype "passive"))
      (node (ref "Q20") (pin "1") (pinfunction "D_1") (pintype "passive"))
    )
    (net (code "213") (name "Net-(PAD37-P)") (class "Default")
      (node (ref "PAD37") (pin "1") (pinfunction "P_1") (pintype "passive"))
      (node (ref "Q21") (pin "1") (pinfunction "D_1") (pintype "passive"))
    )
    (net (code "214") (name "Net-(PAD48-P)") (class "Default")
      (node (ref "PAD48") (pin "1") (pinfunction "P_1") (pintype "passive"))
      (node (ref "R50") (pin "1") (pinfunction "1_1") (pintype "passive"))
    )
    (net (code "215") (name "Net-(PAD49-P)") (class "Default")
      (node (ref "PAD49") (pin "1") (pinfunction "P_1") (pintype "passive"))
      (node (ref "R59") (pin "1") (pinfunction "1_1") (pintype "passive"))
    )
    (net (code "216") (name "Net-(PAD50-P)") (class "Default")
      (node (ref "PAD50") (pin "1") (pinfunction "P_1") (pintype "passive"))
      (node (ref "R62") (pin "1") (pinfunction "1_1") (pintype "passive"))
    )
    (net (code "217") (name "Net-(PAD51-P)") (class "Default")
      (node (ref "PAD51") (pin "1") (pinfunction "P_1") (pintype "passive"))
      (node (ref "R65") (pin "1") (pinfunction "1_1") (pintype "passive"))
    )
    (net (code "218") (name "Net-(PAD52-P)") (class "Default")
      (node (ref "PAD52") (pin "1") (pinfunction "P_1") (pintype "passive"))
      (node (ref "R68") (pin "1") (pinfunction "1_1") (pintype "passive"))
    )
    (net (code "219") (name "Net-(PAD53-P)") (class "Default")
      (node (ref "PAD53") (pin "1") (pinfunction "P_1") (pintype "passive"))
      (node (ref "R71") (pin "1") (pinfunction "1_1") (pintype "passive"))
    )
    (net (code "220") (name "Net-(PAD54-P)") (class "Default")
      (node (ref "PAD54") (pin "1") (pinfunction "P_1") (pintype "passive"))
      (node (ref "R74") (pin "1") (pinfunction "1_1") (pintype "passive"))
    )
    (net (code "221") (name "Net-(PAD55-P)") (class "Default")
      (node (ref "PAD55") (pin "1") (pinfunction "P_1") (pintype "passive"))
      (node (ref "R77") (pin "1") (pinfunction "1_1") (pintype "passive"))
    )
    (net (code "222") (name "Net-(PAD64-P)") (class "Default")
      (node (ref "PAD64") (pin "1") (pinfunction "P_1") (pintype "passive"))
      (node (ref "U5") (pin "18") (pinfunction "1C_18") (pintype "output"))
    )
    (net (code "223") (name "Net-(PAD65-P)") (class "Default")
      (node (ref "PAD65") (pin "1") (pinfunction "P_1") (pintype "passive"))
      (node (ref "U5") (pin "17") (pinfunction "2C_17") (pintype "output"))
    )
    (net (code "224") (name "Net-(PAD66-P)") (class "Default")
      (node (ref "PAD66") (pin "1") (pinfunction "P_1") (pintype "passive"))
      (node (ref "U5") (pin "16") (pinfunction "3C_16") (pintype "output"))
    )
    (net (code "225") (name "Net-(PAD67-P)") (class "Default")
      (node (ref "PAD67") (pin "1") (pinfunction "P_1") (pintype "passive"))
      (node (ref "U5") (pin "15") (pinfunction "4C_15") (pintype "output"))
    )
    (net (code "226") (name "Net-(PAD68-P)") (class "Default")
      (node (ref "PAD68") (pin "1") (pinfunction "P_1") (pintype "passive"))
      (node (ref "U5") (pin "14") (pinfunction "5C_14") (pintype "output"))
    )
    (net (code "227") (name "Net-(PAD69-P)") (class "Default")
      (node (ref "PAD69") (pin "1") (pinfunction "P_1") (pintype "passive"))
      (node (ref "U5") (pin "13") (pinfunction "6C_13") (pintype "output"))
    )
    (net (code "228") (name "Net-(PAD70-P)") (class "Default")
      (node (ref "PAD70") (pin "1") (pinfunction "P_1") (pintype "passive"))
      (node (ref "U5") (pin "12") (pinfunction "7C_12") (pintype "output"))
    )
    (net (code "229") (name "Net-(PAD71-P)") (class "Default")
      (node (ref "PAD71") (pin "1") (pinfunction "P_1") (pintype "passive"))
      (node (ref "U5") (pin "11") (pinfunction "8C_11") (pintype "output"))
    )
    (net (code "230") (name "Net-(PAD72-P)") (class "Default")
      (node (ref "PAD72") (pin "1") (pinfunction "P_1") (pintype "passive"))
      (node (ref "U6") (pin "18") (pinfunction "1C_18") (pintype "output"))
    )
    (net (code "231") (name "Net-(PAD73-P)") (class "Default")
      (node (ref "PAD73") (pin "1") (pinfunction "P_1") (pintype "passive"))
      (node (ref "U6") (pin "17") (pinfunction "2C_17") (pintype "output"))
    )
    (net (code "232") (name "Net-(PAD74-P)") (class "Default")
      (node (ref "PAD74") (pin "1") (pinfunction "P_1") (pintype "passive"))
      (node (ref "U6") (pin "16") (pinfunction "3C_16") (pintype "output"))
    )
    (net (code "233") (name "Net-(PAD75-P)") (class "Default")
      (node (ref "PAD75") (pin "1") (pinfunction "P_1") (pintype "passive"))
      (node (ref "U6") (pin "15") (pinfunction "4C_15") (pintype "output"))
    )
    (net (code "234") (name "Net-(PAD80-P)") (class "Default")
      (node (ref "PAD80") (pin "1") (pinfunction "P_1") (pintype "passive"))
      (node (ref "Q22") (pin "1") (pinfunction "D_1") (pintype "passive"))
    )
    (net (code "235") (name "Net-(PAD81-P)") (class "Default")
      (node (ref "PAD81") (pin "1") (pinfunction "P_1") (pintype "passive"))
      (node (ref "Q23") (pin "1") (pinfunction "D_1") (pintype "passive"))
    )
    (net (code "236") (name "Net-(PAD82-P)") (class "Default")
      (node (ref "PAD82") (pin "1") (pinfunction "P_1") (pintype "passive"))
      (node (ref "Q24") (pin "1") (pinfunction "D_1") (pintype "passive"))
    )
    (net (code "237") (name "Net-(PAD83-P)") (class "Default")
      (node (ref "PAD83") (pin "1") (pinfunction "P_1") (pintype "passive"))
      (node (ref "Q25") (pin "1") (pinfunction "D_1") (pintype "passive"))
    )
    (net (code "238") (name "Net-(PAD84-P)") (class "Default")
      (node (ref "PAD84") (pin "1") (pinfunction "P_1") (pintype "passive"))
      (node (ref "Q26") (pin "1") (pinfunction "D_1") (pintype "passive"))
    )
    (net (code "239") (name "Net-(PAD85-P)") (class "Default")
      (node (ref "PAD85") (pin "1") (pinfunction "P_1") (pintype "passive"))
      (node (ref "Q27") (pin "1") (pinfunction "D_1") (pintype "passive"))
    )
    (net (code "240") (name "Net-(PAD86-P)") (class "Default")
      (node (ref "PAD86") (pin "1") (pinfunction "P_1") (pintype "passive"))
      (node (ref "Q28") (pin "1") (pinfunction "D_1") (pintype "passive"))
    )
    (net (code "241") (name "Net-(PAD87-P)") (class "Default")
      (node (ref "PAD87") (pin "1") (pinfunction "P_1") (pintype "passive"))
      (node (ref "Q29") (pin "1") (pinfunction "D_1") (pintype "passive"))
    )
    (net (code "242") (name "Net-(PAD88-P)") (class "Default")
      (node (ref "PAD88") (pin "1") (pinfunction "P_1") (pintype "passive"))
      (node (ref "Q30") (pin "1") (pinfunction "D_1") (pintype "passive"))
    )
    (net (code "243") (name "Net-(PAD89-P)") (class "Default")
      (node (ref "PAD89") (pin "1") (pinfunction "P_1") (pintype "passive"))
      (node (ref "Q31") (pin "1") (pinfunction "D_1") (pintype "passive"))
    )
    (net (code "244") (name "Net-(PAD90-P)") (class "Default")
      (node (ref "PAD90") (pin "1") (pinfunction "P_1") (pintype "passive"))
      (node (ref "Q32") (pin "1") (pinfunction "D_1") (pintype "passive"))
    )
    (net (code "245") (name "Net-(PAD91-P)") (class "Default")
      (node (ref "PAD91") (pin "1") (pinfunction "P_1") (pintype "passive"))
      (node (ref "Q33") (pin "1") (pinfunction "D_1") (pintype "passive"))
    )
    (net (code "246") (name "Net-(PAD92-P)") (class "Default")
      (node (ref "PAD92") (pin "1") (pinfunction "P_1") (pintype "passive"))
      (node (ref "Q34") (pin "1") (pinfunction "D_1") (pintype "passive"))
    )
    (net (code "247") (name "Net-(PAD93-P)") (class "Default")
      (node (ref "PAD93") (pin "1") (pinfunction "P_1") (pintype "passive"))
      (node (ref "Q35") (pin "1") (pinfunction "D_1") (pintype "passive"))
    )
    (net (code "248") (name "Net-(PAD94-P)") (class "Default")
      (node (ref "PAD94") (pin "1") (pinfunction "P_1") (pintype "passive"))
      (node (ref "Q36") (pin "1") (pinfunction "D_1") (pintype "passive"))
    )
    (net (code "249") (name "Net-(PAD95-P)") (class "Default")
      (node (ref "PAD95") (pin "1") (pinfunction "P_1") (pintype "passive"))
      (node (ref "Q37") (pin "1") (pinfunction "D_1") (pintype "passive"))
    )
    (net (code "250") (name "Net-(PAD96-P)") (class "Default")
      (node (ref "PAD96") (pin "1") (pinfunction "P_1") (pintype "passive"))
      (node (ref "Q38") (pin "1") (pinfunction "D_1") (pintype "passive"))
    )
    (net (code "251") (name "Net-(PAD97-P)") (class "Default")
      (node (ref "PAD97") (pin "1") (pinfunction "P_1") (pintype "passive"))
      (node (ref "Q39") (pin "1") (pinfunction "D_1") (pintype "passive"))
    )
    (net (code "252") (name "Net-(PAD98-P)") (class "Default")
      (node (ref "PAD98") (pin "1") (pinfunction "P_1") (pintype "passive"))
      (node (ref "Q40") (pin "1") (pinfunction "D_1") (pintype "passive"))
    )
    (net (code "253") (name "Net-(PAD99-P)") (class "Default")
      (node (ref "PAD99") (pin "1") (pinfunction "P_1") (pintype "passive"))
      (node (ref "Q41") (pin "1") (pinfunction "D_1") (pintype "passive"))
    )
    (net (code "254") (name "Net-(PAD100-P)") (class "Default")
      (node (ref "PAD100") (pin "1") (pinfunction "P_1") (pintype "passive"))
      (node (ref "Q42") (pin "1") (pinfunction "D_1") (pintype "passive"))
    )
    (net (code "255") (name "Net-(PAD101-P)") (class "Default")
      (node (ref "PAD101") (pin "1") (pinfunction "P_1") (pintype "passive"))
      (node (ref "Q43") (pin "1") (pinfunction "D_1") (pintype "passive"))
    )
    (net (code "256") (name "Net-(PAD102-P)") (class "Default")
      (node (ref "PAD102") (pin "1") (pinfunction "P_1") (pintype "passive"))
      (node (ref "Q44") (pin "1") (pinfunction "D_1") (pintype "passive"))
    )
    (net (code "257") (name "Net-(Q3-PadC)") (class "Default")
      (node (ref "Q3") (pin "C") (pinfunction "C_C") (pintype "passive"))
      (node (ref "R49") (pin "2") (pinfunction "2_2") (pintype "passive"))
    )
    (net (code "258") (name "Net-(Q5-PadC)") (class "Default")
      (node (ref "Q5") (pin "C") (pinfunction "C_C") (pintype "passive"))
      (node (ref "R58") (pin "2") (pinfunction "2_2") (pintype "passive"))
    )
    (net (code "259") (name "Net-(Q6-PadC)") (class "Default")
      (node (ref "Q6") (pin "C") (pinfunction "C_C") (pintype "passive"))
      (node (ref "R61") (pin "2") (pinfunction "2_2") (pintype "passive"))
    )
    (net (code "260") (name "Net-(Q7-PadC)") (class "Default")
      (node (ref "Q7") (pin "C") (pinfunction "C_C") (pintype "passive"))
      (node (ref "R64") (pin "2") (pinfunction "2_2") (pintype "passive"))
    )
    (net (code "261") (name "Net-(Q8-PadC)") (class "Default")
      (node (ref "Q8") (pin "C") (pinfunction "C_C") (pintype "passive"))
      (node (ref "R67") (pin "2") (pinfunction "2_2") (pintype "passive"))
    )
    (net (code "262") (name "Net-(Q9-PadC)") (class "Default")
      (node (ref "Q9") (pin "C") (pinfunction "C_C") (pintype "passive"))
      (node (ref "R70") (pin "2") (pinfunction "2_2") (pintype "passive"))
    )
    (net (code "263") (name "Net-(Q10-PadC)") (class "Default")
      (node (ref "Q10") (pin "C") (pinfunction "C_C") (pintype "passive"))
      (node (ref "R73") (pin "2") (pinfunction "2_2") (pintype "passive"))
    )
    (net (code "264") (name "Net-(Q11-PadC)") (class "Default")
      (node (ref "Q11") (pin "C") (pinfunction "C_C") (pintype "passive"))
      (node (ref "R76") (pin "2") (pinfunction "2_2") (pintype "passive"))
    )
    (net (code "265") (name "Net-(Q12-G)") (class "Default")
      (node (ref "Q12") (pin "3") (pinfunction "G_3") (pintype "passive"))
      (node (ref "R79") (pin "2") (pinfunction "2_2") (pintype "passive"))
    )
    (net (code "266") (name "Net-(Q13-D)") (class "Default")
      (node (ref "LED4") (pin "A") (pinfunction "A_A") (pintype "passive"))
      (node (ref "Q13") (pin "1") (pinfunction "D_1") (pintype "passive"))
      (node (ref "R81") (pin "1") (pinfunction "1_1") (pintype "passive"))
    )
    (net (code "267") (name "Net-(Q14-D)") (class "Default")
      (node (ref "LED5") (pin "A") (pinfunction "A_A") (pintype "passive"))
      (node (ref "Q14") (pin "1") (pinfunction "D_1") (pintype "passive"))
      (node (ref "R82") (pin "1") (pinfunction "1_1") (pintype "passive"))
    )
    (net (code "268") (name "Net-(Q15-G)") (class "Default")
      (node (ref "Q15") (pin "3") (pinfunction "G_3") (pintype "passive"))
      (node (ref "R85") (pin "1") (pinfunction "1_1") (pintype "passive"))
      (node (ref "R86") (pin "1") (pinfunction "1_1") (pintype "passive"))
    )
    (net (code "269") (name "Net-(Q16-G)") (class "Default")
      (node (ref "Q16") (pin "3") (pinfunction "G_3") (pintype "passive"))
      (node (ref "R87") (pin "1") (pinfunction "1_1") (pintype "passive"))
      (node (ref "R88") (pin "1") (pinfunction "1_1") (pintype "passive"))
    )
    (net (code "270") (name "Net-(Q17-G)") (class "Default")
      (node (ref "Q17") (pin "3") (pinfunction "G_3") (pintype "passive"))
      (node (ref "R89") (pin "1") (pinfunction "1_1") (pintype "passive"))
      (node (ref "R90") (pin "1") (pinfunction "1_1") (pintype "passive"))
    )
    (net (code "271") (name "Net-(Q18-G)") (class "Default")
      (node (ref "Q18") (pin "3") (pinfunction "G_3") (pintype "passive"))
      (node (ref "R91") (pin "1") (pinfunction "1_1") (pintype "passive"))
      (node (ref "R92") (pin "1") (pinfunction "1_1") (pintype "passive"))
    )
    (net (code "272") (name "Net-(Q19-G)") (class "Default")
      (node (ref "Q19") (pin "3") (pinfunction "G_3") (pintype "passive"))
      (node (ref "R93") (pin "1") (pinfunction "1_1") (pintype "passive"))
      (node (ref "R94") (pin "1") (pinfunction "1_1") (pintype "passive"))
    )
    (net (code "273") (name "Net-(Q20-G)") (class "Default")
      (node (ref "Q20") (pin "3") (pinfunction "G_3") (pintype "passive"))
      (node (ref "R95") (pin "1") (pinfunction "1_1") (pintype "passive"))
      (node (ref "R96") (pin "1") (pinfunction "1_1") (pintype "passive"))
    )
    (net (code "274") (name "Net-(Q21-G)") (class "Default")
      (node (ref "Q21") (pin "3") (pinfunction "G_3") (pintype "passive"))
      (node (ref "R97") (pin "1") (pinfunction "1_1") (pintype "passive"))
      (node (ref "R98") (pin "1") (pinfunction "1_1") (pintype "passive"))
    )
    (net (code "275") (name "Net-(Q22-G)") (class "Default")
      (node (ref "Q22") (pin "3") (pinfunction "G_3") (pintype "passive"))
      (node (ref "R100") (pin "1") (pinfunction "1_1") (pintype "passive"))
      (node (ref "R99") (pin "1") (pinfunction "1_1") (pintype "passive"))
    )
    (net (code "276") (name "Net-(Q23-G)") (class "Default")
      (node (ref "Q23") (pin "3") (pinfunction "G_3") (pintype "passive"))
      (node (ref "R101") (pin "1") (pinfunction "1_1") (pintype "passive"))
      (node (ref "R102") (pin "1") (pinfunction "1_1") (pintype "passive"))
    )
    (net (code "277") (name "Net-(Q24-G)") (class "Default")
      (node (ref "Q24") (pin "3") (pinfunction "G_3") (pintype "passive"))
      (node (ref "R103") (pin "1") (pinfunction "1_1") (pintype "passive"))
      (node (ref "R104") (pin "1") (pinfunction "1_1") (pintype "passive"))
    )
    (net (code "278") (name "Net-(Q25-G)") (class "Default")
      (node (ref "Q25") (pin "3") (pinfunction "G_3") (pintype "passive"))
      (node (ref "R105") (pin "1") (pinfunction "1_1") (pintype "passive"))
      (node (ref "R106") (pin "1") (pinfunction "1_1") (pintype "passive"))
    )
    (net (code "279") (name "Net-(Q26-G)") (class "Default")
      (node (ref "Q26") (pin "3") (pinfunction "G_3") (pintype "passive"))
      (node (ref "R107") (pin "1") (pinfunction "1_1") (pintype "passive"))
      (node (ref "R108") (pin "1") (pinfunction "1_1") (pintype "passive"))
    )
    (net (code "280") (name "Net-(Q27-G)") (class "Default")
      (node (ref "Q27") (pin "3") (pinfunction "G_3") (pintype "passive"))
      (node (ref "R109") (pin "1") (pinfunction "1_1") (pintype "passive"))
      (node (ref "R110") (pin "1") (pinfunction "1_1") (pintype "passive"))
    )
    (net (code "281") (name "Net-(Q28-G)") (class "Default")
      (node (ref "Q28") (pin "3") (pinfunction "G_3") (pintype "passive"))
      (node (ref "R111") (pin "1") (pinfunction "1_1") (pintype "passive"))
      (node (ref "R112") (pin "1") (pinfunction "1_1") (pintype "passive"))
    )
    (net (code "282") (name "Net-(Q29-G)") (class "Default")
      (node (ref "Q29") (pin "3") (pinfunction "G_3") (pintype "passive"))
      (node (ref "R113") (pin "1") (pinfunction "1_1") (pintype "passive"))
      (node (ref "R114") (pin "1") (pinfunction "1_1") (pintype "passive"))
    )
    (net (code "283") (name "Net-(Q30-G)") (class "Default")
      (node (ref "Q30") (pin "3") (pinfunction "G_3") (pintype "passive"))
      (node (ref "R115") (pin "1") (pinfunction "1_1") (pintype "passive"))
      (node (ref "R116") (pin "1") (pinfunction "1_1") (pintype "passive"))
    )
    (net (code "284") (name "Net-(Q31-G)") (class "Default")
      (node (ref "Q31") (pin "3") (pinfunction "G_3") (pintype "passive"))
      (node (ref "R117") (pin "1") (pinfunction "1_1") (pintype "passive"))
      (node (ref "R118") (pin "1") (pinfunction "1_1") (pintype "passive"))
    )
    (net (code "285") (name "Net-(Q32-G)") (class "Default")
      (node (ref "Q32") (pin "3") (pinfunction "G_3") (pintype "passive"))
      (node (ref "R119") (pin "1") (pinfunction "1_1") (pintype "passive"))
      (node (ref "R120") (pin "1") (pinfunction "1_1") (pintype "passive"))
    )
    (net (code "286") (name "Net-(Q33-G)") (class "Default")
      (node (ref "Q33") (pin "3") (pinfunction "G_3") (pintype "passive"))
      (node (ref "R121") (pin "1") (pinfunction "1_1") (pintype "passive"))
      (node (ref "R122") (pin "1") (pinfunction "1_1") (pintype "passive"))
    )
    (net (code "287") (name "Net-(Q34-G)") (class "Default")
      (node (ref "Q34") (pin "3") (pinfunction "G_3") (pintype "passive"))
      (node (ref "R123") (pin "1") (pinfunction "1_1") (pintype "passive"))
      (node (ref "R124") (pin "1") (pinfunction "1_1") (pintype "passive"))
    )
    (net (code "288") (name "Net-(Q35-G)") (class "Default")
      (node (ref "Q35") (pin "3") (pinfunction "G_3") (pintype "passive"))
      (node (ref "R125") (pin "1") (pinfunction "1_1") (pintype "passive"))
      (node (ref "R126") (pin "1") (pinfunction "1_1") (pintype "passive"))
    )
    (net (code "289") (name "Net-(Q36-G)") (class "Default")
      (node (ref "Q36") (pin "3") (pinfunction "G_3") (pintype "passive"))
      (node (ref "R127") (pin "1") (pinfunction "1_1") (pintype "passive"))
      (node (ref "R128") (pin "1") (pinfunction "1_1") (pintype "passive"))
    )
    (net (code "290") (name "Net-(Q37-G)") (class "Default")
      (node (ref "Q37") (pin "3") (pinfunction "G_3") (pintype "passive"))
      (node (ref "R129") (pin "1") (pinfunction "1_1") (pintype "passive"))
      (node (ref "R130") (pin "1") (pinfunction "1_1") (pintype "passive"))
    )
    (net (code "291") (name "Net-(Q38-G)") (class "Default")
      (node (ref "Q38") (pin "3") (pinfunction "G_3") (pintype "passive"))
      (node (ref "R131") (pin "1") (pinfunction "1_1") (pintype "passive"))
      (node (ref "R132") (pin "1") (pinfunction "1_1") (pintype "passive"))
    )
    (net (code "292") (name "Net-(Q39-G)") (class "Default")
      (node (ref "Q39") (pin "3") (pinfunction "G_3") (pintype "passive"))
      (node (ref "R133") (pin "1") (pinfunction "1_1") (pintype "passive"))
      (node (ref "R134") (pin "1") (pinfunction "1_1") (pintype "passive"))
    )
    (net (code "293") (name "Net-(Q40-G)") (class "Default")
      (node (ref "Q40") (pin "3") (pinfunction "G_3") (pintype "passive"))
      (node (ref "R135") (pin "1") (pinfunction "1_1") (pintype "passive"))
      (node (ref "R136") (pin "1") (pinfunction "1_1") (pintype "passive"))
    )
    (net (code "294") (name "Net-(Q41-G)") (class "Default")
      (node (ref "Q41") (pin "3") (pinfunction "G_3") (pintype "passive"))
      (node (ref "R137") (pin "1") (pinfunction "1_1") (pintype "passive"))
      (node (ref "R138") (pin "1") (pinfunction "1_1") (pintype "passive"))
    )
    (net (code "295") (name "Net-(Q42-G)") (class "Default")
      (node (ref "Q42") (pin "3") (pinfunction "G_3") (pintype "passive"))
      (node (ref "R139") (pin "1") (pinfunction "1_1") (pintype "passive"))
      (node (ref "R140") (pin "1") (pinfunction "1_1") (pintype "passive"))
    )
    (net (code "296") (name "Net-(Q43-G)") (class "Default")
      (node (ref "Q43") (pin "3") (pinfunction "G_3") (pintype "passive"))
      (node (ref "R141") (pin "1") (pinfunction "1_1") (pintype "passive"))
      (node (ref "R142") (pin "1") (pinfunction "1_1") (pintype "passive"))
    )
    (net (code "297") (name "Net-(Q44-G)") (class "Default")
      (node (ref "Q44") (pin "3") (pinfunction "G_3") (pintype "passive"))
      (node (ref "R143") (pin "1") (pinfunction "1_1") (pintype "passive"))
      (node (ref "R144") (pin "1") (pinfunction "1_1") (pintype "passive"))
    )
    (net (code "298") (name "Net-(Q45-G)") (class "Default")
      (node (ref "Q45") (pin "3") (pinfunction "G_3") (pintype "passive"))
      (node (ref "R145") (pin "1") (pinfunction "1_1") (pintype "passive"))
      (node (ref "R146") (pin "1") (pinfunction "1_1") (pintype "passive"))
    )
    (net (code "299") (name "Net-(Q46-G)") (class "Default")
      (node (ref "Q46") (pin "3") (pinfunction "G_3") (pintype "passive"))
      (node (ref "R147") (pin "1") (pinfunction "1_1") (pintype "passive"))
      (node (ref "R148") (pin "1") (pinfunction "1_1") (pintype "passive"))
    )
    (net (code "300") (name "Net-(Q47-G)") (class "Default")
      (node (ref "Q47") (pin "3") (pinfunction "G_3") (pintype "passive"))
      (node (ref "R149") (pin "1") (pinfunction "1_1") (pintype "passive"))
      (node (ref "R150") (pin "1") (pinfunction "1_1") (pintype "passive"))
    )
    (net (code "301") (name "Net-(R8-Pad2)") (class "Default")
      (node (ref "R8") (pin "2") (pinfunction "2_2") (pintype "passive"))
      (node (ref "SJ4") (pin "1") (pinfunction "1_1") (pintype "passive"))
    )
    (net (code "302") (name "Net-(R16-Pad2)") (class "Default")
      (node (ref "R16") (pin "2") (pinfunction "2_2") (pintype "passive"))
      (node (ref "SJ8") (pin "1") (pinfunction "1_1") (pintype "passive"))
    )
    (net (code "303") (name "Net-(R24-Pad2)") (class "Default")
      (node (ref "R24") (pin "2") (pinfunction "2_2") (pintype "passive"))
      (node (ref "SJ12") (pin "1") (pinfunction "1_1") (pintype "passive"))
    )
    (net (code "304") (name "Net-(R49-Pad1)") (class "Default")
      (node (ref "R49") (pin "1") (pinfunction "1_1") (pintype "passive"))
      (node (ref "R50") (pin "2") (pinfunction "2_2") (pintype "passive"))
    )
    (net (code "305") (name "Net-(R58-Pad1)") (class "Default")
      (node (ref "R58") (pin "1") (pinfunction "1_1") (pintype "passive"))
      (node (ref "R59") (pin "2") (pinfunction "2_2") (pintype "passive"))
    )
    (net (code "306") (name "Net-(R61-Pad1)") (class "Default")
      (node (ref "R61") (pin "1") (pinfunction "1_1") (pintype "passive"))
      (node (ref "R62") (pin "2") (pinfunction "2_2") (pintype "passive"))
    )
    (net (code "307") (name "Net-(R64-Pad1)") (class "Default")
      (node (ref "R64") (pin "1") (pinfunction "1_1") (pintype "passive"))
      (node (ref "R65") (pin "2") (pinfunction "2_2") (pintype "passive"))
    )
    (net (code "308") (name "Net-(R67-Pad1)") (class "Default")
      (node (ref "R67") (pin "1") (pinfunction "1_1") (pintype "passive"))
      (node (ref "R68") (pin "2") (pinfunction "2_2") (pintype "passive"))
    )
    (net (code "309") (name "Net-(R70-Pad1)") (class "Default")
      (node (ref "R70") (pin "1") (pinfunction "1_1") (pintype "passive"))
      (node (ref "R71") (pin "2") (pinfunction "2_2") (pintype "passive"))
    )
    (net (code "310") (name "Net-(R73-Pad1)") (class "Default")
      (node (ref "R73") (pin "1") (pinfunction "1_1") (pintype "passive"))
      (node (ref "R74") (pin "2") (pinfunction "2_2") (pintype "passive"))
    )
    (net (code "311") (name "Net-(R76-Pad1)") (class "Default")
      (node (ref "R76") (pin "1") (pinfunction "1_1") (pintype "passive"))
      (node (ref "R77") (pin "2") (pinfunction "2_2") (pintype "passive"))
    )
    (net (code "312") (name "Net-(U1-A0)") (class "Default")
      (node (ref "R1") (pin "2") (pinfunction "2_2") (pintype "passive"))
      (node (ref "U1") (pin "1") (pinfunction "A0_1") (pintype "input"))
    )
    (net (code "313") (name "Net-(U1-A1)") (class "Default")
      (node (ref "R2") (pin "2") (pinfunction "2_2") (pintype "passive"))
      (node (ref "U1") (pin "2") (pinfunction "A1_2") (pintype "input"))
    )
    (net (code "314") (name "Net-(U1-A2)") (class "Default")
      (node (ref "R3") (pin "2") (pinfunction "2_2") (pintype "passive"))
      (node (ref "U1") (pin "3") (pinfunction "A2_3") (pintype "input"))
    )
    (net (code "315") (name "Net-(U1-A3)") (class "Default")
      (node (ref "R4") (pin "2") (pinfunction "2_2") (pintype "passive"))
      (node (ref "U1") (pin "4") (pinfunction "A3_4") (pintype "input"))
    )
    (net (code "316") (name "Net-(U1-A4)") (class "Default")
      (node (ref "R5") (pin "2") (pinfunction "2_2") (pintype "passive"))
      (node (ref "SJ3") (pin "2") (pinfunction "2_2") (pintype "passive"))
      (node (ref "U1") (pin "5") (pinfunction "A4_5") (pintype "input"))
    )
    (net (code "317") (name "Net-(U1-A5)") (class "Default")
      (node (ref "R6") (pin "2") (pinfunction "2_2") (pintype "passive"))
      (node (ref "SJ2") (pin "2") (pinfunction "2_2") (pintype "passive"))
      (node (ref "U1") (pin "24") (pinfunction "A5_24") (pintype "input"))
    )
    (net (code "318") (name "Net-(U1-A6)") (class "Default")
      (node (ref "R7") (pin "2") (pinfunction "2_2") (pintype "passive"))
      (node (ref "SJ1") (pin "2") (pinfunction "2_2") (pintype "passive"))
      (node (ref "U1") (pin "25") (pinfunction "A6_25") (pintype "input"))
    )
    (net (code "319") (name "Net-(U2-A0)") (class "Default")
      (node (ref "R9") (pin "2") (pinfunction "2_2") (pintype "passive"))
      (node (ref "U2") (pin "1") (pinfunction "A0_1") (pintype "input"))
    )
    (net (code "320") (name "Net-(U2-A1)") (class "Default")
      (node (ref "R10") (pin "2") (pinfunction "2_2") (pintype "passive"))
      (node (ref "U2") (pin "2") (pinfunction "A1_2") (pintype "input"))
    )
    (net (code "321") (name "Net-(U2-A2)") (class "Default")
      (node (ref "R11") (pin "2") (pinfunction "2_2") (pintype "passive"))
      (node (ref "U2") (pin "3") (pinfunction "A2_3") (pintype "input"))
    )
    (net (code "322") (name "Net-(U2-A3)") (class "Default")
      (node (ref "R12") (pin "2") (pinfunction "2_2") (pintype "passive"))
      (node (ref "U2") (pin "4") (pinfunction "A3_4") (pintype "input"))
    )
    (net (code "323") (name "Net-(U2-A4)") (class "Default")
      (node (ref "R13") (pin "2") (pinfunction "2_2") (pintype "passive"))
      (node (ref "SJ5") (pin "2") (pinfunction "2_2") (pintype "passive"))
      (node (ref "U2") (pin "5") (pinfunction "A4_5") (pintype "input"))
    )
    (net (code "324") (name "Net-(U2-A5)") (class "Default")
      (node (ref "R14") (pin "2") (pinfunction "2_2") (pintype "passive"))
      (node (ref "SJ6") (pin "2") (pinfunction "2_2") (pintype "passive"))
      (node (ref "U2") (pin "24") (pinfunction "A5_24") (pintype "input"))
    )
    (net (code "325") (name "Net-(U2-A6)") (class "Default")
      (node (ref "R15") (pin "2") (pinfunction "2_2") (pintype "passive"))
      (node (ref "SJ7") (pin "2") (pinfunction "2_2") (pintype "passive"))
      (node (ref "U2") (pin "25") (pinfunction "A6_25") (pintype "input"))
    )
    (net (code "326") (name "Net-(U3-INH)") (class "Default")
      (node (ref "R56") (pin "2") (pinfunction "2_2") (pintype "passive"))
      (node (ref "SJ16") (pin "2") (pinfunction "2_2") (pintype "passive"))
      (node (ref "U3") (pin "6") (pinfunction "INH_6") (pintype "input"))
    )
    (net (code "327") (name "Net-(U4-A0)") (class "Default")
      (node (ref "R17") (pin "2") (pinfunction "2_2") (pintype "passive"))
      (node (ref "U4") (pin "1") (pinfunction "A0_1") (pintype "input"))
    )
    (net (code "328") (name "Net-(U4-A1)") (class "Default")
      (node (ref "R18") (pin "2") (pinfunction "2_2") (pintype "passive"))
      (node (ref "U4") (pin "2") (pinfunction "A1_2") (pintype "input"))
    )
    (net (code "329") (name "Net-(U4-A2)") (class "Default")
      (node (ref "R19") (pin "2") (pinfunction "2_2") (pintype "passive"))
      (node (ref "U4") (pin "3") (pinfunction "A2_3") (pintype "input"))
    )
    (net (code "330") (name "Net-(U4-A3)") (class "Default")
      (node (ref "R20") (pin "2") (pinfunction "2_2") (pintype "passive"))
      (node (ref "U4") (pin "4") (pinfunction "A3_4") (pintype "input"))
    )
    (net (code "331") (name "Net-(U4-A4)") (class "Default")
      (node (ref "R21") (pin "2") (pinfunction "2_2") (pintype "passive"))
      (node (ref "SJ11") (pin "2") (pinfunction "2_2") (pintype "passive"))
      (node (ref "U4") (pin "5") (pinfunction "A4_5") (pintype "input"))
    )
    (net (code "332") (name "Net-(U4-A5)") (class "Default")
      (node (ref "R22") (pin "2") (pinfunction "2_2") (pintype "passive"))
      (node (ref "SJ10") (pin "2") (pinfunction "2_2") (pintype "passive"))
      (node (ref "U4") (pin "24") (pinfunction "A5_24") (pintype "input"))
    )
    (net (code "333") (name "Net-(U4-A6)") (class "Default")
      (node (ref "R23") (pin "2") (pinfunction "2_2") (pintype "passive"))
      (node (ref "SJ9") (pin "2") (pinfunction "2_2") (pintype "passive"))
      (node (ref "U4") (pin "25") (pinfunction "A6_25") (pintype "input"))
    )
    (net (code "334") (name "Net-(U7-VDD)") (class "Default")
      (node (ref "C18") (pin "1") (pinfunction "1_1") (pintype "passive"))
      (node (ref "C19") (pin "1") (pinfunction "1_1") (pintype "passive"))
      (node (ref "R78") (pin "2") (pinfunction "2_2") (pintype "passive"))
      (node (ref "U7") (pin "15") (pinfunction "VREF_15") (pintype "input"))
      (node (ref "U7") (pin "16") (pinfunction "VDD_16") (pintype "power_in"))
    )
    (net (code "335") (name "RESET") (class "Default")
      (node (ref "C14") (pin "2") (pinfunction "2_2") (pintype "passive"))
      (node (ref "IC4") (pin "29") (pinfunction "PC6(/RESET)_29") (pintype "bidirectional"))
      (node (ref "R55") (pin "2") (pinfunction "2_2") (pintype "passive"))
      (node (ref "S1") (pin "3") (pinfunction "2.1_3") (pintype "passive"))
      (node (ref "S1") (pin "4") (pinfunction "2.2_4") (pintype "passive"))
    )
    (net (code "336") (name "unconnected-(IC4-ADC6-Pad19)") (class "Default")
      (node (ref "IC4") (pin "19") (pinfunction "ADC6_19") (pintype "bidirectional"))
    )
    (net (code "337") (name "unconnected-(IC4-ADC7-Pad22)") (class "Default")
      (node (ref "IC4") (pin "22") (pinfunction "ADC7_22") (pintype "bidirectional"))
    )
    (net (code "338") (name "unconnected-(IC5-CBUS2-Pad13)") (class "Default")
      (node (ref "IC5") (pin "13") (pinfunction "CBUS2_13") (pintype "bidirectional"))
    )
    (net (code "339") (name "unconnected-(IC5-CBUS3-Pad14)") (class "Default")
      (node (ref "IC5") (pin "14") (pinfunction "CBUS3_14") (pintype "bidirectional"))
    )
    (net (code "340") (name "unconnected-(IC5-CBUS4-Pad12)") (class "Default")
      (node (ref "IC5") (pin "12") (pinfunction "CBUS4_12") (pintype "bidirectional"))
    )
    (net (code "341") (name "unconnected-(IC5-OSCI-Pad27)") (class "Default")
      (node (ref "IC5") (pin "27") (pinfunction "OSCI_27") (pintype "input"))
    )
    (net (code "342") (name "unconnected-(IC5-OSCO-Pad28)") (class "Default")
      (node (ref "IC5") (pin "28") (pinfunction "OSCO_28") (pintype "output"))
    )
    (net (code "343") (name "unconnected-(IC5-~{DCD}-Pad10)") (class "Default")
      (node (ref "IC5") (pin "10") (pinfunction "~{DCD}_10") (pintype "input"))
    )
    (net (code "344") (name "unconnected-(IC5-~{DSR}-Pad9)") (class "Default")
      (node (ref "IC5") (pin "9") (pinfunction "~{DSR}_9") (pintype "input"))
    )
    (net (code "345") (name "unconnected-(IC5-~{RESET}-Pad19)") (class "Default")
      (node (ref "IC5") (pin "19") (pinfunction "~{RESET}_19") (pintype "input"))
    )
    (net (code "346") (name "unconnected-(IC5-~{RI}-Pad6)") (class "Default")
      (node (ref "IC5") (pin "6") (pinfunction "~{RI}_6") (pintype "input"))
    )
    (net (code "347") (name "unconnected-(IC5-~{RTS}-Pad3)") (class "Default")
      (node (ref "IC5") (pin "3") (pinfunction "~{RTS}_3") (pintype "output"))
    )
    (net (code "348") (name "unconnected-(S1-SH-Pad5)") (class "Default")
      (node (ref "S1") (pin "5") (pinfunction "SH_5") (pintype "passive"))
    )
    (net (code "349") (name "unconnected-(U2-LED15-Pad22)") (class "Default")
      (node (ref "U2") (pin "22") (pinfunction "LED15_22") (pintype "output"))
    )
    (net (code "350") (name "unconnected-(U4-LED15-Pad22)") (class "Default")
      (node (ref "U4") (pin "22") (pinfunction "LED15_22") (pintype "output"))
    )
    (net (code "351") (name "unconnected-(U5-COM-Pad10)") (class "Default")
      (node (ref "U5") (pin "10") (pinfunction "COM_10") (pintype "output"))
    )
    (net (code "352") (name "unconnected-(U6-5C-Pad14)") (class "Default")
      (node (ref "U6") (pin "14") (pinfunction "5C_14") (pintype "output"))
    )
    (net (code "353") (name "unconnected-(U6-6C-Pad13)") (class "Default")
      (node (ref "U6") (pin "13") (pinfunction "6C_13") (pintype "output"))
    )
    (net (code "354") (name "unconnected-(U6-7C-Pad12)") (class "Default")
      (node (ref "U6") (pin "12") (pinfunction "7C_12") (pintype "output"))
    )
    (net (code "355") (name "unconnected-(U6-8C-Pad11)") (class "Default")
      (node (ref "U6") (pin "11") (pinfunction "8C_11") (pintype "output"))
    )
    (net (code "356") (name "unconnected-(U6-COM-Pad10)") (class "Default")
      (node (ref "U6") (pin "10") (pinfunction "COM_10") (pintype "output"))
    )
    (net (code "357") (name "unconnected-(X2-Pad1)") (class "Default")
      (node (ref "X2") (pin "1") (pinfunction "1_1") (pintype "passive"))
    )
    (net (code "358") (name "unconnected-(X2-Pad4)") (class "Default")
      (node (ref "X2") (pin "4") (pinfunction "4_4") (pintype "passive"))
    )
    (net (code "359") (name "unconnected-(X2-Pad5)") (class "Default")
      (node (ref "X2") (pin "5") (pinfunction "5_5") (pintype "passive"))
    )
    (net (code "360") (name "unconnected-(X2-Pad6)") (class "Default")
      (node (ref "X2") (pin "6") (pinfunction "6_6") (pintype "passive"))
    )
    (net (code "361") (name "unconnected-(X2-Pad7)") (class "Default")
      (node (ref "X2") (pin "7") (pinfunction "7_7") (pintype "passive"))
    )
    (net (code "362") (name "unconnected-(X2-Pad8)") (class "Default")
      (node (ref "X2") (pin "8") (pinfunction "8_8") (pintype "passive"))
    )
    (net (code "363") (name "unconnected-(X2-Pad9)") (class "Default")
      (node (ref "X2") (pin "9") (pinfunction "9_9") (pintype "passive"))
    )
    (net (code "364") (name "unconnected-(X3-Pad4)") (class "Default")
      (node (ref "X3") (pin "4") (pinfunction "4_4") (pintype "passive"))
    )
  )
)
